# 1-Schematic_andromeda.net
KiCad netlist of a schematic drawn in EasyEDA
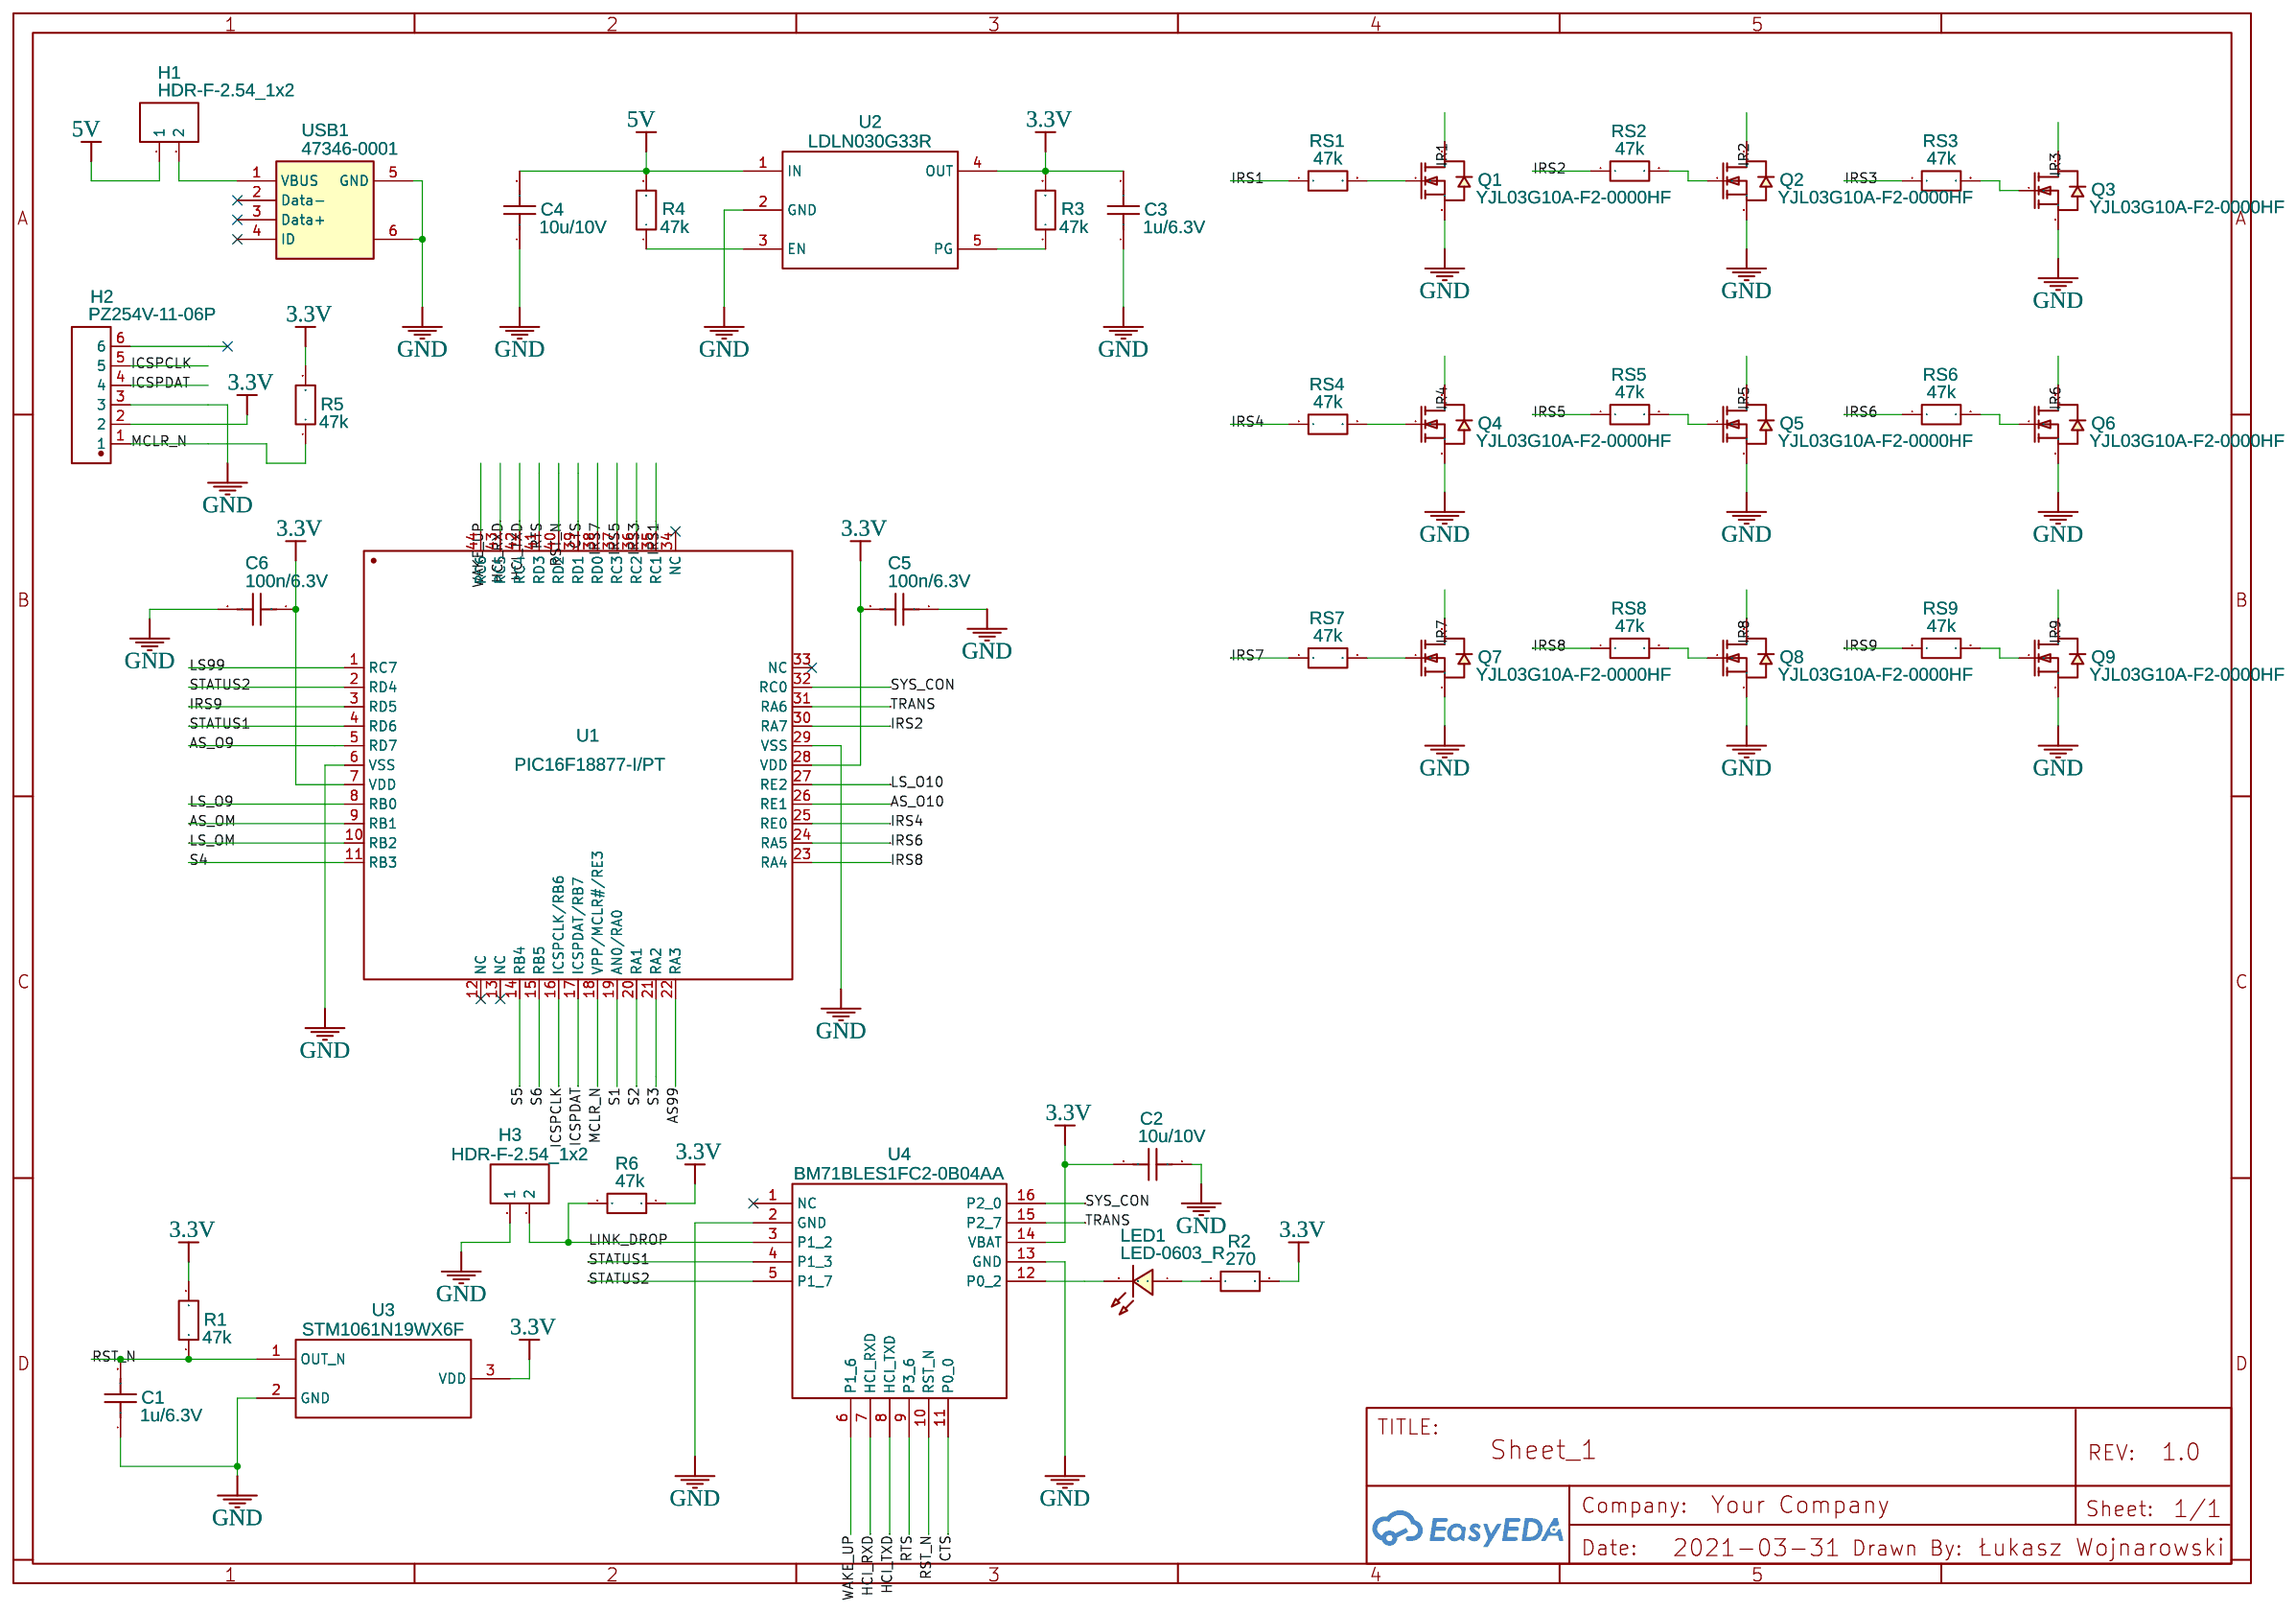
[diagram p0: uC]
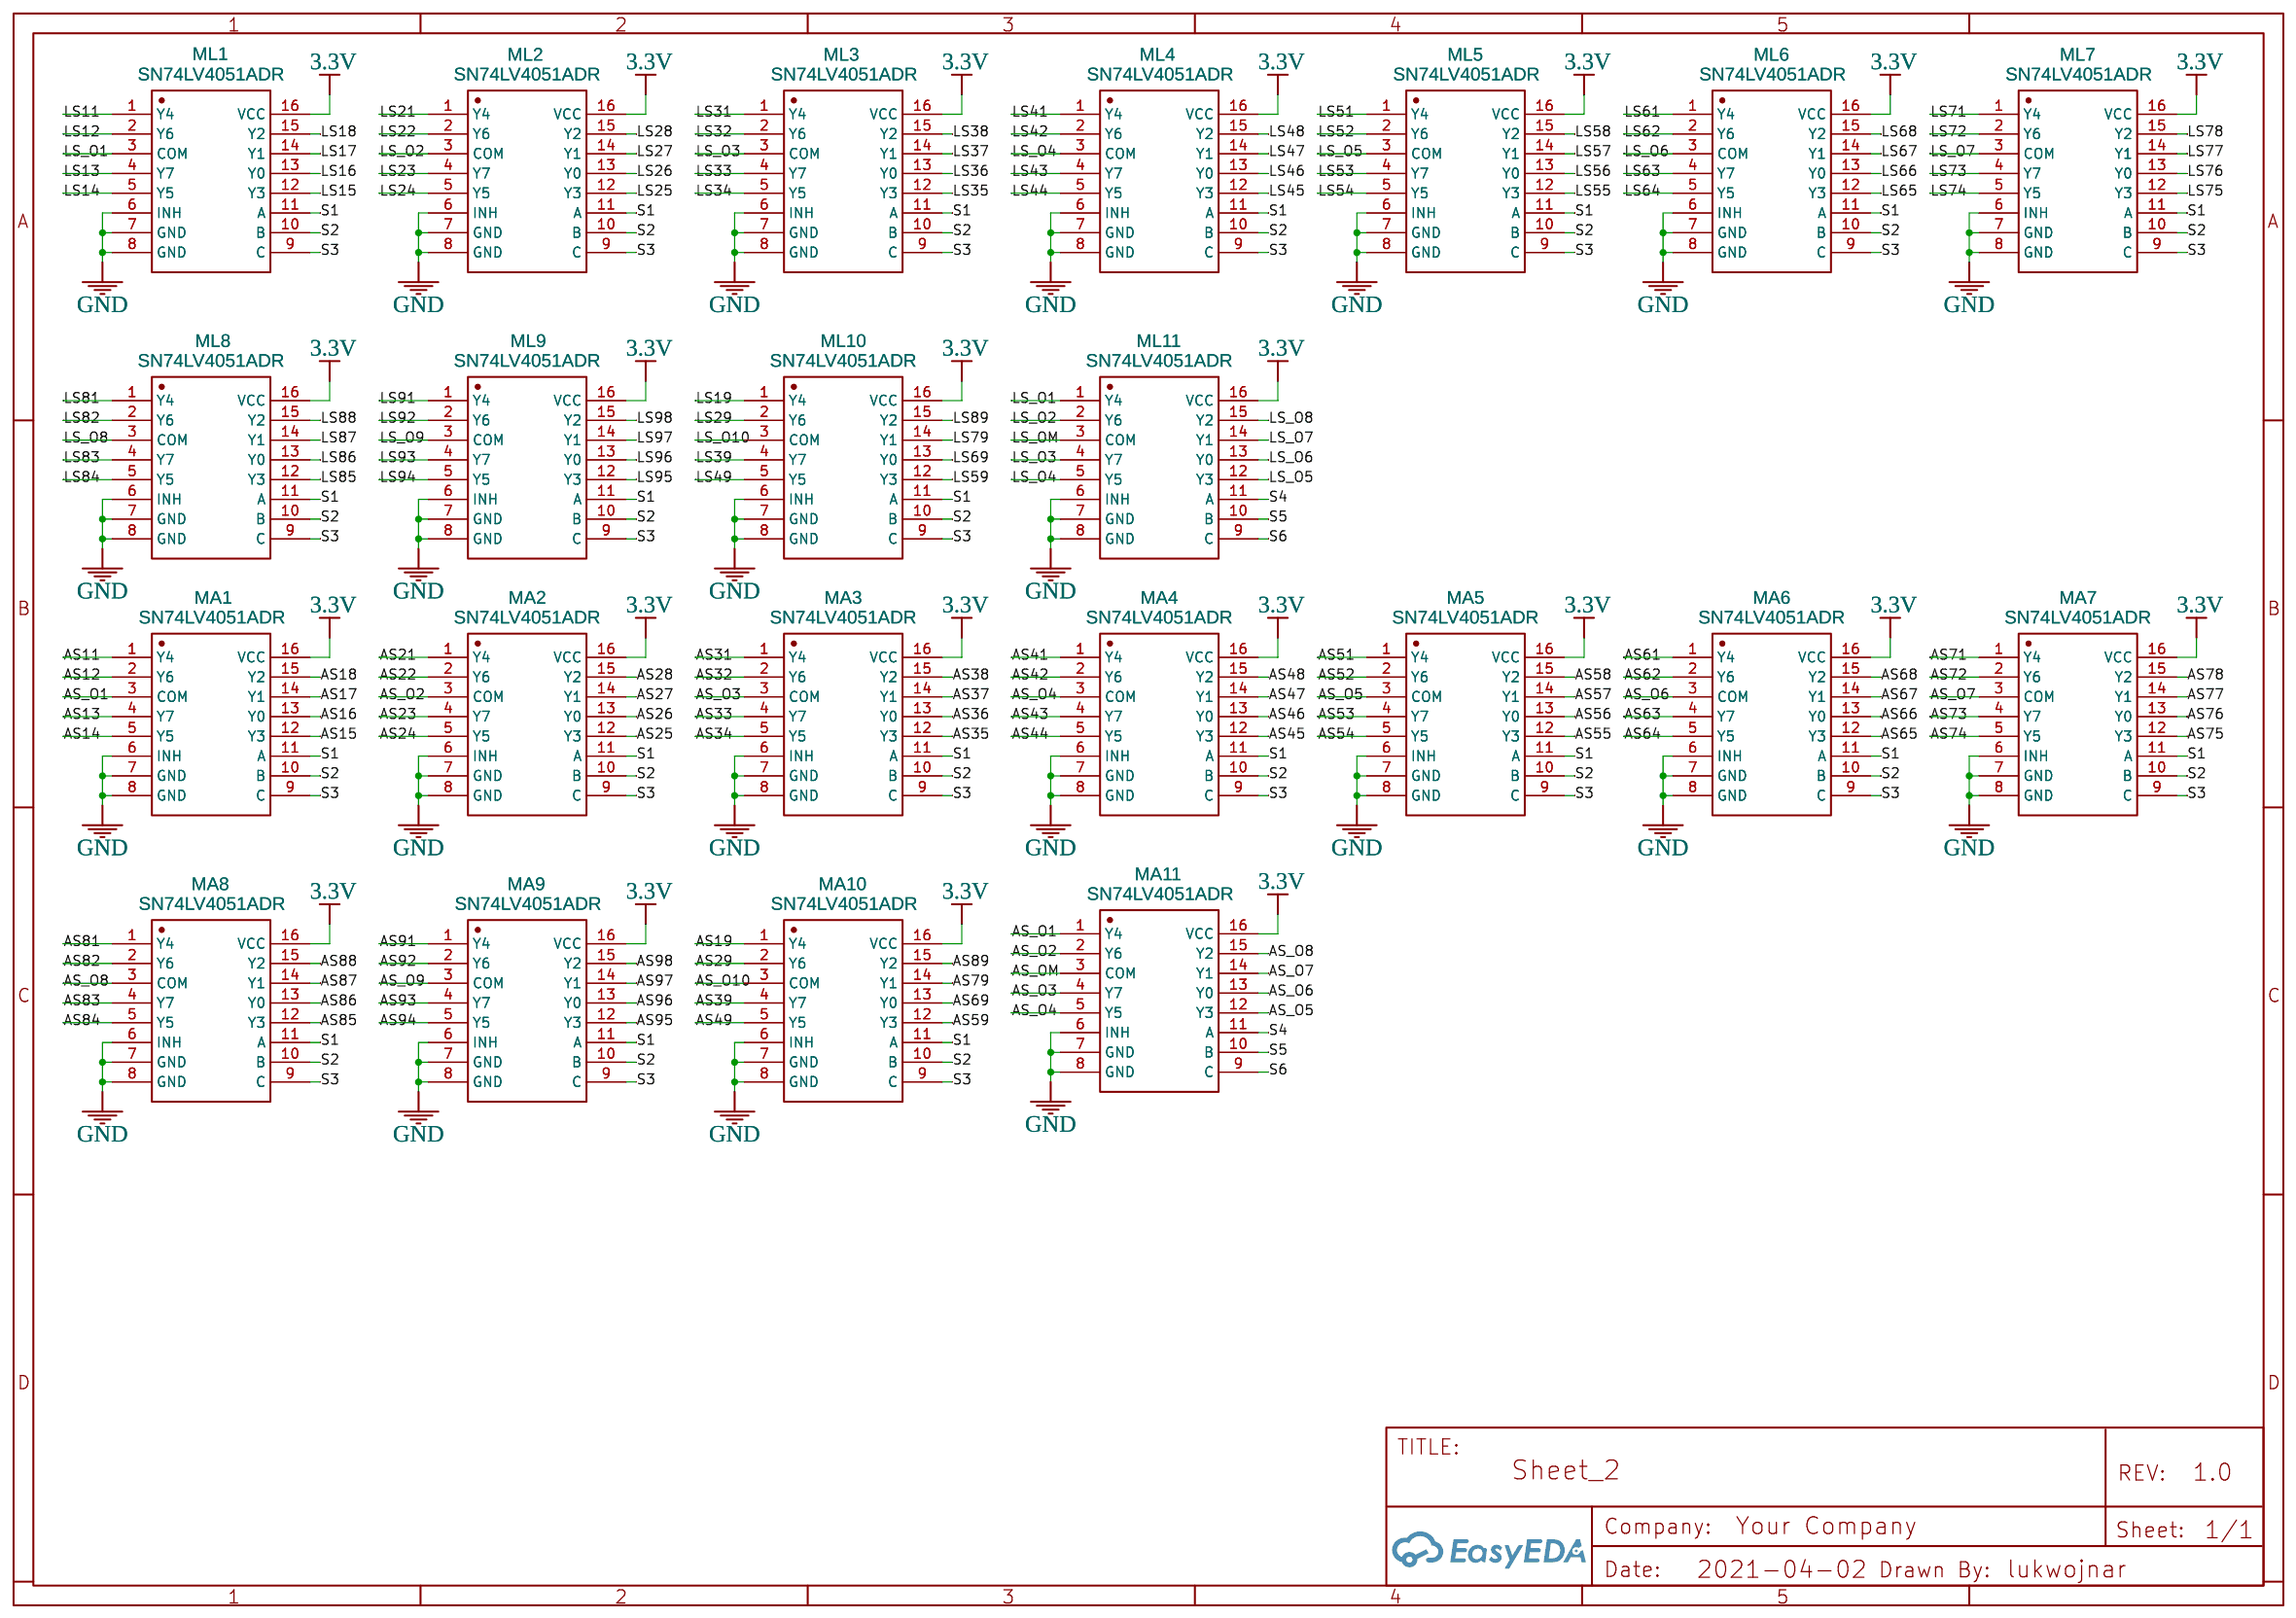
[diagram p1: MUX]
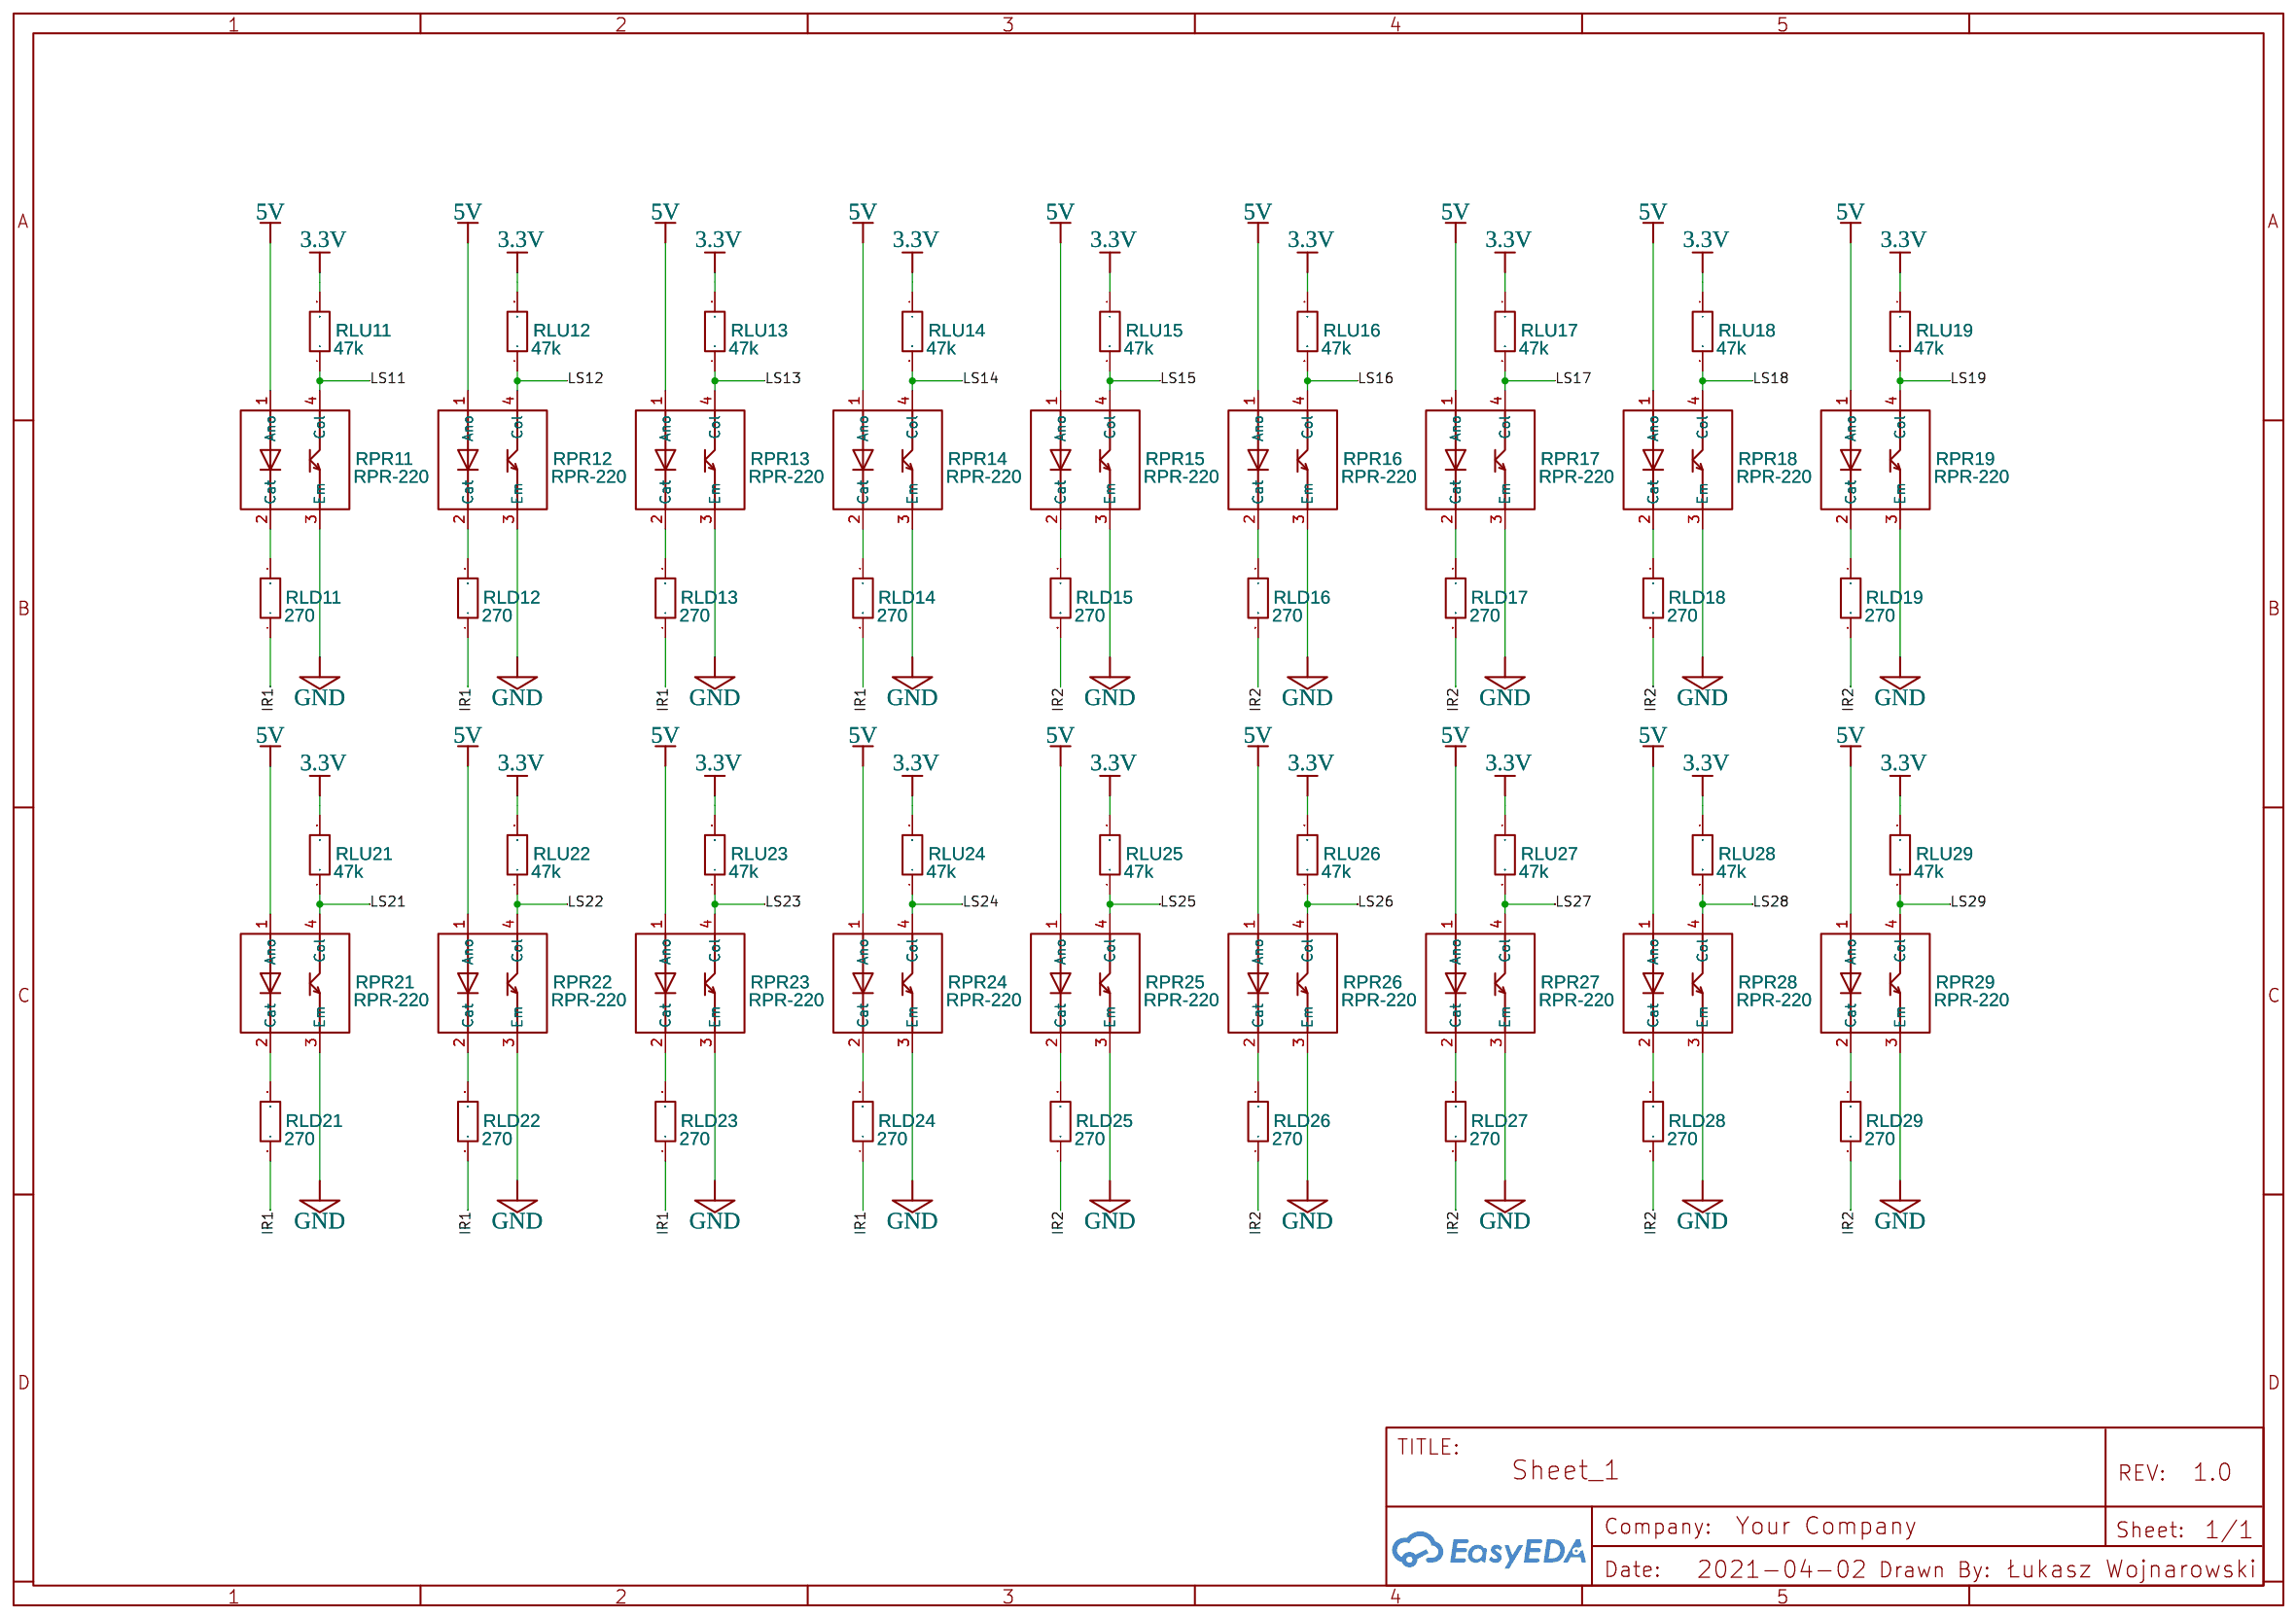
[diagram p2: Light Sensors 1]
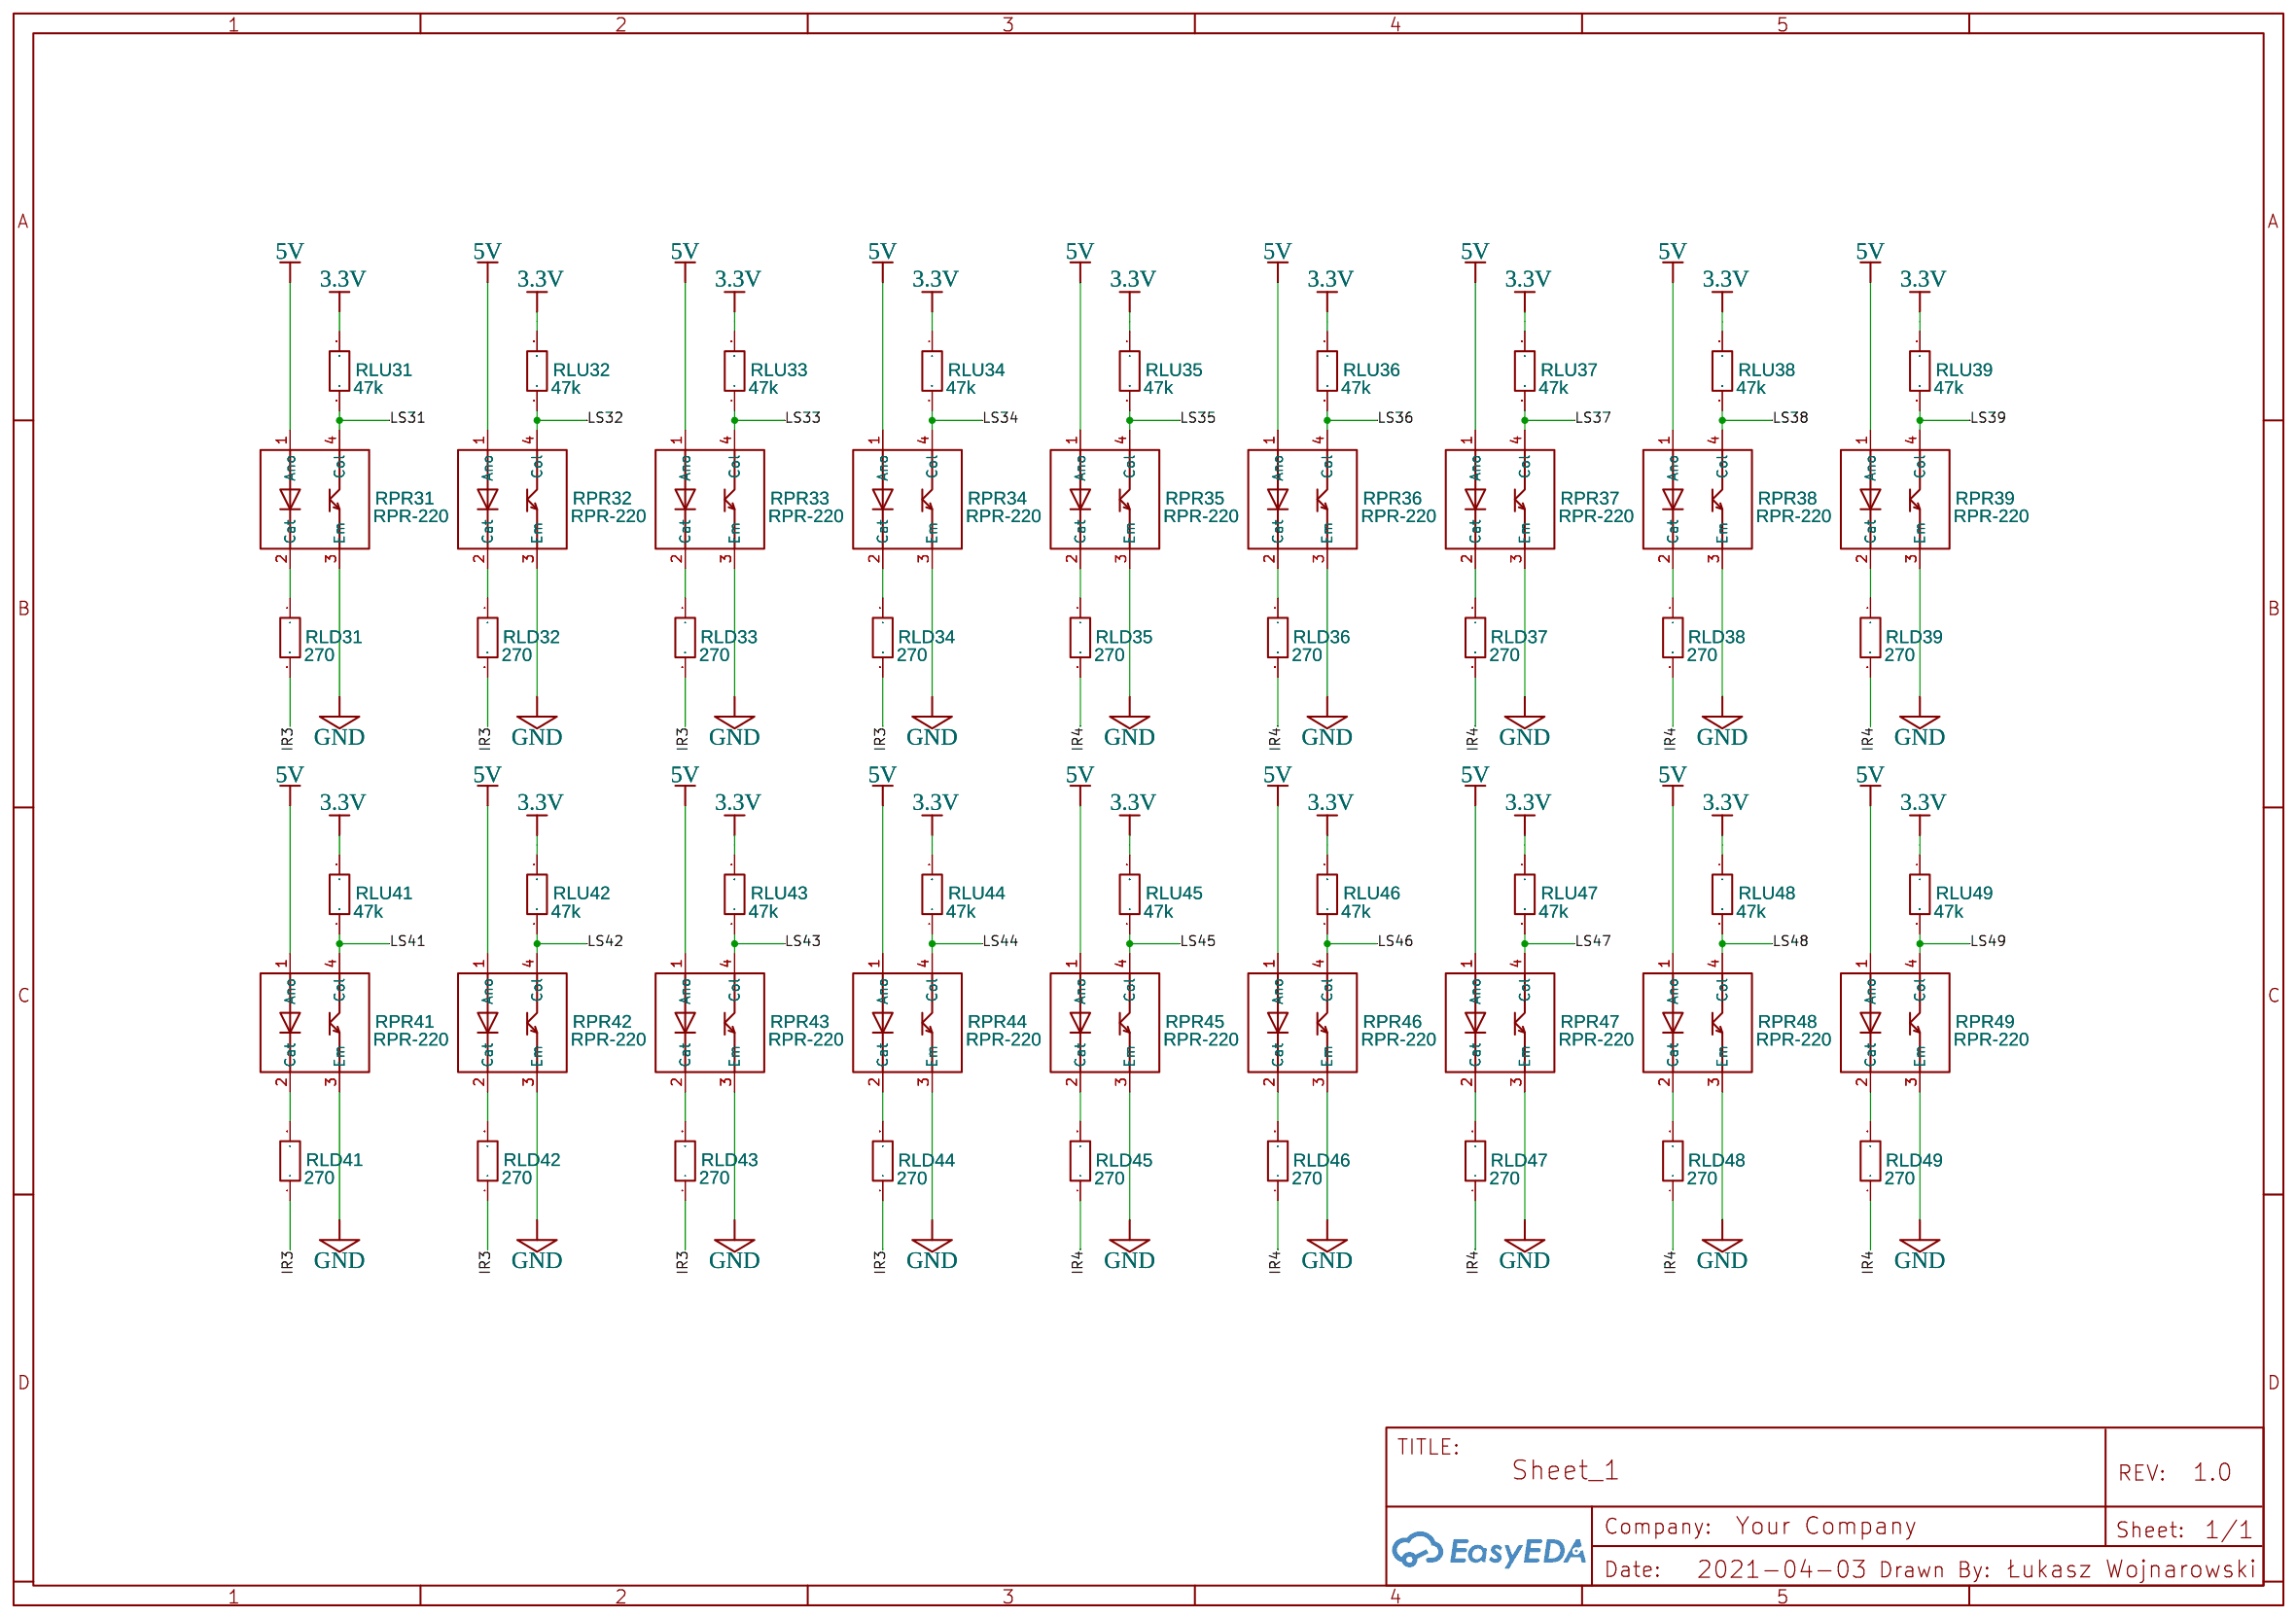
[diagram p3: Light Sensors 2]
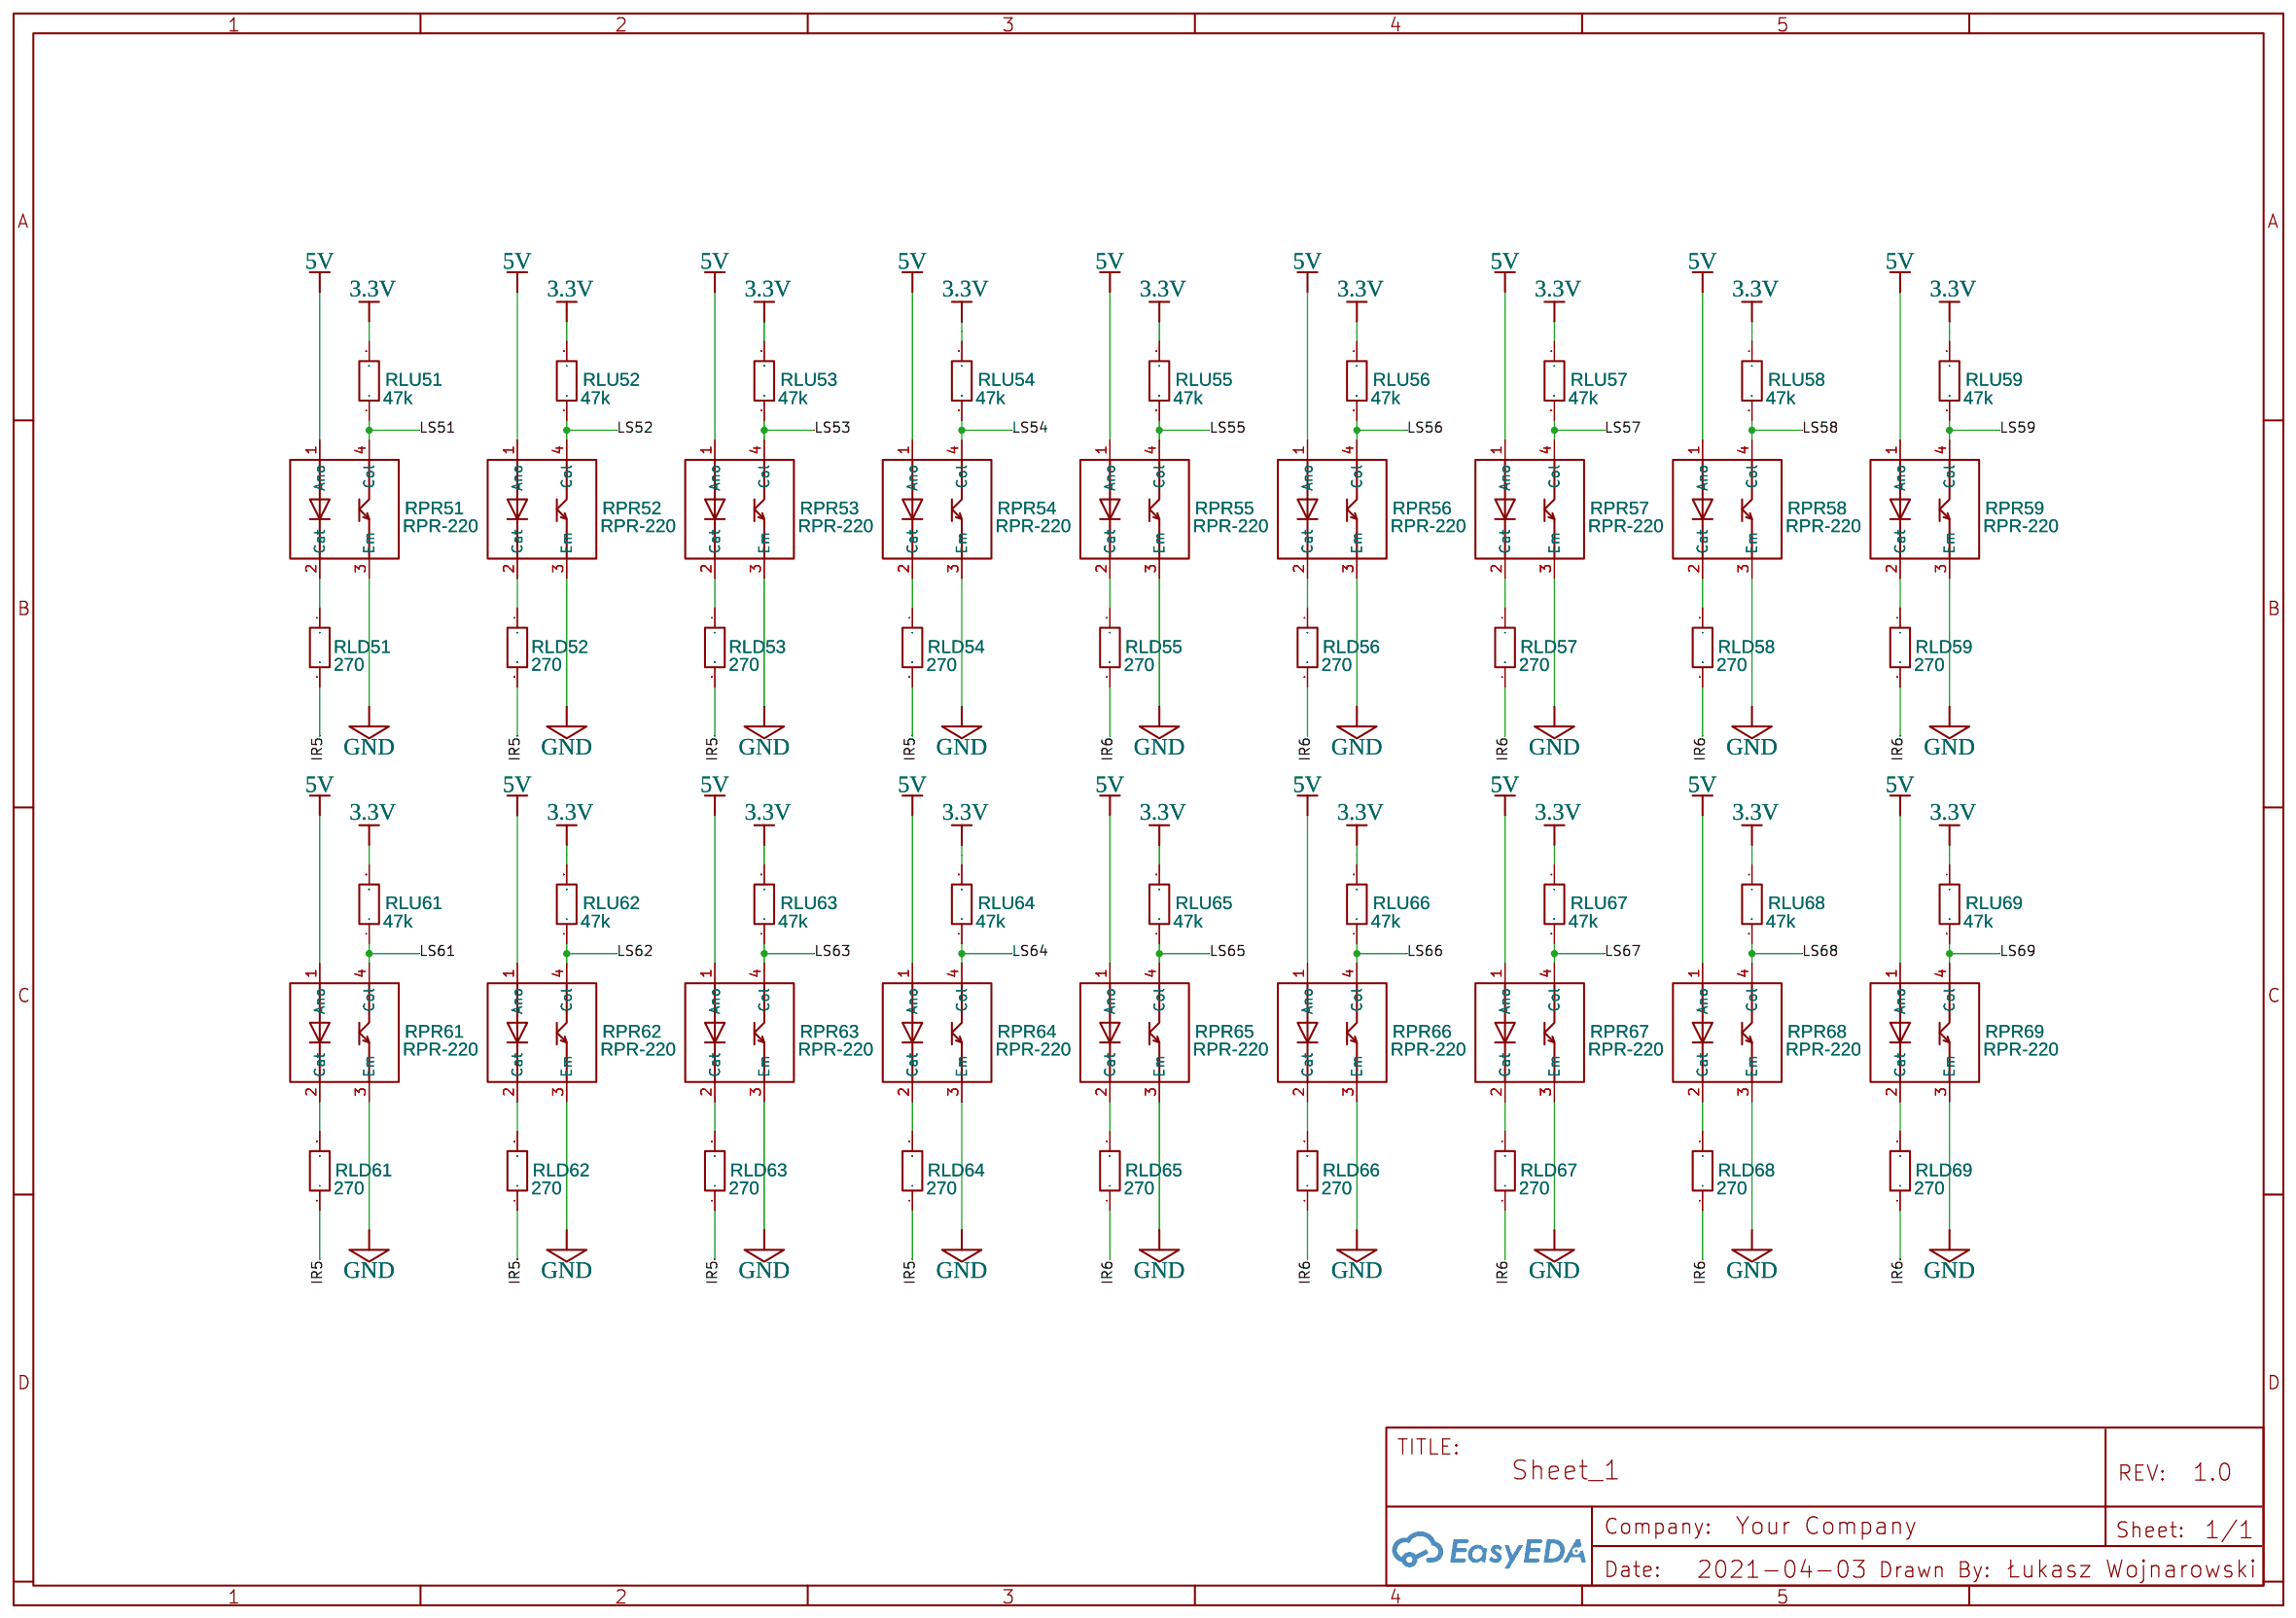
[diagram p4: Light Sensors 3]
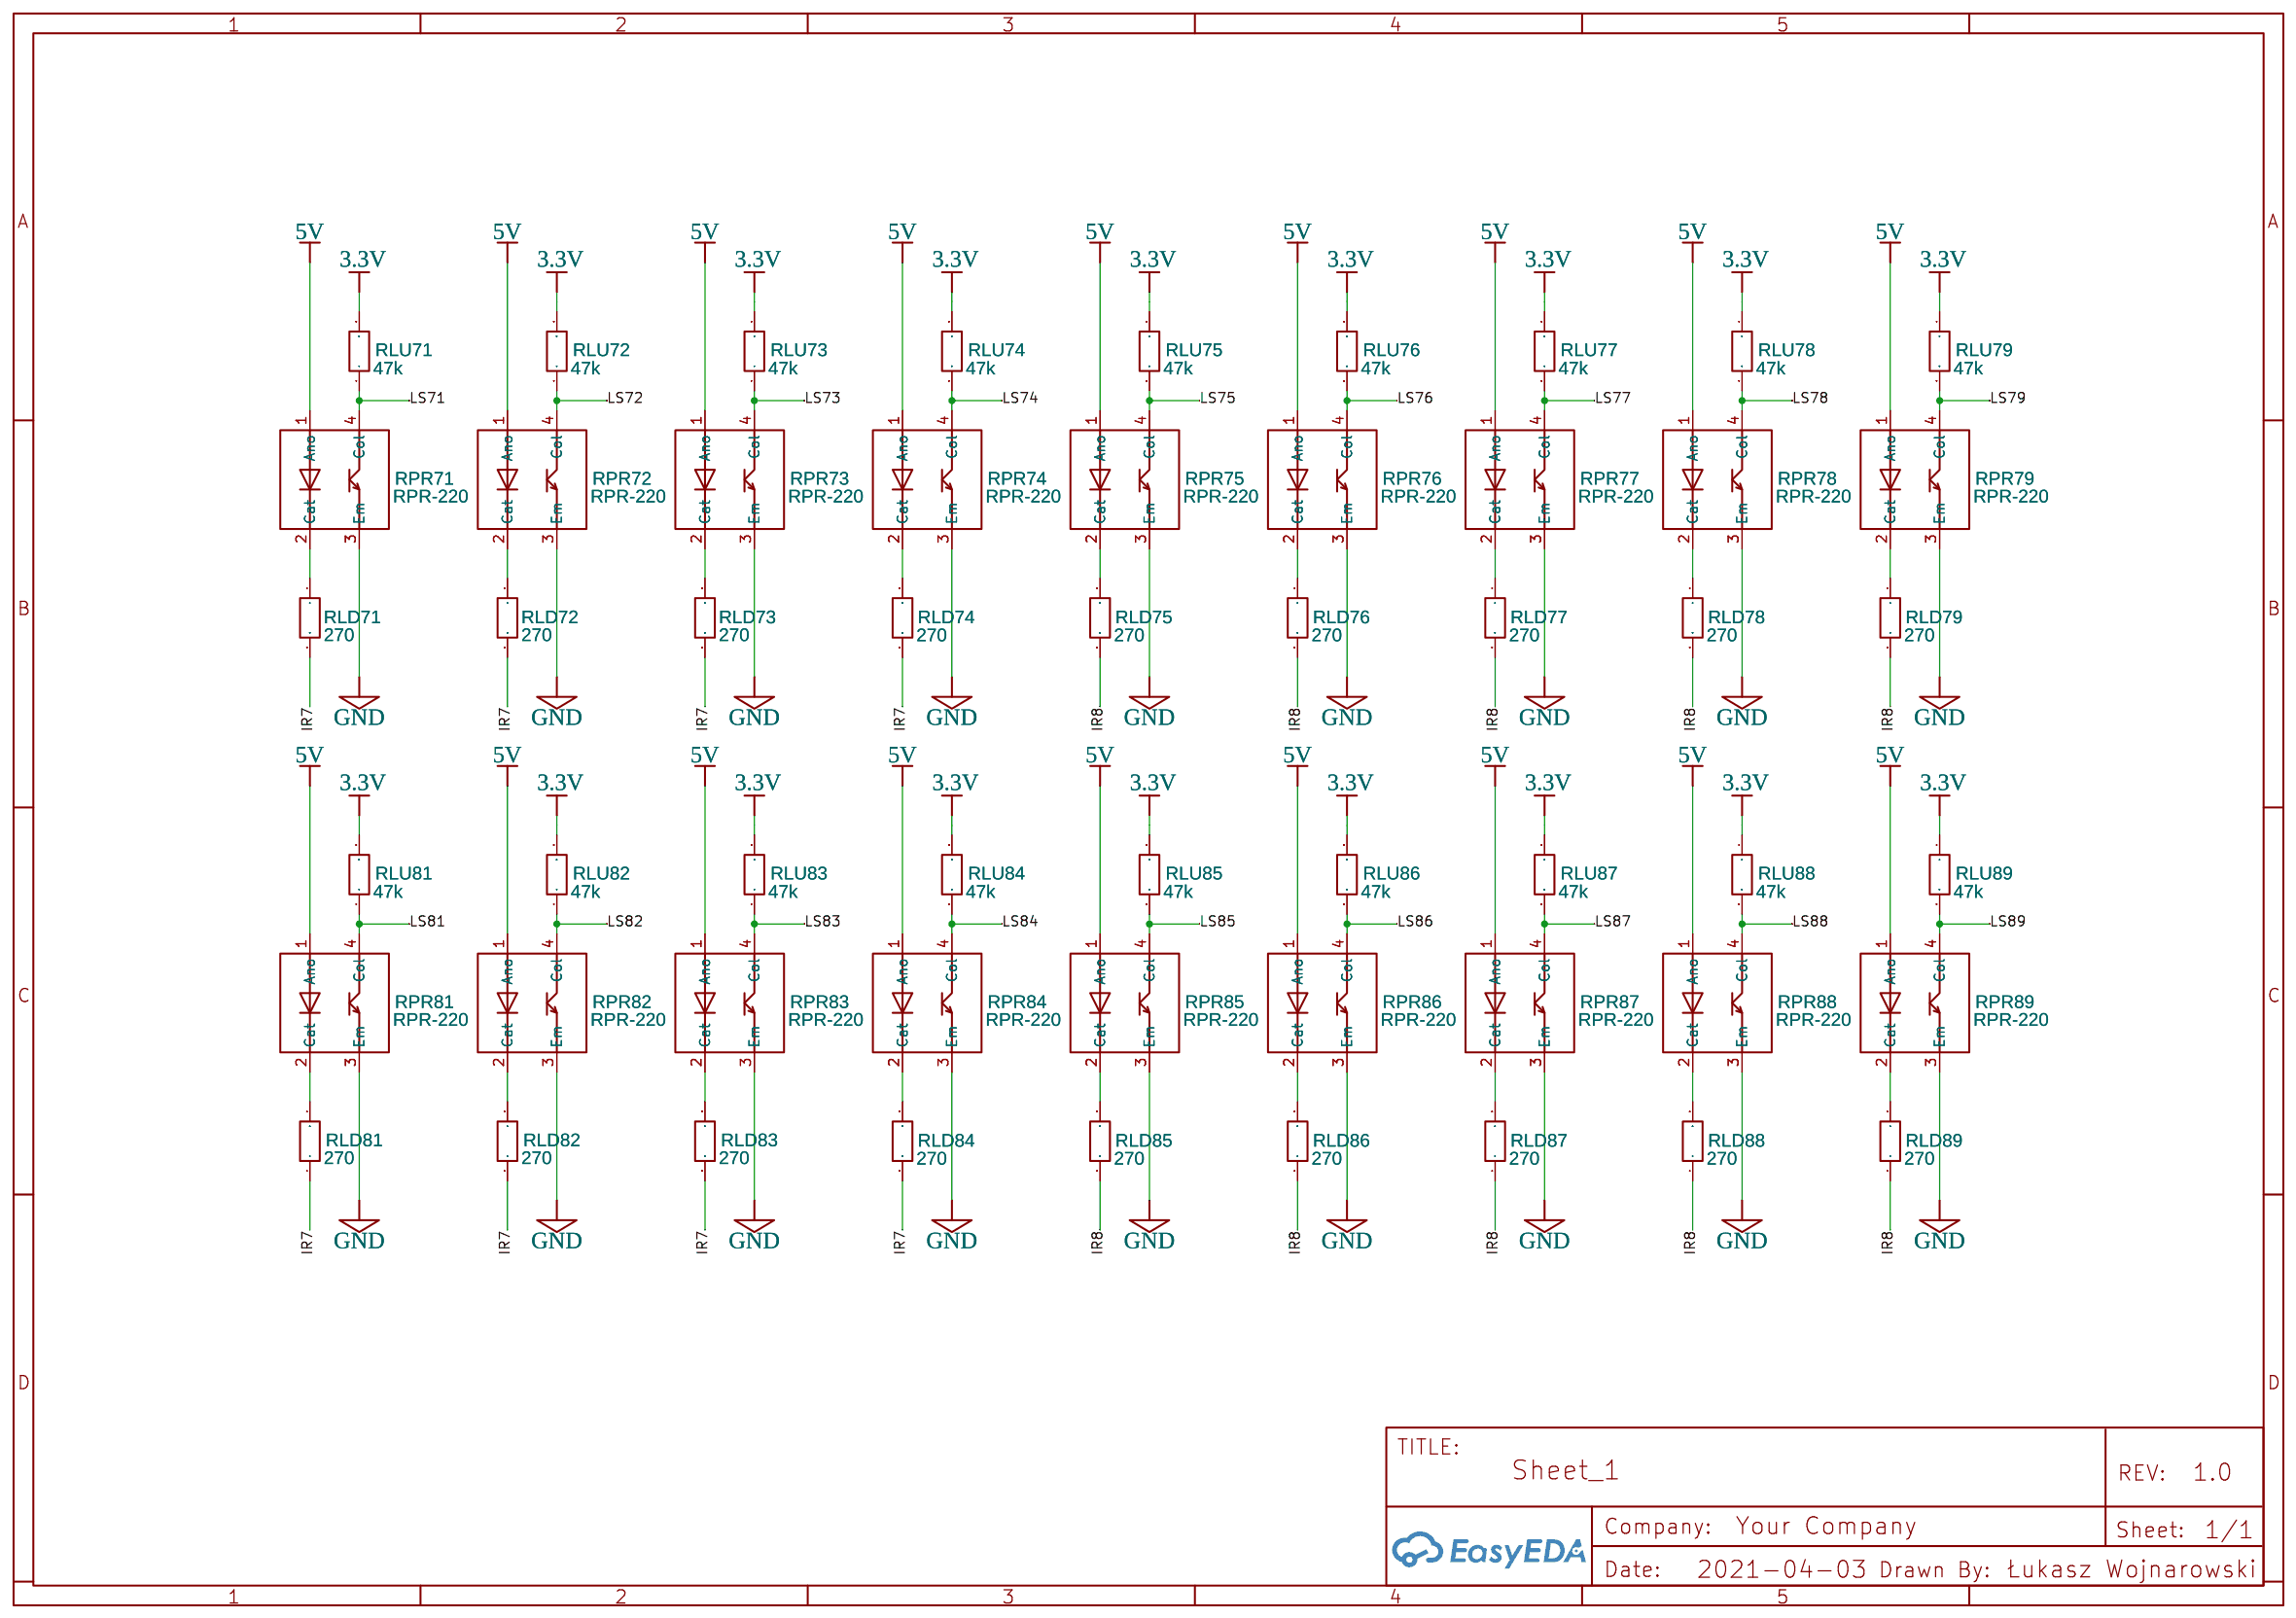
[diagram p5: Light Sensors 4]
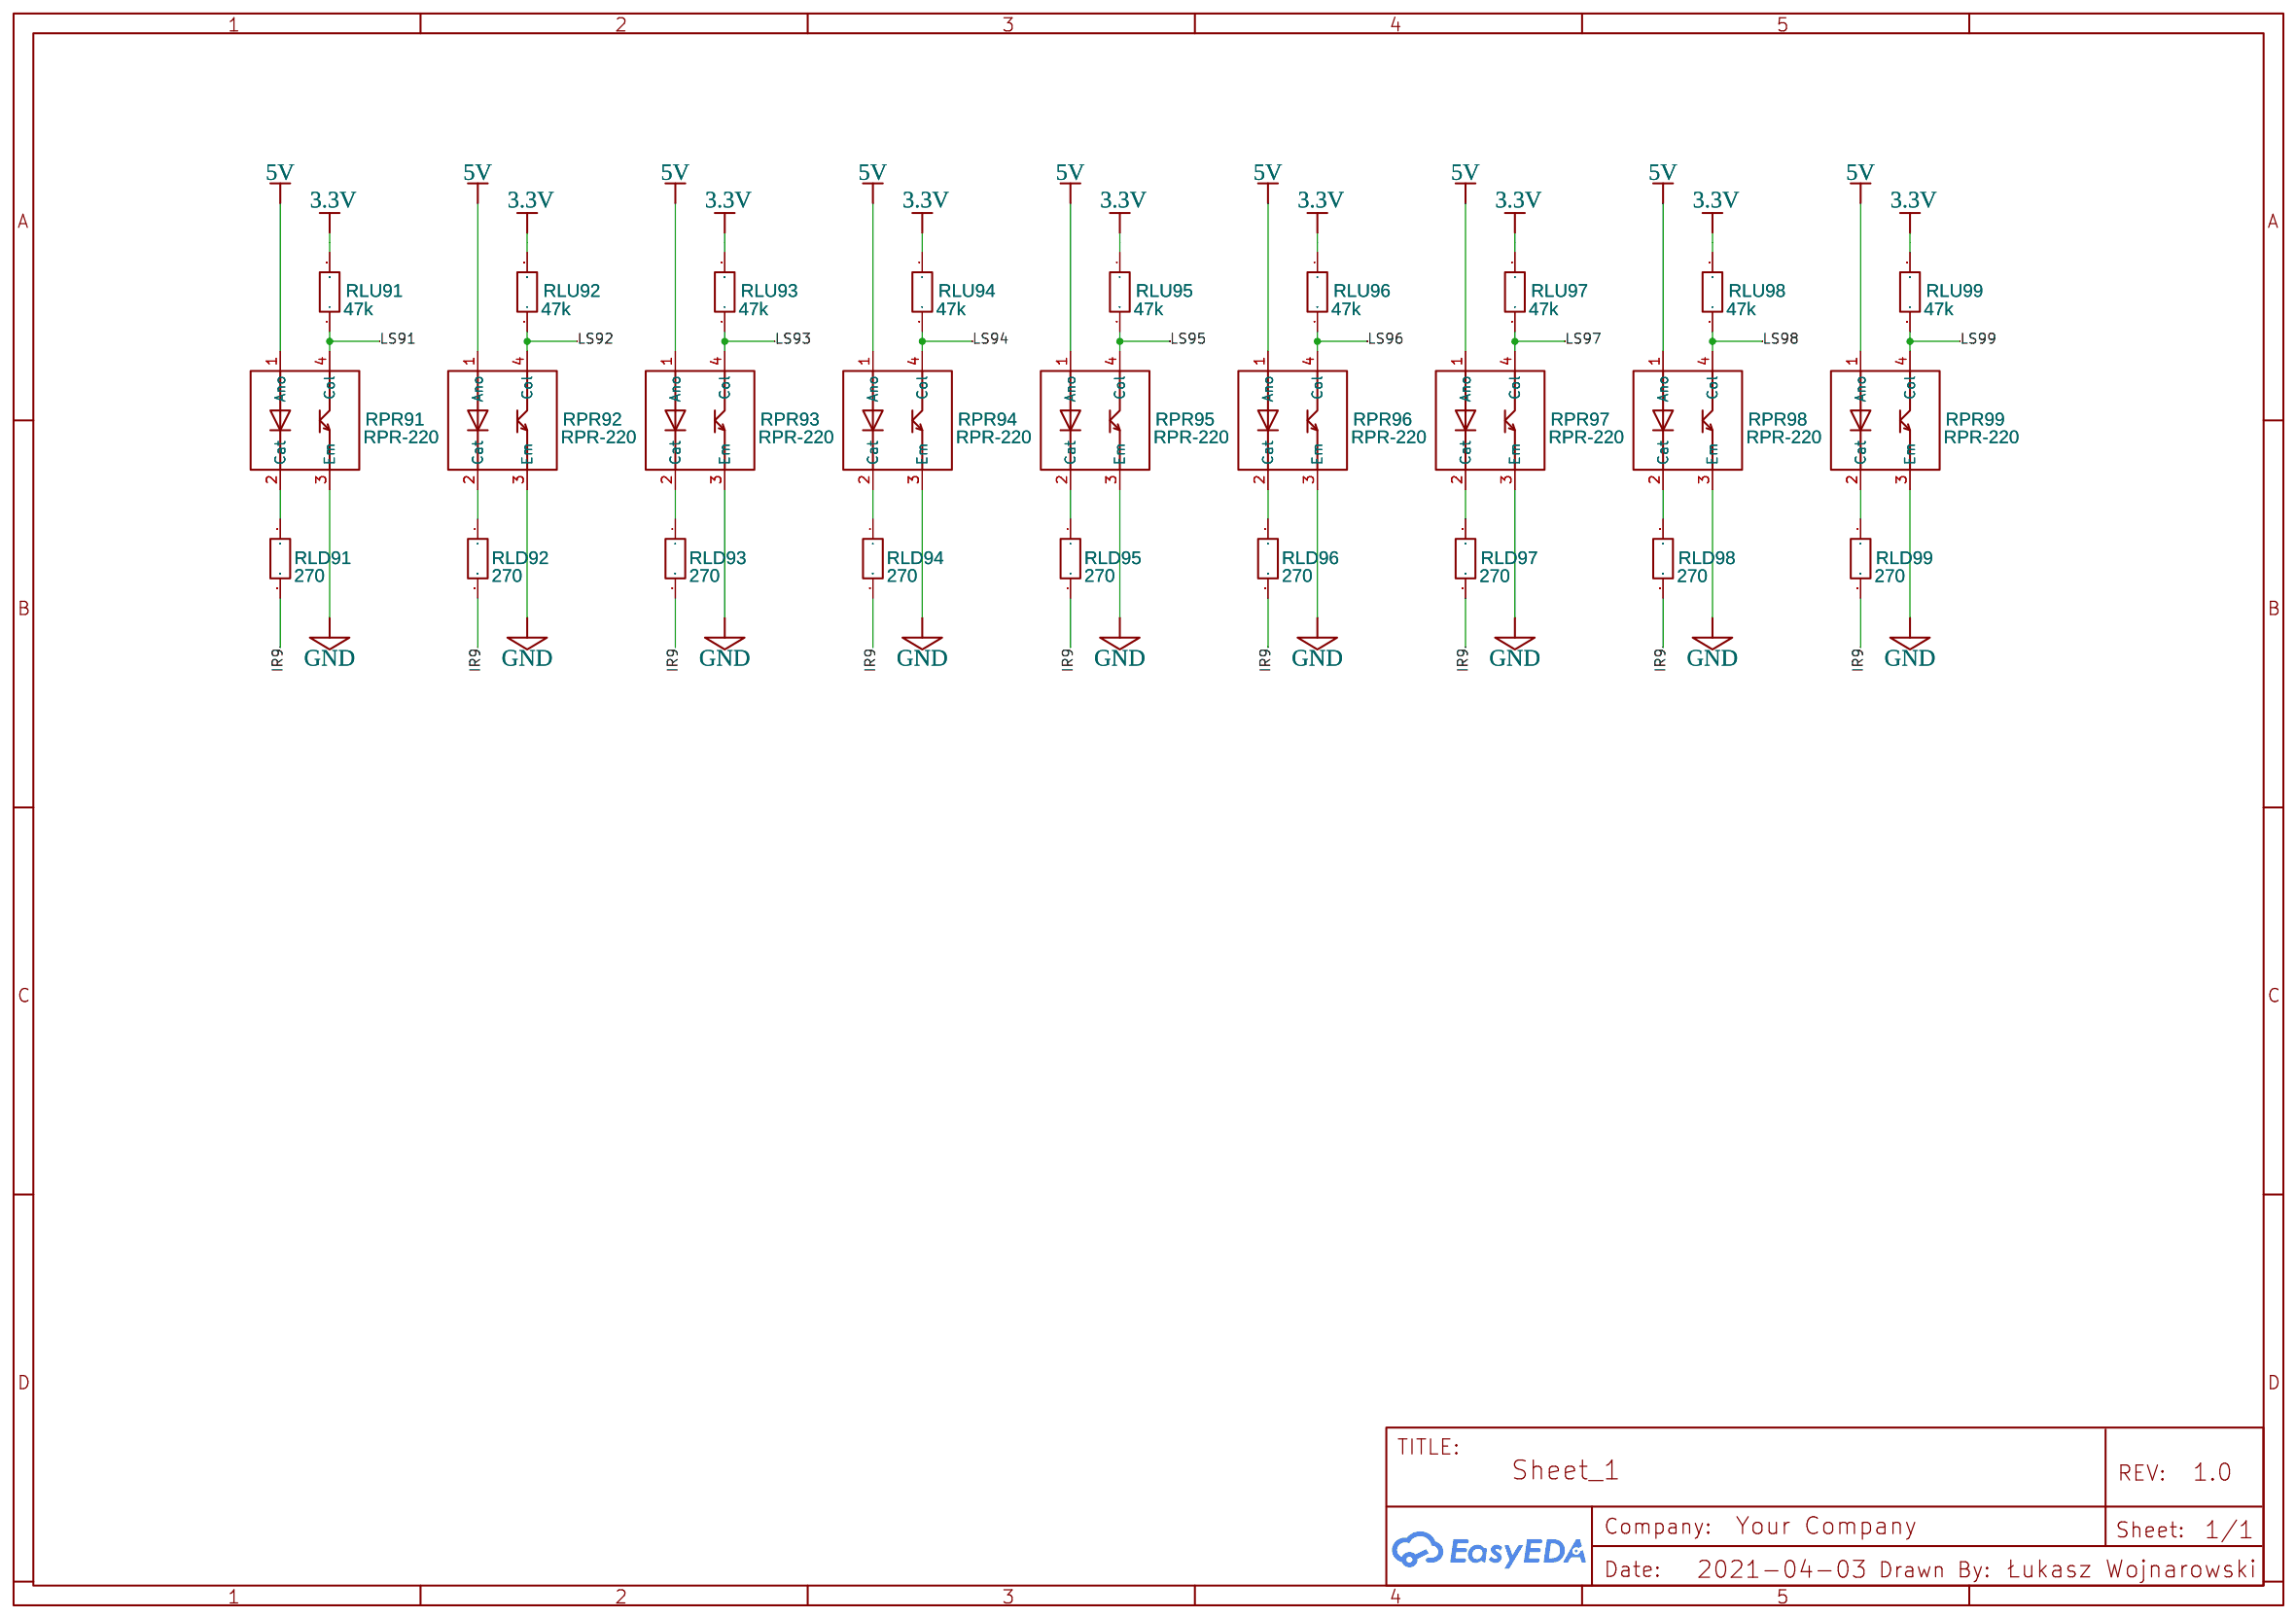
[diagram p6: Light Sensors 5]
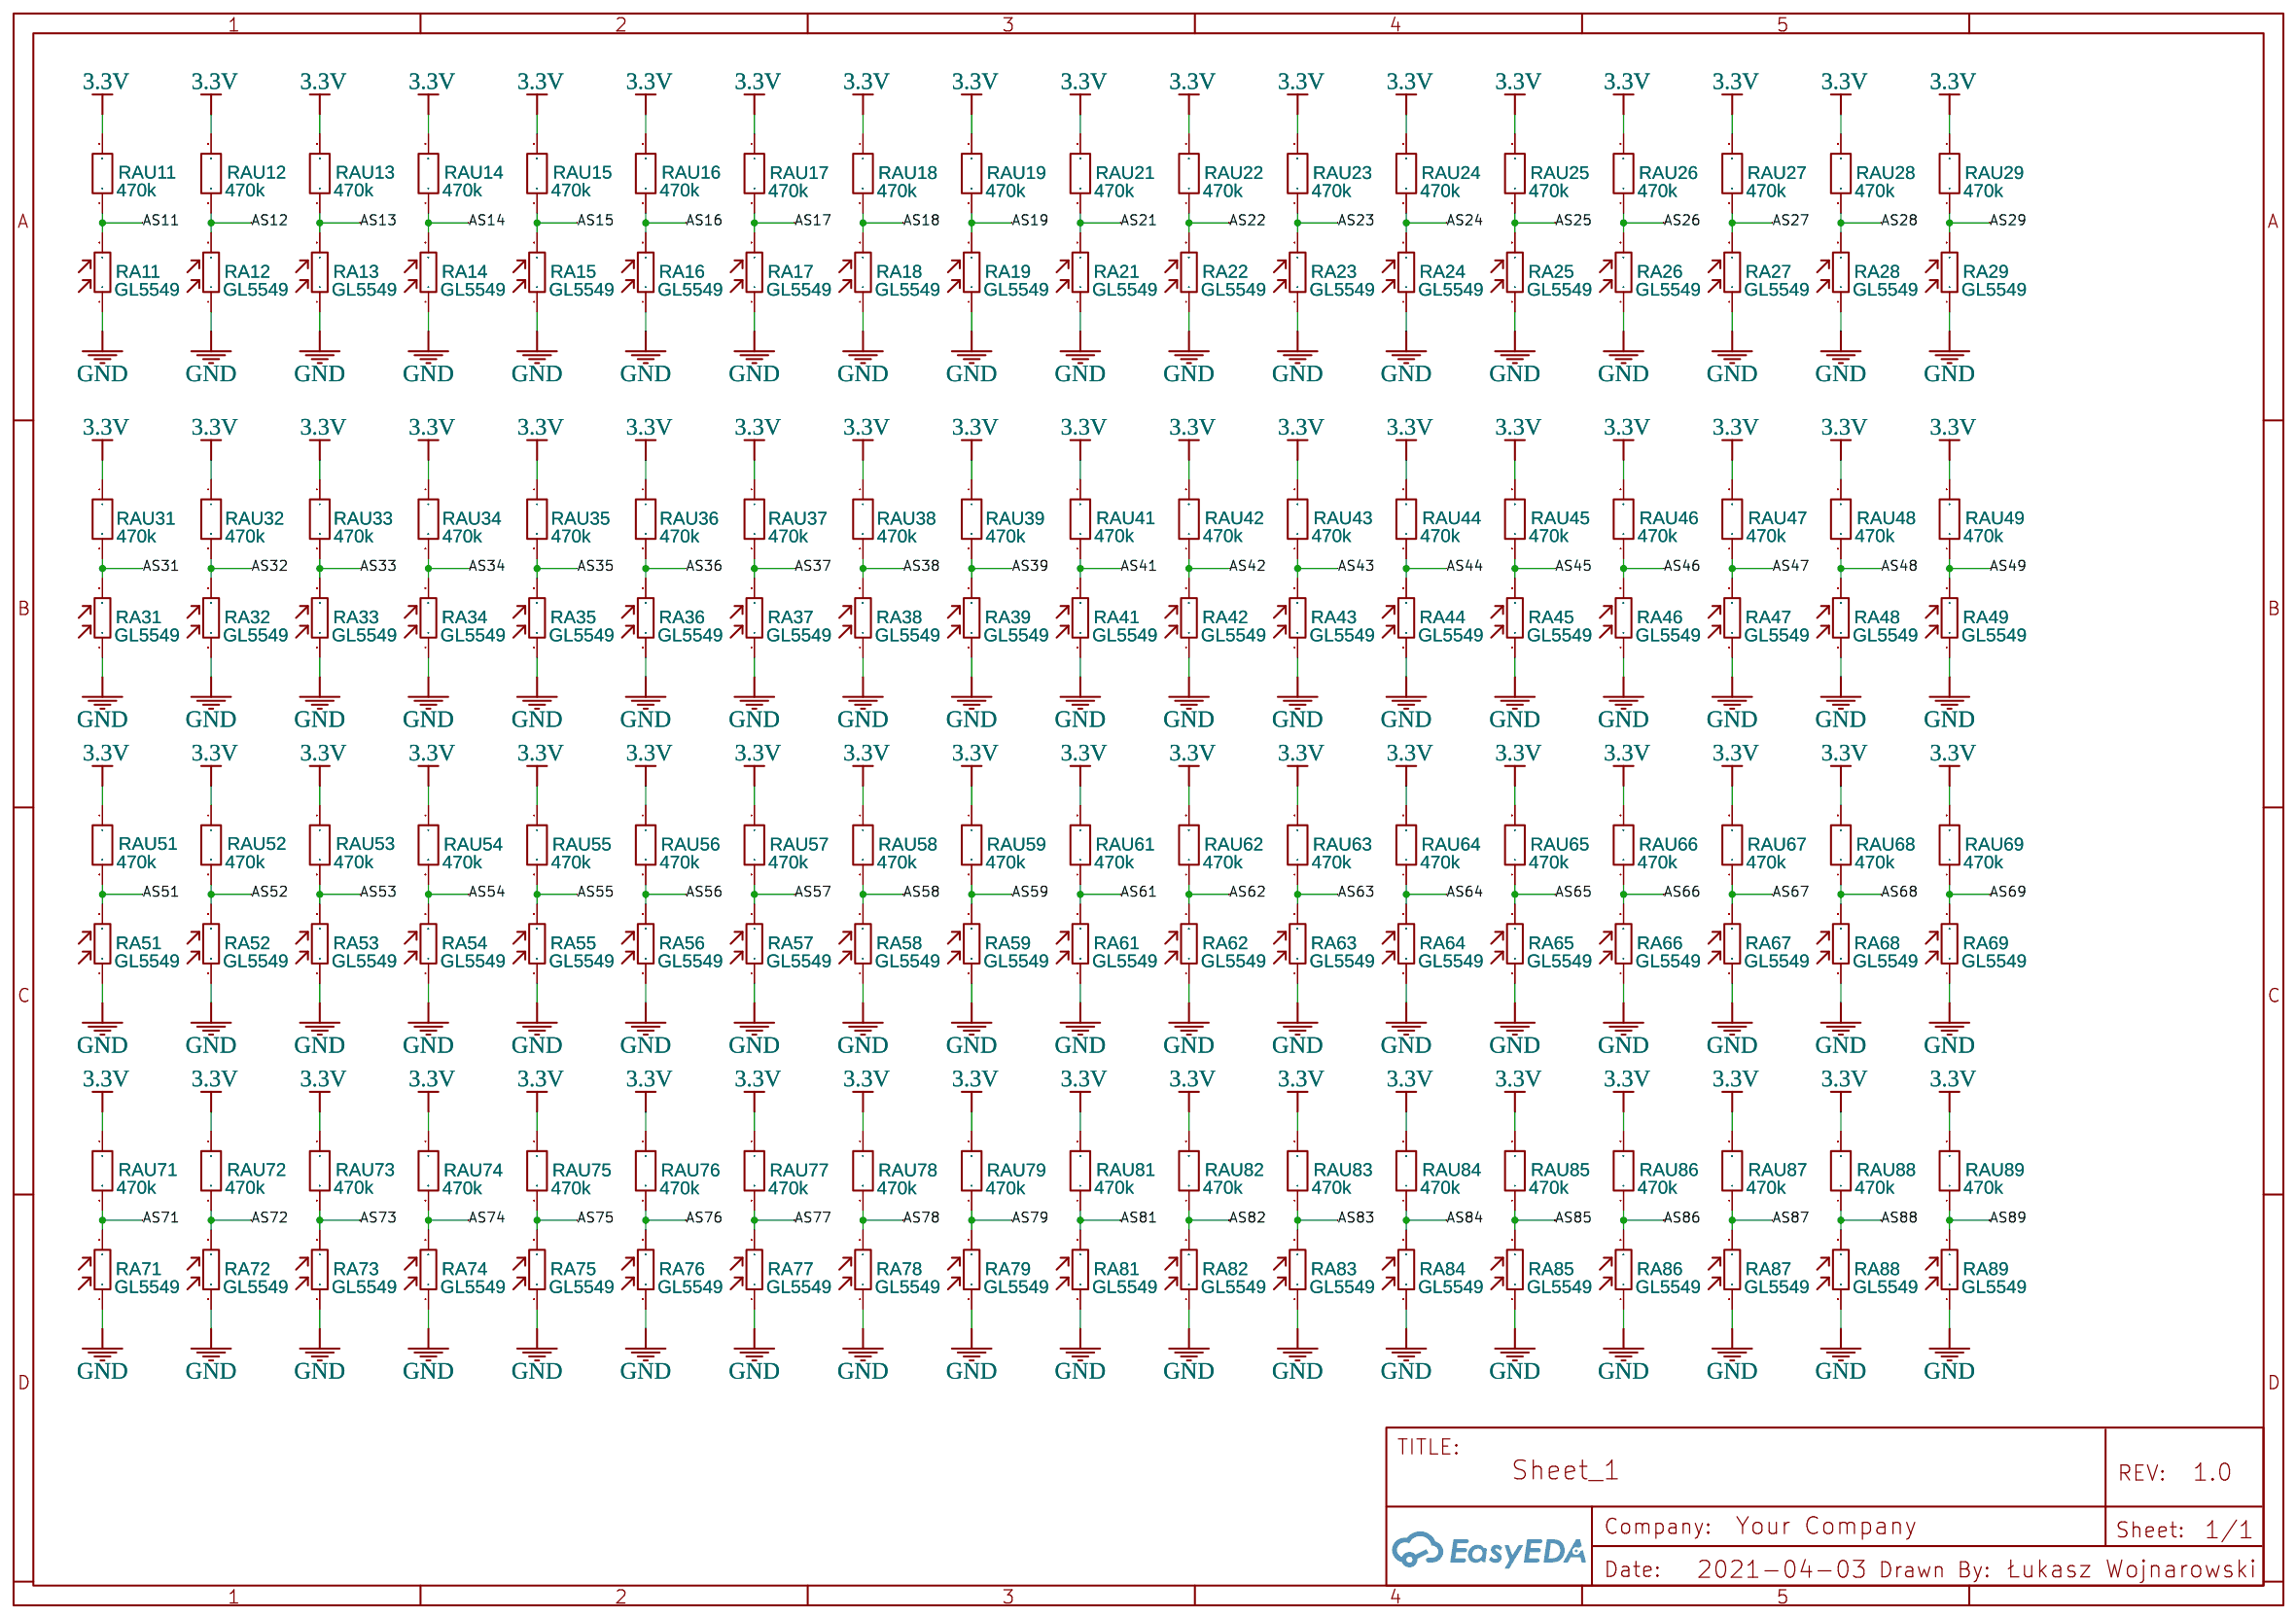
[diagram p7: Ambient Sensors 1]
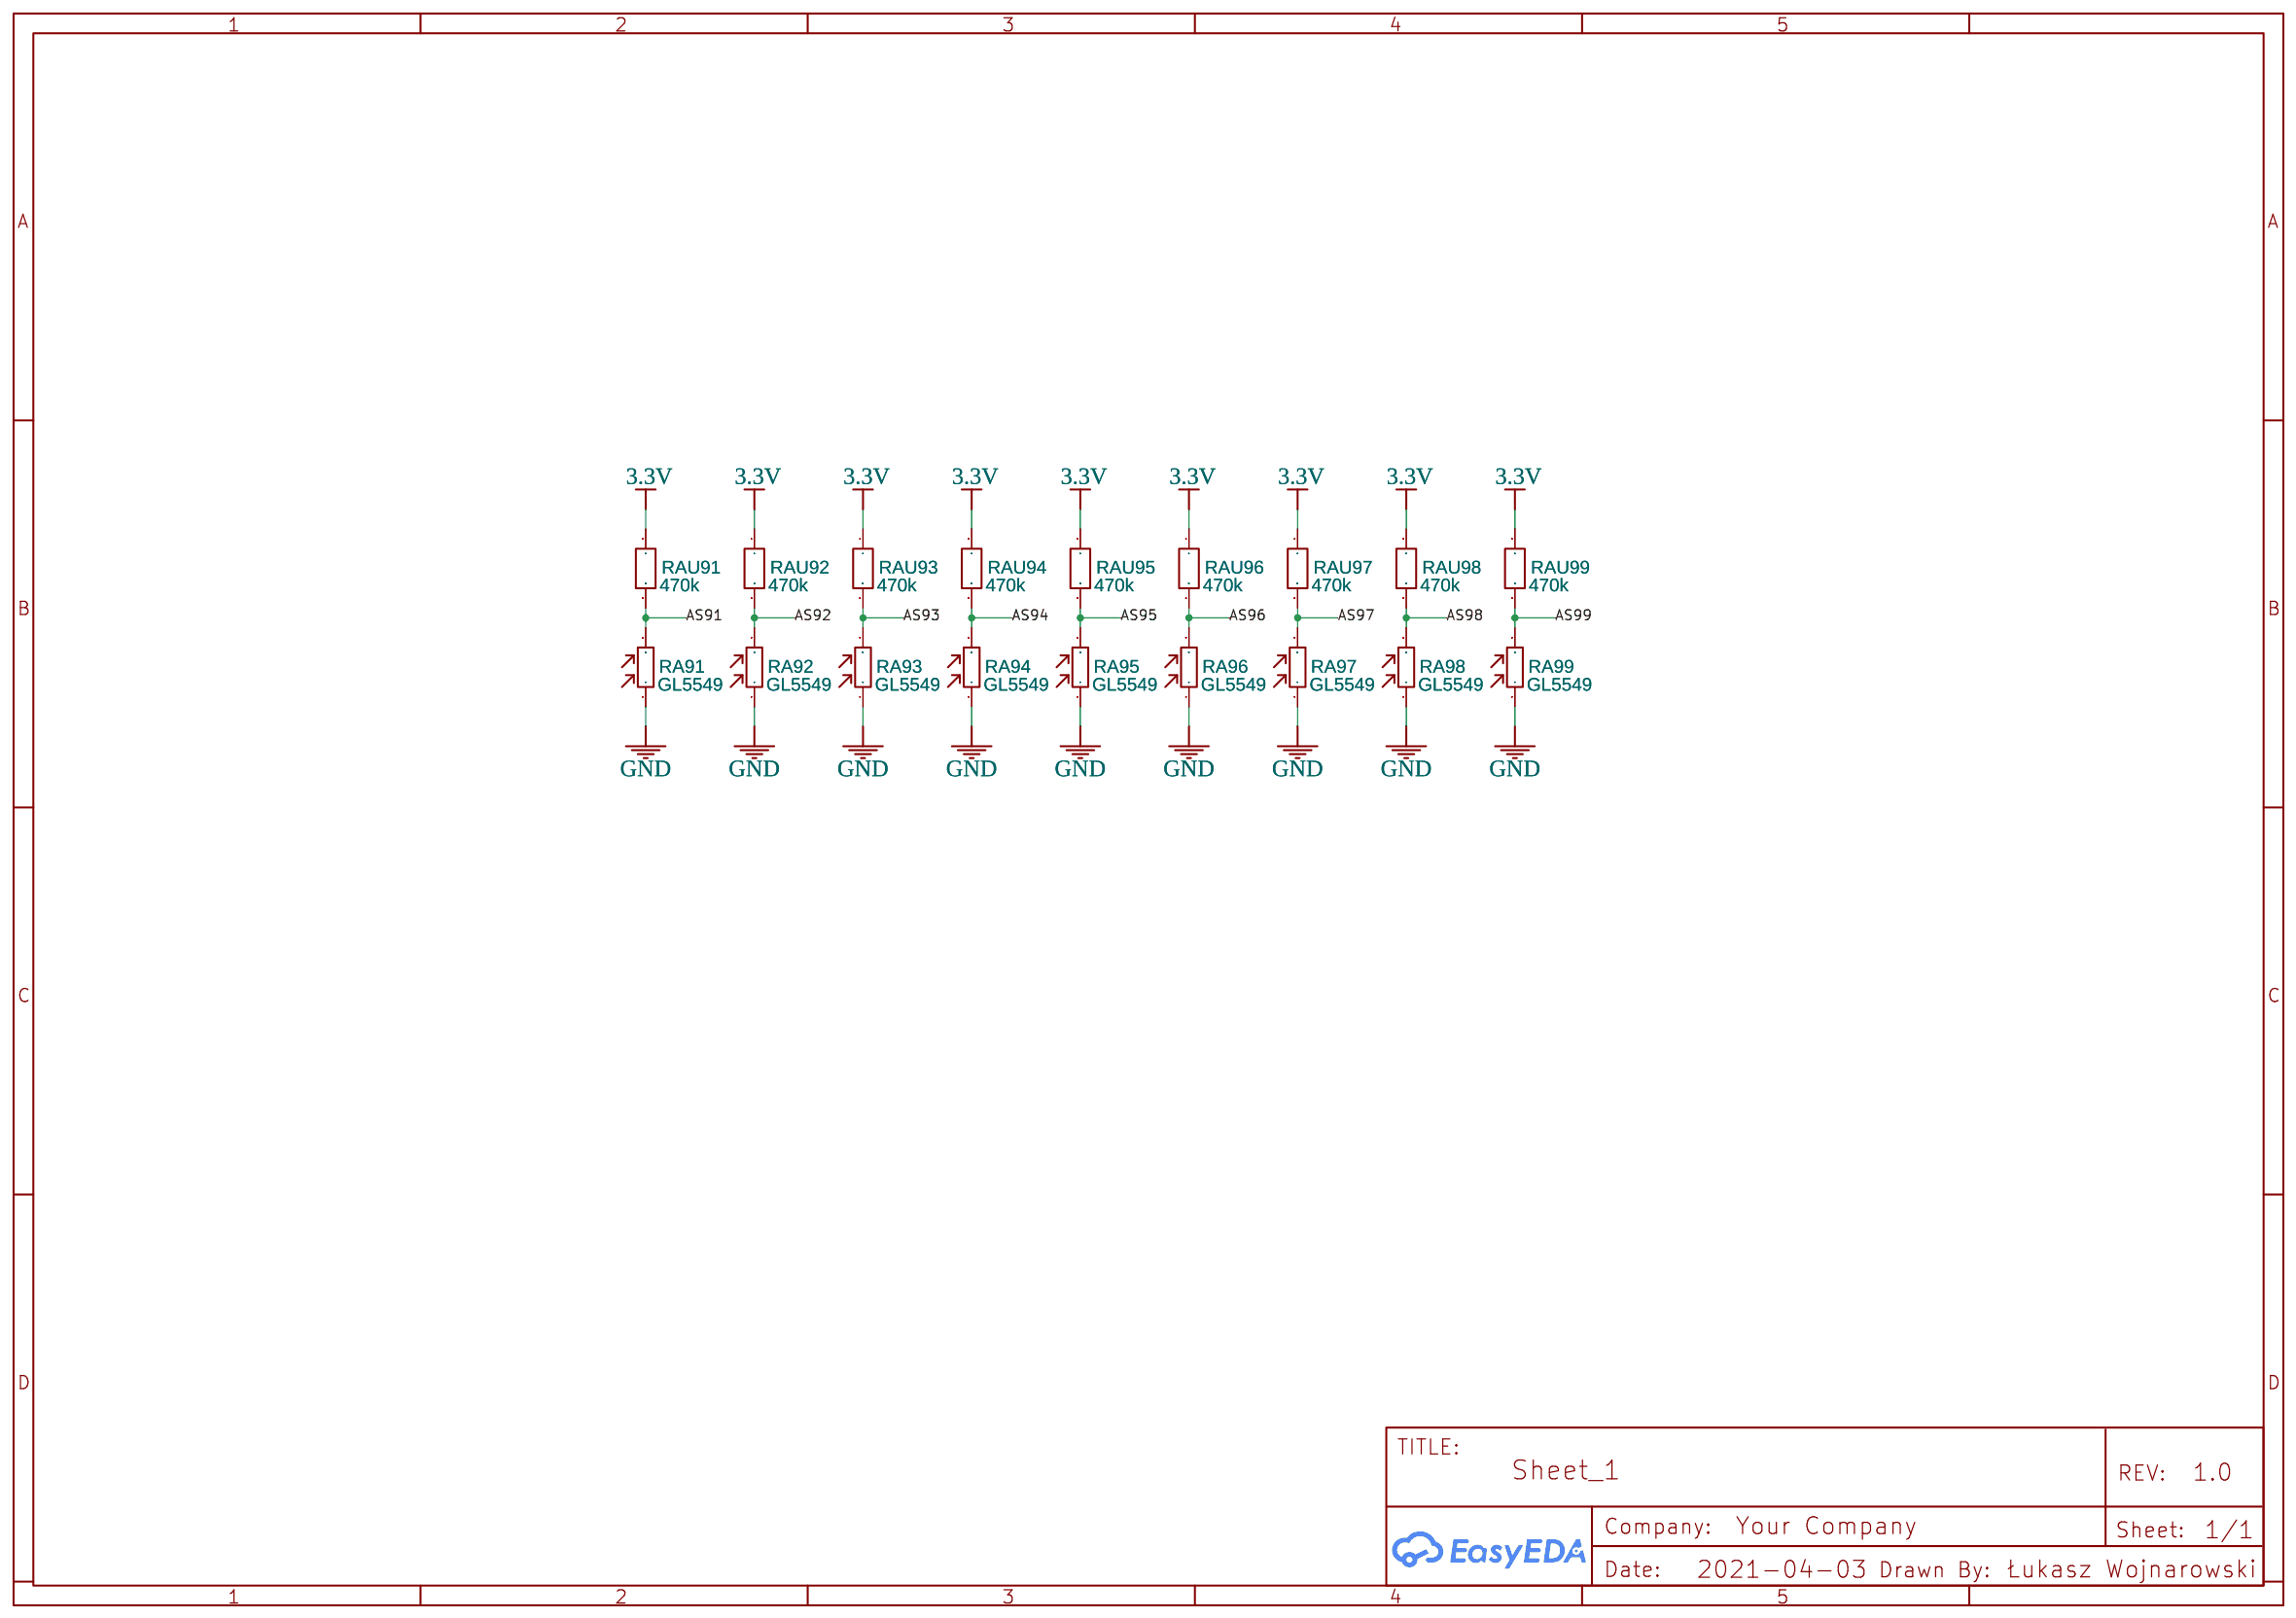
[diagram p8: Ambient Sensors 2]

(export (version "E")
  (design (tool "Eeschema 10.0.6"))
  (components
    (comp (ref "C1") (value "1u/6.3V") (libsource (lib "") (part "C_0603_US")))
    (comp (ref "C2") (value "10u/10V") (libsource (lib "") (part "C_0603_US_1")))
    (comp (ref "C3") (value "1u/6.3V") (libsource (lib "") (part "C_0603_US")))
    (comp (ref "C4") (value "10u/10V") (libsource (lib "") (part "C_0603_US")))
    (comp (ref "C5") (value "100n/6.3V") (libsource (lib "") (part "C_0603_US_1")))
    (comp (ref "C6") (value "100n/6.3V") (libsource (lib "") (part "C_0603_US_1")))
    (comp (ref "H1")
      (value "HDR-F-2.54_1x2")
      (fields (field (name "BOM_Supplier Part") "C49661"))
      (libsource (lib "") (part "HDR-F-2.54_1x2"))
    )
    (comp (ref "H2")
      (value "PZ254V-11-06P")
      (fields (field (name "BOM_Supplier Part") "C492405"))
      (libsource (lib "") (part "PZ254V-11-06P"))
    )
    (comp (ref "H3")
      (value "HDR-F-2.54_1x2")
      (fields (field (name "BOM_Supplier Part") "C49661"))
      (libsource (lib "") (part "HDR-F-2.54_1x2"))
    )
    (comp (ref "LED1")
      (value "LED-0603_R")
      (fields
        (field (name "BOM_Manufacturer Part") "19-217/R6C-AL1M2VY/3T")
        (field (name "BOM_Supplier Part") "C72044")
      )
      (libsource (lib "") (part "LED-0603_R"))
    )
    (comp (ref "Q1")
      (value "YJL03G10A-F2-0000HF")
      (fields (field (name "BOM_Supplier Part") "C919604"))
      (libsource (lib "") (part "YJL03G10A-F2-0000HF"))
    )
    (comp (ref "Q2")
      (value "YJL03G10A-F2-0000HF")
      (fields (field (name "BOM_Supplier Part") "C919604"))
      (libsource (lib "") (part "YJL03G10A-F2-0000HF"))
    )
    (comp (ref "Q3")
      (value "YJL03G10A-F2-0000HF")
      (fields (field (name "BOM_Supplier Part") "C919604"))
      (libsource (lib "") (part "YJL03G10A-F2-0000HF"))
    )
    (comp (ref "Q4")
      (value "YJL03G10A-F2-0000HF")
      (fields (field (name "BOM_Supplier Part") "C919604"))
      (libsource (lib "") (part "YJL03G10A-F2-0000HF"))
    )
    (comp (ref "Q5")
      (value "YJL03G10A-F2-0000HF")
      (fields (field (name "BOM_Supplier Part") "C919604"))
      (libsource (lib "") (part "YJL03G10A-F2-0000HF"))
    )
    (comp (ref "Q6")
      (value "YJL03G10A-F2-0000HF")
      (fields (field (name "BOM_Supplier Part") "C919604"))
      (libsource (lib "") (part "YJL03G10A-F2-0000HF"))
    )
    (comp (ref "Q7")
      (value "YJL03G10A-F2-0000HF")
      (fields (field (name "BOM_Supplier Part") "C919604"))
      (libsource (lib "") (part "YJL03G10A-F2-0000HF"))
    )
    (comp (ref "Q8")
      (value "YJL03G10A-F2-0000HF")
      (fields (field (name "BOM_Supplier Part") "C919604"))
      (libsource (lib "") (part "YJL03G10A-F2-0000HF"))
    )
    (comp (ref "Q9")
      (value "YJL03G10A-F2-0000HF")
      (fields (field (name "BOM_Supplier Part") "C919604"))
      (libsource (lib "") (part "YJL03G10A-F2-0000HF"))
    )
    (comp (ref "R1") (value "47k") (libsource (lib "") (part "R_0603_EU")))
    (comp (ref "R2") (value "270") (libsource (lib "") (part "R_0603_EU_3")))
    (comp (ref "R3") (value "47k") (libsource (lib "") (part "R_0603_EU")))
    (comp (ref "R4") (value "47k") (libsource (lib "") (part "R_0603_EU")))
    (comp (ref "R5") (value "47k") (libsource (lib "") (part "R_0603_EU")))
    (comp (ref "R6") (value "47k") (libsource (lib "") (part "R_0603_EU_2")))
    (comp (ref "RS1") (value "47k") (libsource (lib "") (part "R_0603_EU_1")))
    (comp (ref "RS2") (value "47k") (libsource (lib "") (part "R_0603_EU_1")))
    (comp (ref "RS3") (value "47k") (libsource (lib "") (part "R_0603_EU_1")))
    (comp (ref "RS4") (value "47k") (libsource (lib "") (part "R_0603_EU_1")))
    (comp (ref "RS5") (value "47k") (libsource (lib "") (part "R_0603_EU_1")))
    (comp (ref "RS6") (value "47k") (libsource (lib "") (part "R_0603_EU_1")))
    (comp (ref "RS7") (value "47k") (libsource (lib "") (part "R_0603_EU_1")))
    (comp (ref "RS8") (value "47k") (libsource (lib "") (part "R_0603_EU_1")))
    (comp (ref "RS9") (value "47k") (libsource (lib "") (part "R_0603_EU_1")))
    (comp (ref "U1")
      (value "PIC16F18877-I/PT")
      (fields (field (name "BOM_Supplier Part") "C81835"))
      (libsource (lib "") (part "PIC16F18877-I/PT"))
    )
    (comp (ref "U2") (value "LDLN030G33R") (libsource (lib "") (part "LDLN030G33R")))
    (comp (ref "U3") (value "STM1061N19WX6F") (libsource (lib "") (part "STM1061N19WX6F")))
    (comp (ref "U4") (value "BM71BLES1FC2-0B04AA") (libsource (lib "") (part "BM71BLES1FC2-0B04AA")))
    (comp (ref "USB1")
      (value "47346-0001")
      (fields (field (name "BOM_Supplier Part") "C132560"))
      (libsource (lib "") (part "47346-0001"))
    )
    (comp (ref "MA1")
      (value "SN74LV4051ADR")
      (fields (field (name "BOM_Supplier Part") "C128414"))
      (libsource (lib "") (part "SN74LV4051ADR_1"))
    )
    (comp (ref "MA2")
      (value "SN74LV4051ADR")
      (fields (field (name "BOM_Supplier Part") "C128414"))
      (libsource (lib "") (part "SN74LV4051ADR_1"))
    )
    (comp (ref "MA3")
      (value "SN74LV4051ADR")
      (fields (field (name "BOM_Supplier Part") "C128414"))
      (libsource (lib "") (part "SN74LV4051ADR_1"))
    )
    (comp (ref "MA4")
      (value "SN74LV4051ADR")
      (fields (field (name "BOM_Supplier Part") "C128414"))
      (libsource (lib "") (part "SN74LV4051ADR_1"))
    )
    (comp (ref "MA5")
      (value "SN74LV4051ADR")
      (fields (field (name "BOM_Supplier Part") "C128414"))
      (libsource (lib "") (part "SN74LV4051ADR_1"))
    )
    (comp (ref "MA6")
      (value "SN74LV4051ADR")
      (fields (field (name "BOM_Supplier Part") "C128414"))
      (libsource (lib "") (part "SN74LV4051ADR_1"))
    )
    (comp (ref "MA7")
      (value "SN74LV4051ADR")
      (fields (field (name "BOM_Supplier Part") "C128414"))
      (libsource (lib "") (part "SN74LV4051ADR_1"))
    )
    (comp (ref "MA8")
      (value "SN74LV4051ADR")
      (fields (field (name "BOM_Supplier Part") "C128414"))
      (libsource (lib "") (part "SN74LV4051ADR_1"))
    )
    (comp (ref "MA9")
      (value "SN74LV4051ADR")
      (fields (field (name "BOM_Supplier Part") "C128414"))
      (libsource (lib "") (part "SN74LV4051ADR_1"))
    )
    (comp (ref "MA10")
      (value "SN74LV4051ADR")
      (fields (field (name "BOM_Supplier Part") "C128414"))
      (libsource (lib "") (part "SN74LV4051ADR_1"))
    )
    (comp (ref "MA11")
      (value "SN74LV4051ADR")
      (fields (field (name "BOM_Supplier Part") "C128414"))
      (libsource (lib "") (part "SN74LV4051ADR_1"))
    )
    (comp (ref "ML1")
      (value "SN74LV4051ADR")
      (fields (field (name "BOM_Supplier Part") "C128414"))
      (libsource (lib "") (part "SN74LV4051ADR"))
    )
    (comp (ref "ML2")
      (value "SN74LV4051ADR")
      (fields (field (name "BOM_Supplier Part") "C128414"))
      (libsource (lib "") (part "SN74LV4051ADR"))
    )
    (comp (ref "ML3")
      (value "SN74LV4051ADR")
      (fields (field (name "BOM_Supplier Part") "C128414"))
      (libsource (lib "") (part "SN74LV4051ADR"))
    )
    (comp (ref "ML4")
      (value "SN74LV4051ADR")
      (fields (field (name "BOM_Supplier Part") "C128414"))
      (libsource (lib "") (part "SN74LV4051ADR"))
    )
    (comp (ref "ML5")
      (value "SN74LV4051ADR")
      (fields (field (name "BOM_Supplier Part") "C128414"))
      (libsource (lib "") (part "SN74LV4051ADR"))
    )
    (comp (ref "ML6")
      (value "SN74LV4051ADR")
      (fields (field (name "BOM_Supplier Part") "C128414"))
      (libsource (lib "") (part "SN74LV4051ADR"))
    )
    (comp (ref "ML7")
      (value "SN74LV4051ADR")
      (fields (field (name "BOM_Supplier Part") "C128414"))
      (libsource (lib "") (part "SN74LV4051ADR"))
    )
    (comp (ref "ML8")
      (value "SN74LV4051ADR")
      (fields (field (name "BOM_Supplier Part") "C128414"))
      (libsource (lib "") (part "SN74LV4051ADR"))
    )
    (comp (ref "ML9")
      (value "SN74LV4051ADR")
      (fields (field (name "BOM_Supplier Part") "C128414"))
      (libsource (lib "") (part "SN74LV4051ADR"))
    )
    (comp (ref "ML10")
      (value "SN74LV4051ADR")
      (fields (field (name "BOM_Supplier Part") "C128414"))
      (libsource (lib "") (part "SN74LV4051ADR"))
    )
    (comp (ref "ML11")
      (value "SN74LV4051ADR")
      (fields (field (name "BOM_Supplier Part") "C128414"))
      (libsource (lib "") (part "SN74LV4051ADR"))
    )
    (comp (ref "RLD11") (value "270") (libsource (lib "") (part "R_0603_EU_1")))
    (comp (ref "RLD12") (value "270") (libsource (lib "") (part "R_0603_EU_1")))
    (comp (ref "RLD13") (value "270") (libsource (lib "") (part "R_0603_EU_1")))
    (comp (ref "RLD14") (value "270") (libsource (lib "") (part "R_0603_EU_2")))
    (comp (ref "RLD15") (value "270") (libsource (lib "") (part "R_0603_EU_2")))
    (comp (ref "RLD16") (value "270") (libsource (lib "") (part "R_0603_EU_2")))
    (comp (ref "RLD17") (value "270") (libsource (lib "") (part "R_0603_EU_2")))
    (comp (ref "RLD18") (value "270") (libsource (lib "") (part "R_0603_EU_2")))
    (comp (ref "RLD19") (value "270") (libsource (lib "") (part "R_0603_EU_2")))
    (comp (ref "RLD21") (value "270") (libsource (lib "") (part "R_0603_EU_1")))
    (comp (ref "RLD22") (value "270") (libsource (lib "") (part "R_0603_EU_1")))
    (comp (ref "RLD23") (value "270") (libsource (lib "") (part "R_0603_EU_1")))
    (comp (ref "RLD24") (value "270") (libsource (lib "") (part "R_0603_EU_1")))
    (comp (ref "RLD25") (value "270") (libsource (lib "") (part "R_0603_EU_1")))
    (comp (ref "RLD26") (value "270") (libsource (lib "") (part "R_0603_EU_1")))
    (comp (ref "RLD27") (value "270") (libsource (lib "") (part "R_0603_EU_1")))
    (comp (ref "RLD28") (value "270") (libsource (lib "") (part "R_0603_EU_1")))
    (comp (ref "RLD29") (value "270") (libsource (lib "") (part "R_0603_EU_1")))
    (comp (ref "RLU11") (value "47k") (libsource (lib "") (part "R_0603_EU")))
    (comp (ref "RLU12") (value "47k") (libsource (lib "") (part "R_0603_EU")))
    (comp (ref "RLU13") (value "47k") (libsource (lib "") (part "R_0603_EU")))
    (comp (ref "RLU14") (value "47k") (libsource (lib "") (part "R_0603_EU_3")))
    (comp (ref "RLU15") (value "47k") (libsource (lib "") (part "R_0603_EU_3")))
    (comp (ref "RLU16") (value "47k") (libsource (lib "") (part "R_0603_EU_3")))
    (comp (ref "RLU17") (value "47k") (libsource (lib "") (part "R_0603_EU_3")))
    (comp (ref "RLU18") (value "47k") (libsource (lib "") (part "R_0603_EU_3")))
    (comp (ref "RLU19") (value "47k") (libsource (lib "") (part "R_0603_EU_3")))
    (comp (ref "RLU21") (value "47k") (libsource (lib "") (part "R_0603_EU")))
    (comp (ref "RLU22") (value "47k") (libsource (lib "") (part "R_0603_EU")))
    (comp (ref "RLU23") (value "47k") (libsource (lib "") (part "R_0603_EU")))
    (comp (ref "RLU24") (value "47k") (libsource (lib "") (part "R_0603_EU")))
    (comp (ref "RLU25") (value "47k") (libsource (lib "") (part "R_0603_EU")))
    (comp (ref "RLU26") (value "47k") (libsource (lib "") (part "R_0603_EU")))
    (comp (ref "RLU27") (value "47k") (libsource (lib "") (part "R_0603_EU_3")))
    (comp (ref "RLU28") (value "47k") (libsource (lib "") (part "R_0603_EU_3")))
    (comp (ref "RLU29") (value "47k") (libsource (lib "") (part "R_0603_EU_3")))
    (comp (ref "RPR11")
      (value "RPR-220")
      (fields (field (name "BOM_Supplier Part") "C21062"))
      (libsource (lib "") (part "RPR-220"))
    )
    (comp (ref "RPR12")
      (value "RPR-220")
      (fields (field (name "BOM_Supplier Part") "C21062"))
      (libsource (lib "") (part "RPR-220"))
    )
    (comp (ref "RPR13")
      (value "RPR-220")
      (fields (field (name "BOM_Supplier Part") "C21062"))
      (libsource (lib "") (part "RPR-220"))
    )
    (comp (ref "RPR14")
      (value "RPR-220")
      (fields (field (name "BOM_Supplier Part") "C21062"))
      (libsource (lib "") (part "RPR-220"))
    )
    (comp (ref "RPR15")
      (value "RPR-220")
      (fields (field (name "BOM_Supplier Part") "C21062"))
      (libsource (lib "") (part "RPR-220"))
    )
    (comp (ref "RPR16")
      (value "RPR-220")
      (fields (field (name "BOM_Supplier Part") "C21062"))
      (libsource (lib "") (part "RPR-220"))
    )
    (comp (ref "RPR17")
      (value "RPR-220")
      (fields (field (name "BOM_Supplier Part") "C21062"))
      (libsource (lib "") (part "RPR-220"))
    )
    (comp (ref "RPR18")
      (value "RPR-220")
      (fields (field (name "BOM_Supplier Part") "C21062"))
      (libsource (lib "") (part "RPR-220"))
    )
    (comp (ref "RPR19")
      (value "RPR-220")
      (fields (field (name "BOM_Supplier Part") "C21062"))
      (libsource (lib "") (part "RPR-220"))
    )
    (comp (ref "RPR21")
      (value "RPR-220")
      (fields (field (name "BOM_Supplier Part") "C21062"))
      (libsource (lib "") (part "RPR-220"))
    )
    (comp (ref "RPR22")
      (value "RPR-220")
      (fields (field (name "BOM_Supplier Part") "C21062"))
      (libsource (lib "") (part "RPR-220"))
    )
    (comp (ref "RPR23")
      (value "RPR-220")
      (fields (field (name "BOM_Supplier Part") "C21062"))
      (libsource (lib "") (part "RPR-220"))
    )
    (comp (ref "RPR24")
      (value "RPR-220")
      (fields (field (name "BOM_Supplier Part") "C21062"))
      (libsource (lib "") (part "RPR-220"))
    )
    (comp (ref "RPR25")
      (value "RPR-220")
      (fields (field (name "BOM_Supplier Part") "C21062"))
      (libsource (lib "") (part "RPR-220"))
    )
    (comp (ref "RPR26")
      (value "RPR-220")
      (fields (field (name "BOM_Supplier Part") "C21062"))
      (libsource (lib "") (part "RPR-220"))
    )
    (comp (ref "RPR27")
      (value "RPR-220")
      (fields (field (name "BOM_Supplier Part") "C21062"))
      (libsource (lib "") (part "RPR-220"))
    )
    (comp (ref "RPR28")
      (value "RPR-220")
      (fields (field (name "BOM_Supplier Part") "C21062"))
      (libsource (lib "") (part "RPR-220"))
    )
    (comp (ref "RPR29")
      (value "RPR-220")
      (fields (field (name "BOM_Supplier Part") "C21062"))
      (libsource (lib "") (part "RPR-220"))
    )
    (comp (ref "RLD31") (value "270") (libsource (lib "") (part "R_0603_EU")))
    (comp (ref "RLD32") (value "270") (libsource (lib "") (part "R_0603_EU")))
    (comp (ref "RLD33") (value "270") (libsource (lib "") (part "R_0603_EU")))
    (comp (ref "RLD34") (value "270") (libsource (lib "") (part "R_0603_EU")))
    (comp (ref "RLD35") (value "270") (libsource (lib "") (part "R_0603_EU")))
    (comp (ref "RLD36") (value "270") (libsource (lib "") (part "R_0603_EU")))
    (comp (ref "RLD37") (value "270") (libsource (lib "") (part "R_0603_EU")))
    (comp (ref "RLD38") (value "270") (libsource (lib "") (part "R_0603_EU")))
    (comp (ref "RLD39") (value "270") (libsource (lib "") (part "R_0603_EU")))
    (comp (ref "RLD41") (value "270") (libsource (lib "") (part "R_0603_EU_2")))
    (comp (ref "RLD42") (value "270") (libsource (lib "") (part "R_0603_EU_2")))
    (comp (ref "RLD43") (value "270") (libsource (lib "") (part "R_0603_EU_2")))
    (comp (ref "RLD44") (value "270") (libsource (lib "") (part "R_0603_EU_2")))
    (comp (ref "RLD45") (value "270") (libsource (lib "") (part "R_0603_EU_2")))
    (comp (ref "RLD46") (value "270") (libsource (lib "") (part "R_0603_EU_2")))
    (comp (ref "RLD47") (value "270") (libsource (lib "") (part "R_0603_EU_2")))
    (comp (ref "RLD48") (value "270") (libsource (lib "") (part "R_0603_EU_2")))
    (comp (ref "RLD49") (value "270") (libsource (lib "") (part "R_0603_EU_2")))
    (comp (ref "RLU31") (value "47k") (libsource (lib "") (part "R_0603_EU_3")))
    (comp (ref "RLU32") (value "47k") (libsource (lib "") (part "R_0603_EU_3")))
    (comp (ref "RLU33") (value "47k") (libsource (lib "") (part "R_0603_EU_3")))
    (comp (ref "RLU34") (value "47k") (libsource (lib "") (part "R_0603_EU_1")))
    (comp (ref "RLU35") (value "47k") (libsource (lib "") (part "R_0603_EU_1")))
    (comp (ref "RLU36") (value "47k") (libsource (lib "") (part "R_0603_EU_1")))
    (comp (ref "RLU37") (value "47k") (libsource (lib "") (part "R_0603_EU_1")))
    (comp (ref "RLU38") (value "47k") (libsource (lib "") (part "R_0603_EU_1")))
    (comp (ref "RLU39") (value "47k") (libsource (lib "") (part "R_0603_EU_1")))
    (comp (ref "RLU41") (value "47k") (libsource (lib "") (part "R_0603_EU_3")))
    (comp (ref "RLU42") (value "47k") (libsource (lib "") (part "R_0603_EU_3")))
    (comp (ref "RLU43") (value "47k") (libsource (lib "") (part "R_0603_EU_3")))
    (comp (ref "RLU44") (value "47k") (libsource (lib "") (part "R_0603_EU_3")))
    (comp (ref "RLU45") (value "47k") (libsource (lib "") (part "R_0603_EU_3")))
    (comp (ref "RLU46") (value "47k") (libsource (lib "") (part "R_0603_EU_3")))
    (comp (ref "RLU47") (value "47k") (libsource (lib "") (part "R_0603_EU_1")))
    (comp (ref "RLU48") (value "47k") (libsource (lib "") (part "R_0603_EU_1")))
    (comp (ref "RLU49") (value "47k") (libsource (lib "") (part "R_0603_EU_1")))
    (comp (ref "RPR31")
      (value "RPR-220")
      (fields (field (name "BOM_Supplier Part") "C21062"))
      (libsource (lib "") (part "RPR-220"))
    )
    (comp (ref "RPR32")
      (value "RPR-220")
      (fields (field (name "BOM_Supplier Part") "C21062"))
      (libsource (lib "") (part "RPR-220"))
    )
    (comp (ref "RPR33")
      (value "RPR-220")
      (fields (field (name "BOM_Supplier Part") "C21062"))
      (libsource (lib "") (part "RPR-220"))
    )
    (comp (ref "RPR34")
      (value "RPR-220")
      (fields (field (name "BOM_Supplier Part") "C21062"))
      (libsource (lib "") (part "RPR-220"))
    )
    (comp (ref "RPR35")
      (value "RPR-220")
      (fields (field (name "BOM_Supplier Part") "C21062"))
      (libsource (lib "") (part "RPR-220"))
    )
    (comp (ref "RPR36")
      (value "RPR-220")
      (fields (field (name "BOM_Supplier Part") "C21062"))
      (libsource (lib "") (part "RPR-220"))
    )
    (comp (ref "RPR37")
      (value "RPR-220")
      (fields (field (name "BOM_Supplier Part") "C21062"))
      (libsource (lib "") (part "RPR-220"))
    )
    (comp (ref "RPR38")
      (value "RPR-220")
      (fields (field (name "BOM_Supplier Part") "C21062"))
      (libsource (lib "") (part "RPR-220"))
    )
    (comp (ref "RPR39")
      (value "RPR-220")
      (fields (field (name "BOM_Supplier Part") "C21062"))
      (libsource (lib "") (part "RPR-220"))
    )
    (comp (ref "RPR41")
      (value "RPR-220")
      (fields (field (name "BOM_Supplier Part") "C21062"))
      (libsource (lib "") (part "RPR-220"))
    )
    (comp (ref "RPR42")
      (value "RPR-220")
      (fields (field (name "BOM_Supplier Part") "C21062"))
      (libsource (lib "") (part "RPR-220"))
    )
    (comp (ref "RPR43")
      (value "RPR-220")
      (fields (field (name "BOM_Supplier Part") "C21062"))
      (libsource (lib "") (part "RPR-220"))
    )
    (comp (ref "RPR44")
      (value "RPR-220")
      (fields (field (name "BOM_Supplier Part") "C21062"))
      (libsource (lib "") (part "RPR-220"))
    )
    (comp (ref "RPR45")
      (value "RPR-220")
      (fields (field (name "BOM_Supplier Part") "C21062"))
      (libsource (lib "") (part "RPR-220"))
    )
    (comp (ref "RPR46")
      (value "RPR-220")
      (fields (field (name "BOM_Supplier Part") "C21062"))
      (libsource (lib "") (part "RPR-220"))
    )
    (comp (ref "RPR47")
      (value "RPR-220")
      (fields (field (name "BOM_Supplier Part") "C21062"))
      (libsource (lib "") (part "RPR-220"))
    )
    (comp (ref "RPR48")
      (value "RPR-220")
      (fields (field (name "BOM_Supplier Part") "C21062"))
      (libsource (lib "") (part "RPR-220"))
    )
    (comp (ref "RPR49")
      (value "RPR-220")
      (fields (field (name "BOM_Supplier Part") "C21062"))
      (libsource (lib "") (part "RPR-220"))
    )
    (comp (ref "RLD51") (value "270") (libsource (lib "") (part "R_0603_EU_2")))
    (comp (ref "RLD52") (value "270") (libsource (lib "") (part "R_0603_EU_2")))
    (comp (ref "RLD53") (value "270") (libsource (lib "") (part "R_0603_EU_2")))
    (comp (ref "RLD54") (value "270") (libsource (lib "") (part "R_0603_EU_2")))
    (comp (ref "RLD55") (value "270") (libsource (lib "") (part "R_0603_EU_2")))
    (comp (ref "RLD56") (value "270") (libsource (lib "") (part "R_0603_EU_2")))
    (comp (ref "RLD57") (value "270") (libsource (lib "") (part "R_0603_EU_2")))
    (comp (ref "RLD58") (value "270") (libsource (lib "") (part "R_0603_EU_2")))
    (comp (ref "RLD59") (value "270") (libsource (lib "") (part "R_0603_EU_2")))
    (comp (ref "RLD61") (value "270") (libsource (lib "") (part "R_0603_EU_1")))
    (comp (ref "RLD62") (value "270") (libsource (lib "") (part "R_0603_EU_1")))
    (comp (ref "RLD63") (value "270") (libsource (lib "") (part "R_0603_EU_1")))
    (comp (ref "RLD64") (value "270") (libsource (lib "") (part "R_0603_EU_1")))
    (comp (ref "RLD65") (value "270") (libsource (lib "") (part "R_0603_EU_1")))
    (comp (ref "RLD66") (value "270") (libsource (lib "") (part "R_0603_EU_1")))
    (comp (ref "RLD67") (value "270") (libsource (lib "") (part "R_0603_EU_1")))
    (comp (ref "RLD68") (value "270") (libsource (lib "") (part "R_0603_EU_1")))
    (comp (ref "RLD69") (value "270") (libsource (lib "") (part "R_0603_EU_1")))
    (comp (ref "RLU51") (value "47k") (libsource (lib "") (part "R_0603_EU_3")))
    (comp (ref "RLU52") (value "47k") (libsource (lib "") (part "R_0603_EU_3")))
    (comp (ref "RLU53") (value "47k") (libsource (lib "") (part "R_0603_EU_3")))
    (comp (ref "RLU54") (value "47k") (libsource (lib "") (part "R_0603_EU")))
    (comp (ref "RLU55") (value "47k") (libsource (lib "") (part "R_0603_EU")))
    (comp (ref "RLU56") (value "47k") (libsource (lib "") (part "R_0603_EU")))
    (comp (ref "RLU57") (value "47k") (libsource (lib "") (part "R_0603_EU")))
    (comp (ref "RLU58") (value "47k") (libsource (lib "") (part "R_0603_EU")))
    (comp (ref "RLU59") (value "47k") (libsource (lib "") (part "R_0603_EU")))
    (comp (ref "RLU61") (value "47k") (libsource (lib "") (part "R_0603_EU_3")))
    (comp (ref "RLU62") (value "47k") (libsource (lib "") (part "R_0603_EU_3")))
    (comp (ref "RLU63") (value "47k") (libsource (lib "") (part "R_0603_EU_3")))
    (comp (ref "RLU64") (value "47k") (libsource (lib "") (part "R_0603_EU_3")))
    (comp (ref "RLU65") (value "47k") (libsource (lib "") (part "R_0603_EU_3")))
    (comp (ref "RLU66") (value "47k") (libsource (lib "") (part "R_0603_EU_3")))
    (comp (ref "RLU67") (value "47k") (libsource (lib "") (part "R_0603_EU")))
    (comp (ref "RLU68") (value "47k") (libsource (lib "") (part "R_0603_EU")))
    (comp (ref "RLU69") (value "47k") (libsource (lib "") (part "R_0603_EU")))
    (comp (ref "RPR51")
      (value "RPR-220")
      (fields (field (name "BOM_Supplier Part") "C21062"))
      (libsource (lib "") (part "RPR-220"))
    )
    (comp (ref "RPR52")
      (value "RPR-220")
      (fields (field (name "BOM_Supplier Part") "C21062"))
      (libsource (lib "") (part "RPR-220"))
    )
    (comp (ref "RPR53")
      (value "RPR-220")
      (fields (field (name "BOM_Supplier Part") "C21062"))
      (libsource (lib "") (part "RPR-220"))
    )
    (comp (ref "RPR54")
      (value "RPR-220")
      (fields (field (name "BOM_Supplier Part") "C21062"))
      (libsource (lib "") (part "RPR-220"))
    )
    (comp (ref "RPR55")
      (value "RPR-220")
      (fields (field (name "BOM_Supplier Part") "C21062"))
      (libsource (lib "") (part "RPR-220"))
    )
    (comp (ref "RPR56")
      (value "RPR-220")
      (fields (field (name "BOM_Supplier Part") "C21062"))
      (libsource (lib "") (part "RPR-220"))
    )
    (comp (ref "RPR57")
      (value "RPR-220")
      (fields (field (name "BOM_Supplier Part") "C21062"))
      (libsource (lib "") (part "RPR-220"))
    )
    (comp (ref "RPR58")
      (value "RPR-220")
      (fields (field (name "BOM_Supplier Part") "C21062"))
      (libsource (lib "") (part "RPR-220"))
    )
    (comp (ref "RPR59")
      (value "RPR-220")
      (fields (field (name "BOM_Supplier Part") "C21062"))
      (libsource (lib "") (part "RPR-220"))
    )
    (comp (ref "RPR61")
      (value "RPR-220")
      (fields (field (name "BOM_Supplier Part") "C21062"))
      (libsource (lib "") (part "RPR-220"))
    )
    (comp (ref "RPR62")
      (value "RPR-220")
      (fields (field (name "BOM_Supplier Part") "C21062"))
      (libsource (lib "") (part "RPR-220"))
    )
    (comp (ref "RPR63")
      (value "RPR-220")
      (fields (field (name "BOM_Supplier Part") "C21062"))
      (libsource (lib "") (part "RPR-220"))
    )
    (comp (ref "RPR64")
      (value "RPR-220")
      (fields (field (name "BOM_Supplier Part") "C21062"))
      (libsource (lib "") (part "RPR-220"))
    )
    (comp (ref "RPR65")
      (value "RPR-220")
      (fields (field (name "BOM_Supplier Part") "C21062"))
      (libsource (lib "") (part "RPR-220"))
    )
    (comp (ref "RPR66")
      (value "RPR-220")
      (fields (field (name "BOM_Supplier Part") "C21062"))
      (libsource (lib "") (part "RPR-220"))
    )
    (comp (ref "RPR67")
      (value "RPR-220")
      (fields (field (name "BOM_Supplier Part") "C21062"))
      (libsource (lib "") (part "RPR-220"))
    )
    (comp (ref "RPR68")
      (value "RPR-220")
      (fields (field (name "BOM_Supplier Part") "C21062"))
      (libsource (lib "") (part "RPR-220"))
    )
    (comp (ref "RPR69")
      (value "RPR-220")
      (fields (field (name "BOM_Supplier Part") "C21062"))
      (libsource (lib "") (part "RPR-220"))
    )
    (comp (ref "RLD71") (value "270") (libsource (lib "") (part "R_0603_EU_3")))
    (comp (ref "RLD72") (value "270") (libsource (lib "") (part "R_0603_EU_3")))
    (comp (ref "RLD73") (value "270") (libsource (lib "") (part "R_0603_EU_3")))
    (comp (ref "RLD74") (value "270") (libsource (lib "") (part "R_0603_EU_3")))
    (comp (ref "RLD75") (value "270") (libsource (lib "") (part "R_0603_EU_3")))
    (comp (ref "RLD76") (value "270") (libsource (lib "") (part "R_0603_EU_3")))
    (comp (ref "RLD77") (value "270") (libsource (lib "") (part "R_0603_EU_3")))
    (comp (ref "RLD78") (value "270") (libsource (lib "") (part "R_0603_EU_3")))
    (comp (ref "RLD79") (value "270") (libsource (lib "") (part "R_0603_EU_3")))
    (comp (ref "RLD81") (value "270") (libsource (lib "") (part "R_0603_EU_1")))
    (comp (ref "RLD82") (value "270") (libsource (lib "") (part "R_0603_EU_1")))
    (comp (ref "RLD83") (value "270") (libsource (lib "") (part "R_0603_EU_1")))
    (comp (ref "RLD84") (value "270") (libsource (lib "") (part "R_0603_EU_1")))
    (comp (ref "RLD85") (value "270") (libsource (lib "") (part "R_0603_EU_1")))
    (comp (ref "RLD86") (value "270") (libsource (lib "") (part "R_0603_EU_1")))
    (comp (ref "RLD87") (value "270") (libsource (lib "") (part "R_0603_EU_1")))
    (comp (ref "RLD88") (value "270") (libsource (lib "") (part "R_0603_EU_1")))
    (comp (ref "RLD89") (value "270") (libsource (lib "") (part "R_0603_EU_1")))
    (comp (ref "RLU71") (value "47k") (libsource (lib "") (part "R_0603_EU_2")))
    (comp (ref "RLU72") (value "47k") (libsource (lib "") (part "R_0603_EU_2")))
    (comp (ref "RLU73") (value "47k") (libsource (lib "") (part "R_0603_EU_2")))
    (comp (ref "RLU74") (value "47k") (libsource (lib "") (part "R_0603_EU")))
    (comp (ref "RLU75") (value "47k") (libsource (lib "") (part "R_0603_EU")))
    (comp (ref "RLU76") (value "47k") (libsource (lib "") (part "R_0603_EU")))
    (comp (ref "RLU77") (value "47k") (libsource (lib "") (part "R_0603_EU")))
    (comp (ref "RLU78") (value "47k") (libsource (lib "") (part "R_0603_EU")))
    (comp (ref "RLU79") (value "47k") (libsource (lib "") (part "R_0603_EU")))
    (comp (ref "RLU81") (value "47k") (libsource (lib "") (part "R_0603_EU_2")))
    (comp (ref "RLU82") (value "47k") (libsource (lib "") (part "R_0603_EU_2")))
    (comp (ref "RLU83") (value "47k") (libsource (lib "") (part "R_0603_EU_2")))
    (comp (ref "RLU84") (value "47k") (libsource (lib "") (part "R_0603_EU_2")))
    (comp (ref "RLU85") (value "47k") (libsource (lib "") (part "R_0603_EU_2")))
    (comp (ref "RLU86") (value "47k") (libsource (lib "") (part "R_0603_EU_2")))
    (comp (ref "RLU87") (value "47k") (libsource (lib "") (part "R_0603_EU")))
    (comp (ref "RLU88") (value "47k") (libsource (lib "") (part "R_0603_EU")))
    (comp (ref "RLU89") (value "47k") (libsource (lib "") (part "R_0603_EU")))
    (comp (ref "RPR71")
      (value "RPR-220")
      (fields (field (name "BOM_Supplier Part") "C21062"))
      (libsource (lib "") (part "RPR-220"))
    )
    (comp (ref "RPR72")
      (value "RPR-220")
      (fields (field (name "BOM_Supplier Part") "C21062"))
      (libsource (lib "") (part "RPR-220"))
    )
    (comp (ref "RPR73")
      (value "RPR-220")
      (fields (field (name "BOM_Supplier Part") "C21062"))
      (libsource (lib "") (part "RPR-220"))
    )
    (comp (ref "RPR74")
      (value "RPR-220")
      (fields (field (name "BOM_Supplier Part") "C21062"))
      (libsource (lib "") (part "RPR-220"))
    )
    (comp (ref "RPR75")
      (value "RPR-220")
      (fields (field (name "BOM_Supplier Part") "C21062"))
      (libsource (lib "") (part "RPR-220"))
    )
    (comp (ref "RPR76")
      (value "RPR-220")
      (fields (field (name "BOM_Supplier Part") "C21062"))
      (libsource (lib "") (part "RPR-220"))
    )
    (comp (ref "RPR77")
      (value "RPR-220")
      (fields (field (name "BOM_Supplier Part") "C21062"))
      (libsource (lib "") (part "RPR-220"))
    )
    (comp (ref "RPR78")
      (value "RPR-220")
      (fields (field (name "BOM_Supplier Part") "C21062"))
      (libsource (lib "") (part "RPR-220"))
    )
    (comp (ref "RPR79")
      (value "RPR-220")
      (fields (field (name "BOM_Supplier Part") "C21062"))
      (libsource (lib "") (part "RPR-220"))
    )
    (comp (ref "RPR81")
      (value "RPR-220")
      (fields (field (name "BOM_Supplier Part") "C21062"))
      (libsource (lib "") (part "RPR-220"))
    )
    (comp (ref "RPR82")
      (value "RPR-220")
      (fields (field (name "BOM_Supplier Part") "C21062"))
      (libsource (lib "") (part "RPR-220"))
    )
    (comp (ref "RPR83")
      (value "RPR-220")
      (fields (field (name "BOM_Supplier Part") "C21062"))
      (libsource (lib "") (part "RPR-220"))
    )
    (comp (ref "RPR84")
      (value "RPR-220")
      (fields (field (name "BOM_Supplier Part") "C21062"))
      (libsource (lib "") (part "RPR-220"))
    )
    (comp (ref "RPR85")
      (value "RPR-220")
      (fields (field (name "BOM_Supplier Part") "C21062"))
      (libsource (lib "") (part "RPR-220"))
    )
    (comp (ref "RPR86")
      (value "RPR-220")
      (fields (field (name "BOM_Supplier Part") "C21062"))
      (libsource (lib "") (part "RPR-220"))
    )
    (comp (ref "RPR87")
      (value "RPR-220")
      (fields (field (name "BOM_Supplier Part") "C21062"))
      (libsource (lib "") (part "RPR-220"))
    )
    (comp (ref "RPR88")
      (value "RPR-220")
      (fields (field (name "BOM_Supplier Part") "C21062"))
      (libsource (lib "") (part "RPR-220"))
    )
    (comp (ref "RPR89")
      (value "RPR-220")
      (fields (field (name "BOM_Supplier Part") "C21062"))
      (libsource (lib "") (part "RPR-220"))
    )
    (comp (ref "RLD91") (value "270") (libsource (lib "") (part "R_0603_EU")))
    (comp (ref "RLD92") (value "270") (libsource (lib "") (part "R_0603_EU")))
    (comp (ref "RLD93") (value "270") (libsource (lib "") (part "R_0603_EU")))
    (comp (ref "RLD94") (value "270") (libsource (lib "") (part "R_0603_EU")))
    (comp (ref "RLD95") (value "270") (libsource (lib "") (part "R_0603_EU")))
    (comp (ref "RLD96") (value "270") (libsource (lib "") (part "R_0603_EU")))
    (comp (ref "RLD97") (value "270") (libsource (lib "") (part "R_0603_EU")))
    (comp (ref "RLD98") (value "270") (libsource (lib "") (part "R_0603_EU")))
    (comp (ref "RLD99") (value "270") (libsource (lib "") (part "R_0603_EU")))
    (comp (ref "RLU91") (value "47k") (libsource (lib "") (part "R_0603_EU_1")))
    (comp (ref "RLU92") (value "47k") (libsource (lib "") (part "R_0603_EU_1")))
    (comp (ref "RLU93") (value "47k") (libsource (lib "") (part "R_0603_EU_1")))
    (comp (ref "RLU94") (value "47k") (libsource (lib "") (part "R_0603_EU_2")))
    (comp (ref "RLU95") (value "47k") (libsource (lib "") (part "R_0603_EU_2")))
    (comp (ref "RLU96") (value "47k") (libsource (lib "") (part "R_0603_EU_2")))
    (comp (ref "RLU97") (value "47k") (libsource (lib "") (part "R_0603_EU_2")))
    (comp (ref "RLU98") (value "47k") (libsource (lib "") (part "R_0603_EU_2")))
    (comp (ref "RLU99") (value "47k") (libsource (lib "") (part "R_0603_EU_2")))
    (comp (ref "RPR91")
      (value "RPR-220")
      (fields (field (name "BOM_Supplier Part") "C21062"))
      (libsource (lib "") (part "RPR-220"))
    )
    (comp (ref "RPR92")
      (value "RPR-220")
      (fields (field (name "BOM_Supplier Part") "C21062"))
      (libsource (lib "") (part "RPR-220"))
    )
    (comp (ref "RPR93")
      (value "RPR-220")
      (fields (field (name "BOM_Supplier Part") "C21062"))
      (libsource (lib "") (part "RPR-220"))
    )
    (comp (ref "RPR94")
      (value "RPR-220")
      (fields (field (name "BOM_Supplier Part") "C21062"))
      (libsource (lib "") (part "RPR-220"))
    )
    (comp (ref "RPR95")
      (value "RPR-220")
      (fields (field (name "BOM_Supplier Part") "C21062"))
      (libsource (lib "") (part "RPR-220"))
    )
    (comp (ref "RPR96")
      (value "RPR-220")
      (fields (field (name "BOM_Supplier Part") "C21062"))
      (libsource (lib "") (part "RPR-220"))
    )
    (comp (ref "RPR97")
      (value "RPR-220")
      (fields (field (name "BOM_Supplier Part") "C21062"))
      (libsource (lib "") (part "RPR-220"))
    )
    (comp (ref "RPR98")
      (value "RPR-220")
      (fields (field (name "BOM_Supplier Part") "C21062"))
      (libsource (lib "") (part "RPR-220"))
    )
    (comp (ref "RPR99")
      (value "RPR-220")
      (fields (field (name "BOM_Supplier Part") "C21062"))
      (libsource (lib "") (part "RPR-220"))
    )
    (comp (ref "RA11")
      (value "GL5549")
      (fields (field (name "BOM_Supplier Part") "C125631"))
      (libsource (lib "") (part "GL5549"))
    )
    (comp (ref "RA12")
      (value "GL5549")
      (fields (field (name "BOM_Supplier Part") "C125631"))
      (libsource (lib "") (part "GL5549"))
    )
    (comp (ref "RA13")
      (value "GL5549")
      (fields (field (name "BOM_Supplier Part") "C125631"))
      (libsource (lib "") (part "GL5549"))
    )
    (comp (ref "RA14")
      (value "GL5549")
      (fields (field (name "BOM_Supplier Part") "C125631"))
      (libsource (lib "") (part "GL5549"))
    )
    (comp (ref "RA15")
      (value "GL5549")
      (fields (field (name "BOM_Supplier Part") "C125631"))
      (libsource (lib "") (part "GL5549"))
    )
    (comp (ref "RA16")
      (value "GL5549")
      (fields (field (name "BOM_Supplier Part") "C125631"))
      (libsource (lib "") (part "GL5549"))
    )
    (comp (ref "RA17")
      (value "GL5549")
      (fields (field (name "BOM_Supplier Part") "C125631"))
      (libsource (lib "") (part "GL5549"))
    )
    (comp (ref "RA18")
      (value "GL5549")
      (fields (field (name "BOM_Supplier Part") "C125631"))
      (libsource (lib "") (part "GL5549"))
    )
    (comp (ref "RA19")
      (value "GL5549")
      (fields (field (name "BOM_Supplier Part") "C125631"))
      (libsource (lib "") (part "GL5549"))
    )
    (comp (ref "RA21")
      (value "GL5549")
      (fields (field (name "BOM_Supplier Part") "C125631"))
      (libsource (lib "") (part "GL5549"))
    )
    (comp (ref "RA22")
      (value "GL5549")
      (fields (field (name "BOM_Supplier Part") "C125631"))
      (libsource (lib "") (part "GL5549"))
    )
    (comp (ref "RA23")
      (value "GL5549")
      (fields (field (name "BOM_Supplier Part") "C125631"))
      (libsource (lib "") (part "GL5549"))
    )
    (comp (ref "RA24")
      (value "GL5549")
      (fields (field (name "BOM_Supplier Part") "C125631"))
      (libsource (lib "") (part "GL5549"))
    )
    (comp (ref "RA25")
      (value "GL5549")
      (fields (field (name "BOM_Supplier Part") "C125631"))
      (libsource (lib "") (part "GL5549"))
    )
    (comp (ref "RA26")
      (value "GL5549")
      (fields (field (name "BOM_Supplier Part") "C125631"))
      (libsource (lib "") (part "GL5549"))
    )
    (comp (ref "RA27")
      (value "GL5549")
      (fields (field (name "BOM_Supplier Part") "C125631"))
      (libsource (lib "") (part "GL5549"))
    )
    (comp (ref "RA28")
      (value "GL5549")
      (fields (field (name "BOM_Supplier Part") "C125631"))
      (libsource (lib "") (part "GL5549"))
    )
    (comp (ref "RA29")
      (value "GL5549")
      (fields (field (name "BOM_Supplier Part") "C125631"))
      (libsource (lib "") (part "GL5549"))
    )
    (comp (ref "RA31")
      (value "GL5549")
      (fields (field (name "BOM_Supplier Part") "C125631"))
      (libsource (lib "") (part "GL5549"))
    )
    (comp (ref "RA32")
      (value "GL5549")
      (fields (field (name "BOM_Supplier Part") "C125631"))
      (libsource (lib "") (part "GL5549"))
    )
    (comp (ref "RA33")
      (value "GL5549")
      (fields (field (name "BOM_Supplier Part") "C125631"))
      (libsource (lib "") (part "GL5549"))
    )
    (comp (ref "RA34")
      (value "GL5549")
      (fields (field (name "BOM_Supplier Part") "C125631"))
      (libsource (lib "") (part "GL5549"))
    )
    (comp (ref "RA35")
      (value "GL5549")
      (fields (field (name "BOM_Supplier Part") "C125631"))
      (libsource (lib "") (part "GL5549"))
    )
    (comp (ref "RA36")
      (value "GL5549")
      (fields (field (name "BOM_Supplier Part") "C125631"))
      (libsource (lib "") (part "GL5549"))
    )
    (comp (ref "RA37")
      (value "GL5549")
      (fields (field (name "BOM_Supplier Part") "C125631"))
      (libsource (lib "") (part "GL5549"))
    )
    (comp (ref "RA38")
      (value "GL5549")
      (fields (field (name "BOM_Supplier Part") "C125631"))
      (libsource (lib "") (part "GL5549"))
    )
    (comp (ref "RA39")
      (value "GL5549")
      (fields (field (name "BOM_Supplier Part") "C125631"))
      (libsource (lib "") (part "GL5549"))
    )
    (comp (ref "RA41")
      (value "GL5549")
      (fields (field (name "BOM_Supplier Part") "C125631"))
      (libsource (lib "") (part "GL5549"))
    )
    (comp (ref "RA42")
      (value "GL5549")
      (fields (field (name "BOM_Supplier Part") "C125631"))
      (libsource (lib "") (part "GL5549"))
    )
    (comp (ref "RA43")
      (value "GL5549")
      (fields (field (name "BOM_Supplier Part") "C125631"))
      (libsource (lib "") (part "GL5549"))
    )
    (comp (ref "RA44")
      (value "GL5549")
      (fields (field (name "BOM_Supplier Part") "C125631"))
      (libsource (lib "") (part "GL5549"))
    )
    (comp (ref "RA45")
      (value "GL5549")
      (fields (field (name "BOM_Supplier Part") "C125631"))
      (libsource (lib "") (part "GL5549"))
    )
    (comp (ref "RA46")
      (value "GL5549")
      (fields (field (name "BOM_Supplier Part") "C125631"))
      (libsource (lib "") (part "GL5549"))
    )
    (comp (ref "RA47")
      (value "GL5549")
      (fields (field (name "BOM_Supplier Part") "C125631"))
      (libsource (lib "") (part "GL5549"))
    )
    (comp (ref "RA48")
      (value "GL5549")
      (fields (field (name "BOM_Supplier Part") "C125631"))
      (libsource (lib "") (part "GL5549"))
    )
    (comp (ref "RA49")
      (value "GL5549")
      (fields (field (name "BOM_Supplier Part") "C125631"))
      (libsource (lib "") (part "GL5549"))
    )
    (comp (ref "RA51")
      (value "GL5549")
      (fields (field (name "BOM_Supplier Part") "C125631"))
      (libsource (lib "") (part "GL5549"))
    )
    (comp (ref "RA52")
      (value "GL5549")
      (fields (field (name "BOM_Supplier Part") "C125631"))
      (libsource (lib "") (part "GL5549"))
    )
    (comp (ref "RA53")
      (value "GL5549")
      (fields (field (name "BOM_Supplier Part") "C125631"))
      (libsource (lib "") (part "GL5549"))
    )
    (comp (ref "RA54")
      (value "GL5549")
      (fields (field (name "BOM_Supplier Part") "C125631"))
      (libsource (lib "") (part "GL5549"))
    )
    (comp (ref "RA55")
      (value "GL5549")
      (fields (field (name "BOM_Supplier Part") "C125631"))
      (libsource (lib "") (part "GL5549"))
    )
    (comp (ref "RA56")
      (value "GL5549")
      (fields (field (name "BOM_Supplier Part") "C125631"))
      (libsource (lib "") (part "GL5549"))
    )
    (comp (ref "RA57")
      (value "GL5549")
      (fields (field (name "BOM_Supplier Part") "C125631"))
      (libsource (lib "") (part "GL5549"))
    )
    (comp (ref "RA58")
      (value "GL5549")
      (fields (field (name "BOM_Supplier Part") "C125631"))
      (libsource (lib "") (part "GL5549"))
    )
    (comp (ref "RA59")
      (value "GL5549")
      (fields (field (name "BOM_Supplier Part") "C125631"))
      (libsource (lib "") (part "GL5549"))
    )
    (comp (ref "RA61")
      (value "GL5549")
      (fields (field (name "BOM_Supplier Part") "C125631"))
      (libsource (lib "") (part "GL5549"))
    )
    (comp (ref "RA62")
      (value "GL5549")
      (fields (field (name "BOM_Supplier Part") "C125631"))
      (libsource (lib "") (part "GL5549"))
    )
    (comp (ref "RA63")
      (value "GL5549")
      (fields (field (name "BOM_Supplier Part") "C125631"))
      (libsource (lib "") (part "GL5549"))
    )
    (comp (ref "RA64")
      (value "GL5549")
      (fields (field (name "BOM_Supplier Part") "C125631"))
      (libsource (lib "") (part "GL5549"))
    )
    (comp (ref "RA65")
      (value "GL5549")
      (fields (field (name "BOM_Supplier Part") "C125631"))
      (libsource (lib "") (part "GL5549"))
    )
    (comp (ref "RA66")
      (value "GL5549")
      (fields (field (name "BOM_Supplier Part") "C125631"))
      (libsource (lib "") (part "GL5549"))
    )
    (comp (ref "RA67")
      (value "GL5549")
      (fields (field (name "BOM_Supplier Part") "C125631"))
      (libsource (lib "") (part "GL5549"))
    )
    (comp (ref "RA68")
      (value "GL5549")
      (fields (field (name "BOM_Supplier Part") "C125631"))
      (libsource (lib "") (part "GL5549"))
    )
    (comp (ref "RA69")
      (value "GL5549")
      (fields (field (name "BOM_Supplier Part") "C125631"))
      (libsource (lib "") (part "GL5549"))
    )
    (comp (ref "RA71")
      (value "GL5549")
      (fields (field (name "BOM_Supplier Part") "C125631"))
      (libsource (lib "") (part "GL5549"))
    )
    (comp (ref "RA72")
      (value "GL5549")
      (fields (field (name "BOM_Supplier Part") "C125631"))
      (libsource (lib "") (part "GL5549"))
    )
    (comp (ref "RA73")
      (value "GL5549")
      (fields (field (name "BOM_Supplier Part") "C125631"))
      (libsource (lib "") (part "GL5549"))
    )
    (comp (ref "RA74")
      (value "GL5549")
      (fields (field (name "BOM_Supplier Part") "C125631"))
      (libsource (lib "") (part "GL5549"))
    )
    (comp (ref "RA75")
      (value "GL5549")
      (fields (field (name "BOM_Supplier Part") "C125631"))
      (libsource (lib "") (part "GL5549"))
    )
    (comp (ref "RA76")
      (value "GL5549")
      (fields (field (name "BOM_Supplier Part") "C125631"))
      (libsource (lib "") (part "GL5549"))
    )
    (comp (ref "RA77")
      (value "GL5549")
      (fields (field (name "BOM_Supplier Part") "C125631"))
      (libsource (lib "") (part "GL5549"))
    )
    (comp (ref "RA78")
      (value "GL5549")
      (fields (field (name "BOM_Supplier Part") "C125631"))
      (libsource (lib "") (part "GL5549"))
    )
    (comp (ref "RA79")
      (value "GL5549")
      (fields (field (name "BOM_Supplier Part") "C125631"))
      (libsource (lib "") (part "GL5549"))
    )
    (comp (ref "RA81")
      (value "GL5549")
      (fields (field (name "BOM_Supplier Part") "C125631"))
      (libsource (lib "") (part "GL5549"))
    )
    (comp (ref "RA82")
      (value "GL5549")
      (fields (field (name "BOM_Supplier Part") "C125631"))
      (libsource (lib "") (part "GL5549"))
    )
    (comp (ref "RA83")
      (value "GL5549")
      (fields (field (name "BOM_Supplier Part") "C125631"))
      (libsource (lib "") (part "GL5549"))
    )
    (comp (ref "RA84")
      (value "GL5549")
      (fields (field (name "BOM_Supplier Part") "C125631"))
      (libsource (lib "") (part "GL5549"))
    )
    (comp (ref "RA85")
      (value "GL5549")
      (fields (field (name "BOM_Supplier Part") "C125631"))
      (libsource (lib "") (part "GL5549"))
    )
    (comp (ref "RA86")
      (value "GL5549")
      (fields (field (name "BOM_Supplier Part") "C125631"))
      (libsource (lib "") (part "GL5549"))
    )
    (comp (ref "RA87")
      (value "GL5549")
      (fields (field (name "BOM_Supplier Part") "C125631"))
      (libsource (lib "") (part "GL5549"))
    )
    (comp (ref "RA88")
      (value "GL5549")
      (fields (field (name "BOM_Supplier Part") "C125631"))
      (libsource (lib "") (part "GL5549"))
    )
    (comp (ref "RA89")
      (value "GL5549")
      (fields (field (name "BOM_Supplier Part") "C125631"))
      (libsource (lib "") (part "GL5549"))
    )
    (comp (ref "RAU11") (value "470k") (libsource (lib "") (part "R_0603_EU")))
    (comp (ref "RAU12") (value "470k") (libsource (lib "") (part "R_0603_EU")))
    (comp (ref "RAU13") (value "470k") (libsource (lib "") (part "R_0603_EU")))
    (comp (ref "RAU14") (value "470k") (libsource (lib "") (part "R_0603_EU")))
    (comp (ref "RAU15") (value "470k") (libsource (lib "") (part "R_0603_EU")))
    (comp (ref "RAU16") (value "470k") (libsource (lib "") (part "R_0603_EU")))
    (comp (ref "RAU17") (value "470k") (libsource (lib "") (part "R_0603_EU_1")))
    (comp (ref "RAU18") (value "470k") (libsource (lib "") (part "R_0603_EU_1")))
    (comp (ref "RAU19") (value "470k") (libsource (lib "") (part "R_0603_EU_1")))
    (comp (ref "RAU21") (value "470k") (libsource (lib "") (part "R_0603_EU")))
    (comp (ref "RAU22") (value "470k") (libsource (lib "") (part "R_0603_EU")))
    (comp (ref "RAU23") (value "470k") (libsource (lib "") (part "R_0603_EU")))
    (comp (ref "RAU24") (value "470k") (libsource (lib "") (part "R_0603_EU")))
    (comp (ref "RAU25") (value "470k") (libsource (lib "") (part "R_0603_EU")))
    (comp (ref "RAU26") (value "470k") (libsource (lib "") (part "R_0603_EU")))
    (comp (ref "RAU27") (value "470k") (libsource (lib "") (part "R_0603_EU")))
    (comp (ref "RAU28") (value "470k") (libsource (lib "") (part "R_0603_EU")))
    (comp (ref "RAU29") (value "470k") (libsource (lib "") (part "R_0603_EU")))
    (comp (ref "RAU31") (value "470k") (libsource (lib "") (part "R_0603_EU_1")))
    (comp (ref "RAU32") (value "470k") (libsource (lib "") (part "R_0603_EU_1")))
    (comp (ref "RAU33") (value "470k") (libsource (lib "") (part "R_0603_EU_1")))
    (comp (ref "RAU34") (value "470k") (libsource (lib "") (part "R_0603_EU_1")))
    (comp (ref "RAU35") (value "470k") (libsource (lib "") (part "R_0603_EU_1")))
    (comp (ref "RAU36") (value "470k") (libsource (lib "") (part "R_0603_EU_1")))
    (comp (ref "RAU37") (value "470k") (libsource (lib "") (part "R_0603_EU_1")))
    (comp (ref "RAU38") (value "470k") (libsource (lib "") (part "R_0603_EU_1")))
    (comp (ref "RAU39") (value "470k") (libsource (lib "") (part "R_0603_EU_1")))
    (comp (ref "RAU41") (value "470k") (libsource (lib "") (part "R_0603_EU")))
    (comp (ref "RAU42") (value "470k") (libsource (lib "") (part "R_0603_EU")))
    (comp (ref "RAU43") (value "470k") (libsource (lib "") (part "R_0603_EU")))
    (comp (ref "RAU44") (value "470k") (libsource (lib "") (part "R_0603_EU")))
    (comp (ref "RAU45") (value "470k") (libsource (lib "") (part "R_0603_EU")))
    (comp (ref "RAU46") (value "470k") (libsource (lib "") (part "R_0603_EU")))
    (comp (ref "RAU47") (value "470k") (libsource (lib "") (part "R_0603_EU")))
    (comp (ref "RAU48") (value "470k") (libsource (lib "") (part "R_0603_EU")))
    (comp (ref "RAU49") (value "470k") (libsource (lib "") (part "R_0603_EU")))
    (comp (ref "RAU51") (value "470k") (libsource (lib "") (part "R_0603_EU_1")))
    (comp (ref "RAU52") (value "470k") (libsource (lib "") (part "R_0603_EU_1")))
    (comp (ref "RAU53") (value "470k") (libsource (lib "") (part "R_0603_EU_1")))
    (comp (ref "RAU54") (value "470k") (libsource (lib "") (part "R_0603_EU_1")))
    (comp (ref "RAU55") (value "470k") (libsource (lib "") (part "R_0603_EU_1")))
    (comp (ref "RAU56") (value "470k") (libsource (lib "") (part "R_0603_EU_1")))
    (comp (ref "RAU57") (value "470k") (libsource (lib "") (part "R_0603_EU_1")))
    (comp (ref "RAU58") (value "470k") (libsource (lib "") (part "R_0603_EU_1")))
    (comp (ref "RAU59") (value "470k") (libsource (lib "") (part "R_0603_EU_1")))
    (comp (ref "RAU61") (value "470k") (libsource (lib "") (part "R_0603_EU")))
    (comp (ref "RAU62") (value "470k") (libsource (lib "") (part "R_0603_EU")))
    (comp (ref "RAU63") (value "470k") (libsource (lib "") (part "R_0603_EU")))
    (comp (ref "RAU64") (value "470k") (libsource (lib "") (part "R_0603_EU")))
    (comp (ref "RAU65") (value "470k") (libsource (lib "") (part "R_0603_EU")))
    (comp (ref "RAU66") (value "470k") (libsource (lib "") (part "R_0603_EU")))
    (comp (ref "RAU67") (value "470k") (libsource (lib "") (part "R_0603_EU")))
    (comp (ref "RAU68") (value "470k") (libsource (lib "") (part "R_0603_EU")))
    (comp (ref "RAU69") (value "470k") (libsource (lib "") (part "R_0603_EU")))
    (comp (ref "RAU71") (value "470k") (libsource (lib "") (part "R_0603_EU_1")))
    (comp (ref "RAU72") (value "470k") (libsource (lib "") (part "R_0603_EU_1")))
    (comp (ref "RAU73") (value "470k") (libsource (lib "") (part "R_0603_EU_1")))
    (comp (ref "RAU74") (value "470k") (libsource (lib "") (part "R_0603_EU_1")))
    (comp (ref "RAU75") (value "470k") (libsource (lib "") (part "R_0603_EU_1")))
    (comp (ref "RAU76") (value "470k") (libsource (lib "") (part "R_0603_EU_1")))
    (comp (ref "RAU77") (value "470k") (libsource (lib "") (part "R_0603_EU_1")))
    (comp (ref "RAU78") (value "470k") (libsource (lib "") (part "R_0603_EU_1")))
    (comp (ref "RAU79") (value "470k") (libsource (lib "") (part "R_0603_EU_1")))
    (comp (ref "RAU81") (value "470k") (libsource (lib "") (part "R_0603_EU")))
    (comp (ref "RAU82") (value "470k") (libsource (lib "") (part "R_0603_EU")))
    (comp (ref "RAU83") (value "470k") (libsource (lib "") (part "R_0603_EU")))
    (comp (ref "RAU84") (value "470k") (libsource (lib "") (part "R_0603_EU")))
    (comp (ref "RAU85") (value "470k") (libsource (lib "") (part "R_0603_EU")))
    (comp (ref "RAU86") (value "470k") (libsource (lib "") (part "R_0603_EU")))
    (comp (ref "RAU87") (value "470k") (libsource (lib "") (part "R_0603_EU")))
    (comp (ref "RAU88") (value "470k") (libsource (lib "") (part "R_0603_EU")))
    (comp (ref "RAU89") (value "470k") (libsource (lib "") (part "R_0603_EU")))
    (comp (ref "RA91")
      (value "GL5549")
      (fields (field (name "BOM_Supplier Part") "C125631"))
      (libsource (lib "") (part "GL5549"))
    )
    (comp (ref "RA92")
      (value "GL5549")
      (fields (field (name "BOM_Supplier Part") "C125631"))
      (libsource (lib "") (part "GL5549"))
    )
    (comp (ref "RA93")
      (value "GL5549")
      (fields (field (name "BOM_Supplier Part") "C125631"))
      (libsource (lib "") (part "GL5549"))
    )
    (comp (ref "RA94")
      (value "GL5549")
      (fields (field (name "BOM_Supplier Part") "C125631"))
      (libsource (lib "") (part "GL5549"))
    )
    (comp (ref "RA95")
      (value "GL5549")
      (fields (field (name "BOM_Supplier Part") "C125631"))
      (libsource (lib "") (part "GL5549"))
    )
    (comp (ref "RA96")
      (value "GL5549")
      (fields (field (name "BOM_Supplier Part") "C125631"))
      (libsource (lib "") (part "GL5549"))
    )
    (comp (ref "RA97")
      (value "GL5549")
      (fields (field (name "BOM_Supplier Part") "C125631"))
      (libsource (lib "") (part "GL5549"))
    )
    (comp (ref "RA98")
      (value "GL5549")
      (fields (field (name "BOM_Supplier Part") "C125631"))
      (libsource (lib "") (part "GL5549"))
    )
    (comp (ref "RA99")
      (value "GL5549")
      (fields (field (name "BOM_Supplier Part") "C125631"))
      (libsource (lib "") (part "GL5549"))
    )
    (comp (ref "RAU91") (value "470k") (libsource (lib "") (part "R_0603_EU")))
    (comp (ref "RAU92") (value "470k") (libsource (lib "") (part "R_0603_EU")))
    (comp (ref "RAU93") (value "470k") (libsource (lib "") (part "R_0603_EU")))
    (comp (ref "RAU94") (value "470k") (libsource (lib "") (part "R_0603_EU")))
    (comp (ref "RAU95") (value "470k") (libsource (lib "") (part "R_0603_EU")))
    (comp (ref "RAU96") (value "470k") (libsource (lib "") (part "R_0603_EU")))
    (comp (ref "RAU97") (value "470k") (libsource (lib "") (part "R_0603_EU")))
    (comp (ref "RAU98") (value "470k") (libsource (lib "") (part "R_0603_EU")))
    (comp (ref "RAU99") (value "470k") (libsource (lib "") (part "R_0603_EU")))
  )
  (nets
    (net (code "1") (name "3.3V") (class "Default")
      (node (ref "C2") (pin "2") (pinfunction "2_2") (pintype "unspecified"))
      (node (ref "C3") (pin "2") (pinfunction "2_2") (pintype "unspecified"))
      (node (ref "C5") (pin "2") (pinfunction "2_2") (pintype "unspecified"))
      (node (ref "C6") (pin "1") (pinfunction "1_1") (pintype "unspecified"))
      (node (ref "H2") (pin "2") (pinfunction "2_2") (pintype "unspecified"))
      (node (ref "MA1") (pin "16") (pinfunction "VCC_16") (pintype "unspecified"))
      (node (ref "MA10") (pin "16") (pinfunction "VCC_16") (pintype "unspecified"))
      (node (ref "MA11") (pin "16") (pinfunction "VCC_16") (pintype "unspecified"))
      (node (ref "MA2") (pin "16") (pinfunction "VCC_16") (pintype "unspecified"))
      (node (ref "MA3") (pin "16") (pinfunction "VCC_16") (pintype "unspecified"))
      (node (ref "MA4") (pin "16") (pinfunction "VCC_16") (pintype "unspecified"))
      (node (ref "MA5") (pin "16") (pinfunction "VCC_16") (pintype "unspecified"))
      (node (ref "MA6") (pin "16") (pinfunction "VCC_16") (pintype "unspecified"))
      (node (ref "MA7") (pin "16") (pinfunction "VCC_16") (pintype "unspecified"))
      (node (ref "MA8") (pin "16") (pinfunction "VCC_16") (pintype "unspecified"))
      (node (ref "MA9") (pin "16") (pinfunction "VCC_16") (pintype "unspecified"))
      (node (ref "ML1") (pin "16") (pinfunction "VCC_16") (pintype "unspecified"))
      (node (ref "ML10") (pin "16") (pinfunction "VCC_16") (pintype "unspecified"))
      (node (ref "ML11") (pin "16") (pinfunction "VCC_16") (pintype "unspecified"))
      (node (ref "ML2") (pin "16") (pinfunction "VCC_16") (pintype "unspecified"))
      (node (ref "ML3") (pin "16") (pinfunction "VCC_16") (pintype "unspecified"))
      (node (ref "ML4") (pin "16") (pinfunction "VCC_16") (pintype "unspecified"))
      (node (ref "ML5") (pin "16") (pinfunction "VCC_16") (pintype "unspecified"))
      (node (ref "ML6") (pin "16") (pinfunction "VCC_16") (pintype "unspecified"))
      (node (ref "ML7") (pin "16") (pinfunction "VCC_16") (pintype "unspecified"))
      (node (ref "ML8") (pin "16") (pinfunction "VCC_16") (pintype "unspecified"))
      (node (ref "ML9") (pin "16") (pinfunction "VCC_16") (pintype "unspecified"))
      (node (ref "R1") (pin "2") (pinfunction "2_2") (pintype "unspecified"))
      (node (ref "R2") (pin "2") (pinfunction "2_2") (pintype "unspecified"))
      (node (ref "R3") (pin "2") (pinfunction "2_2") (pintype "unspecified"))
      (node (ref "R5") (pin "2") (pinfunction "2_2") (pintype "unspecified"))
      (node (ref "R6") (pin "1") (pinfunction "1_1") (pintype "unspecified"))
      (node (ref "RAU11") (pin "2") (pinfunction "2_2") (pintype "unspecified"))
      (node (ref "RAU12") (pin "2") (pinfunction "2_2") (pintype "unspecified"))
      (node (ref "RAU13") (pin "2") (pinfunction "2_2") (pintype "unspecified"))
      (node (ref "RAU14") (pin "2") (pinfunction "2_2") (pintype "unspecified"))
      (node (ref "RAU15") (pin "2") (pinfunction "2_2") (pintype "unspecified"))
      (node (ref "RAU16") (pin "2") (pinfunction "2_2") (pintype "unspecified"))
      (node (ref "RAU17") (pin "1") (pinfunction "1_1") (pintype "unspecified"))
      (node (ref "RAU18") (pin "1") (pinfunction "1_1") (pintype "unspecified"))
      (node (ref "RAU19") (pin "1") (pinfunction "1_1") (pintype "unspecified"))
      (node (ref "RAU21") (pin "2") (pinfunction "2_2") (pintype "unspecified"))
      (node (ref "RAU22") (pin "2") (pinfunction "2_2") (pintype "unspecified"))
      (node (ref "RAU23") (pin "2") (pinfunction "2_2") (pintype "unspecified"))
      (node (ref "RAU24") (pin "2") (pinfunction "2_2") (pintype "unspecified"))
      (node (ref "RAU25") (pin "2") (pinfunction "2_2") (pintype "unspecified"))
      (node (ref "RAU26") (pin "2") (pinfunction "2_2") (pintype "unspecified"))
      (node (ref "RAU27") (pin "2") (pinfunction "2_2") (pintype "unspecified"))
      (node (ref "RAU28") (pin "2") (pinfunction "2_2") (pintype "unspecified"))
      (node (ref "RAU29") (pin "2") (pinfunction "2_2") (pintype "unspecified"))
      (node (ref "RAU31") (pin "1") (pinfunction "1_1") (pintype "unspecified"))
      (node (ref "RAU32") (pin "1") (pinfunction "1_1") (pintype "unspecified"))
      (node (ref "RAU33") (pin "1") (pinfunction "1_1") (pintype "unspecified"))
      (node (ref "RAU34") (pin "1") (pinfunction "1_1") (pintype "unspecified"))
      (node (ref "RAU35") (pin "1") (pinfunction "1_1") (pintype "unspecified"))
      (node (ref "RAU36") (pin "1") (pinfunction "1_1") (pintype "unspecified"))
      (node (ref "RAU37") (pin "1") (pinfunction "1_1") (pintype "unspecified"))
      (node (ref "RAU38") (pin "1") (pinfunction "1_1") (pintype "unspecified"))
      (node (ref "RAU39") (pin "1") (pinfunction "1_1") (pintype "unspecified"))
      (node (ref "RAU41") (pin "2") (pinfunction "2_2") (pintype "unspecified"))
      (node (ref "RAU42") (pin "2") (pinfunction "2_2") (pintype "unspecified"))
      (node (ref "RAU43") (pin "2") (pinfunction "2_2") (pintype "unspecified"))
      (node (ref "RAU44") (pin "2") (pinfunction "2_2") (pintype "unspecified"))
      (node (ref "RAU45") (pin "2") (pinfunction "2_2") (pintype "unspecified"))
      (node (ref "RAU46") (pin "2") (pinfunction "2_2") (pintype "unspecified"))
      (node (ref "RAU47") (pin "2") (pinfunction "2_2") (pintype "unspecified"))
      (node (ref "RAU48") (pin "2") (pinfunction "2_2") (pintype "unspecified"))
      (node (ref "RAU49") (pin "2") (pinfunction "2_2") (pintype "unspecified"))
      (node (ref "RAU51") (pin "1") (pinfunction "1_1") (pintype "unspecified"))
      (node (ref "RAU52") (pin "1") (pinfunction "1_1") (pintype "unspecified"))
      (node (ref "RAU53") (pin "1") (pinfunction "1_1") (pintype "unspecified"))
      (node (ref "RAU54") (pin "1") (pinfunction "1_1") (pintype "unspecified"))
      (node (ref "RAU55") (pin "1") (pinfunction "1_1") (pintype "unspecified"))
      (node (ref "RAU56") (pin "1") (pinfunction "1_1") (pintype "unspecified"))
      (node (ref "RAU57") (pin "1") (pinfunction "1_1") (pintype "unspecified"))
      (node (ref "RAU58") (pin "1") (pinfunction "1_1") (pintype "unspecified"))
      (node (ref "RAU59") (pin "1") (pinfunction "1_1") (pintype "unspecified"))
      (node (ref "RAU61") (pin "2") (pinfunction "2_2") (pintype "unspecified"))
      (node (ref "RAU62") (pin "2") (pinfunction "2_2") (pintype "unspecified"))
      (node (ref "RAU63") (pin "2") (pinfunction "2_2") (pintype "unspecified"))
      (node (ref "RAU64") (pin "2") (pinfunction "2_2") (pintype "unspecified"))
      (node (ref "RAU65") (pin "2") (pinfunction "2_2") (pintype "unspecified"))
      (node (ref "RAU66") (pin "2") (pinfunction "2_2") (pintype "unspecified"))
      (node (ref "RAU67") (pin "2") (pinfunction "2_2") (pintype "unspecified"))
      (node (ref "RAU68") (pin "2") (pinfunction "2_2") (pintype "unspecified"))
      (node (ref "RAU69") (pin "2") (pinfunction "2_2") (pintype "unspecified"))
      (node (ref "RAU71") (pin "1") (pinfunction "1_1") (pintype "unspecified"))
      (node (ref "RAU72") (pin "1") (pinfunction "1_1") (pintype "unspecified"))
      (node (ref "RAU73") (pin "1") (pinfunction "1_1") (pintype "unspecified"))
      (node (ref "RAU74") (pin "1") (pinfunction "1_1") (pintype "unspecified"))
      (node (ref "RAU75") (pin "1") (pinfunction "1_1") (pintype "unspecified"))
      (node (ref "RAU76") (pin "1") (pinfunction "1_1") (pintype "unspecified"))
      (node (ref "RAU77") (pin "1") (pinfunction "1_1") (pintype "unspecified"))
      (node (ref "RAU78") (pin "1") (pinfunction "1_1") (pintype "unspecified"))
      (node (ref "RAU79") (pin "1") (pinfunction "1_1") (pintype "unspecified"))
      (node (ref "RAU81") (pin "2") (pinfunction "2_2") (pintype "unspecified"))
      (node (ref "RAU82") (pin "2") (pinfunction "2_2") (pintype "unspecified"))
      (node (ref "RAU83") (pin "2") (pinfunction "2_2") (pintype "unspecified"))
      (node (ref "RAU84") (pin "2") (pinfunction "2_2") (pintype "unspecified"))
      (node (ref "RAU85") (pin "2") (pinfunction "2_2") (pintype "unspecified"))
      (node (ref "RAU86") (pin "2") (pinfunction "2_2") (pintype "unspecified"))
      (node (ref "RAU87") (pin "2") (pinfunction "2_2") (pintype "unspecified"))
      (node (ref "RAU88") (pin "2") (pinfunction "2_2") (pintype "unspecified"))
      (node (ref "RAU89") (pin "2") (pinfunction "2_2") (pintype "unspecified"))
      (node (ref "RAU91") (pin "1") (pinfunction "1_1") (pintype "unspecified"))
      (node (ref "RAU92") (pin "1") (pinfunction "1_1") (pintype "unspecified"))
      (node (ref "RAU93") (pin "1") (pinfunction "1_1") (pintype "unspecified"))
      (node (ref "RAU94") (pin "1") (pinfunction "1_1") (pintype "unspecified"))
      (node (ref "RAU95") (pin "1") (pinfunction "1_1") (pintype "unspecified"))
      (node (ref "RAU96") (pin "1") (pinfunction "1_1") (pintype "unspecified"))
      (node (ref "RAU97") (pin "1") (pinfunction "1_1") (pintype "unspecified"))
      (node (ref "RAU98") (pin "1") (pinfunction "1_1") (pintype "unspecified"))
      (node (ref "RAU99") (pin "1") (pinfunction "1_1") (pintype "unspecified"))
      (node (ref "RLU11") (pin "2") (pinfunction "2_2") (pintype "unspecified"))
      (node (ref "RLU12") (pin "2") (pinfunction "2_2") (pintype "unspecified"))
      (node (ref "RLU13") (pin "2") (pinfunction "2_2") (pintype "unspecified"))
      (node (ref "RLU14") (pin "1") (pinfunction "1_1") (pintype "unspecified"))
      (node (ref "RLU15") (pin "1") (pinfunction "1_1") (pintype "unspecified"))
      (node (ref "RLU16") (pin "1") (pinfunction "1_1") (pintype "unspecified"))
      (node (ref "RLU17") (pin "1") (pinfunction "1_1") (pintype "unspecified"))
      (node (ref "RLU18") (pin "1") (pinfunction "1_1") (pintype "unspecified"))
      (node (ref "RLU19") (pin "1") (pinfunction "1_1") (pintype "unspecified"))
      (node (ref "RLU21") (pin "2") (pinfunction "2_2") (pintype "unspecified"))
      (node (ref "RLU22") (pin "2") (pinfunction "2_2") (pintype "unspecified"))
      (node (ref "RLU23") (pin "2") (pinfunction "2_2") (pintype "unspecified"))
      (node (ref "RLU24") (pin "2") (pinfunction "2_2") (pintype "unspecified"))
      (node (ref "RLU25") (pin "2") (pinfunction "2_2") (pintype "unspecified"))
      (node (ref "RLU26") (pin "2") (pinfunction "2_2") (pintype "unspecified"))
      (node (ref "RLU27") (pin "1") (pinfunction "1_1") (pintype "unspecified"))
      (node (ref "RLU28") (pin "1") (pinfunction "1_1") (pintype "unspecified"))
      (node (ref "RLU29") (pin "1") (pinfunction "1_1") (pintype "unspecified"))
      (node (ref "RLU31") (pin "2") (pinfunction "2_2") (pintype "unspecified"))
      (node (ref "RLU32") (pin "2") (pinfunction "2_2") (pintype "unspecified"))
      (node (ref "RLU33") (pin "2") (pinfunction "2_2") (pintype "unspecified"))
      (node (ref "RLU34") (pin "1") (pinfunction "1_1") (pintype "unspecified"))
      (node (ref "RLU35") (pin "1") (pinfunction "1_1") (pintype "unspecified"))
      (node (ref "RLU36") (pin "1") (pinfunction "1_1") (pintype "unspecified"))
      (node (ref "RLU37") (pin "1") (pinfunction "1_1") (pintype "unspecified"))
      (node (ref "RLU38") (pin "1") (pinfunction "1_1") (pintype "unspecified"))
      (node (ref "RLU39") (pin "1") (pinfunction "1_1") (pintype "unspecified"))
      (node (ref "RLU41") (pin "2") (pinfunction "2_2") (pintype "unspecified"))
      (node (ref "RLU42") (pin "2") (pinfunction "2_2") (pintype "unspecified"))
      (node (ref "RLU43") (pin "2") (pinfunction "2_2") (pintype "unspecified"))
      (node (ref "RLU44") (pin "2") (pinfunction "2_2") (pintype "unspecified"))
      (node (ref "RLU45") (pin "2") (pinfunction "2_2") (pintype "unspecified"))
      (node (ref "RLU46") (pin "2") (pinfunction "2_2") (pintype "unspecified"))
      (node (ref "RLU47") (pin "1") (pinfunction "1_1") (pintype "unspecified"))
      (node (ref "RLU48") (pin "1") (pinfunction "1_1") (pintype "unspecified"))
      (node (ref "RLU49") (pin "1") (pinfunction "1_1") (pintype "unspecified"))
      (node (ref "RLU51") (pin "2") (pinfunction "2_2") (pintype "unspecified"))
      (node (ref "RLU52") (pin "2") (pinfunction "2_2") (pintype "unspecified"))
      (node (ref "RLU53") (pin "2") (pinfunction "2_2") (pintype "unspecified"))
      (node (ref "RLU54") (pin "1") (pinfunction "1_1") (pintype "unspecified"))
      (node (ref "RLU55") (pin "1") (pinfunction "1_1") (pintype "unspecified"))
      (node (ref "RLU56") (pin "1") (pinfunction "1_1") (pintype "unspecified"))
      (node (ref "RLU57") (pin "1") (pinfunction "1_1") (pintype "unspecified"))
      (node (ref "RLU58") (pin "1") (pinfunction "1_1") (pintype "unspecified"))
      (node (ref "RLU59") (pin "1") (pinfunction "1_1") (pintype "unspecified"))
      (node (ref "RLU61") (pin "2") (pinfunction "2_2") (pintype "unspecified"))
      (node (ref "RLU62") (pin "2") (pinfunction "2_2") (pintype "unspecified"))
      (node (ref "RLU63") (pin "2") (pinfunction "2_2") (pintype "unspecified"))
      (node (ref "RLU64") (pin "2") (pinfunction "2_2") (pintype "unspecified"))
      (node (ref "RLU65") (pin "2") (pinfunction "2_2") (pintype "unspecified"))
      (node (ref "RLU66") (pin "2") (pinfunction "2_2") (pintype "unspecified"))
      (node (ref "RLU67") (pin "1") (pinfunction "1_1") (pintype "unspecified"))
      (node (ref "RLU68") (pin "1") (pinfunction "1_1") (pintype "unspecified"))
      (node (ref "RLU69") (pin "1") (pinfunction "1_1") (pintype "unspecified"))
      (node (ref "RLU71") (pin "2") (pinfunction "2_2") (pintype "unspecified"))
      (node (ref "RLU72") (pin "2") (pinfunction "2_2") (pintype "unspecified"))
      (node (ref "RLU73") (pin "2") (pinfunction "2_2") (pintype "unspecified"))
      (node (ref "RLU74") (pin "1") (pinfunction "1_1") (pintype "unspecified"))
      (node (ref "RLU75") (pin "1") (pinfunction "1_1") (pintype "unspecified"))
      (node (ref "RLU76") (pin "1") (pinfunction "1_1") (pintype "unspecified"))
      (node (ref "RLU77") (pin "1") (pinfunction "1_1") (pintype "unspecified"))
      (node (ref "RLU78") (pin "1") (pinfunction "1_1") (pintype "unspecified"))
      (node (ref "RLU79") (pin "1") (pinfunction "1_1") (pintype "unspecified"))
      (node (ref "RLU81") (pin "2") (pinfunction "2_2") (pintype "unspecified"))
      (node (ref "RLU82") (pin "2") (pinfunction "2_2") (pintype "unspecified"))
      (node (ref "RLU83") (pin "2") (pinfunction "2_2") (pintype "unspecified"))
      (node (ref "RLU84") (pin "2") (pinfunction "2_2") (pintype "unspecified"))
      (node (ref "RLU85") (pin "2") (pinfunction "2_2") (pintype "unspecified"))
      (node (ref "RLU86") (pin "2") (pinfunction "2_2") (pintype "unspecified"))
      (node (ref "RLU87") (pin "1") (pinfunction "1_1") (pintype "unspecified"))
      (node (ref "RLU88") (pin "1") (pinfunction "1_1") (pintype "unspecified"))
      (node (ref "RLU89") (pin "1") (pinfunction "1_1") (pintype "unspecified"))
      (node (ref "RLU91") (pin "2") (pinfunction "2_2") (pintype "unspecified"))
      (node (ref "RLU92") (pin "2") (pinfunction "2_2") (pintype "unspecified"))
      (node (ref "RLU93") (pin "2") (pinfunction "2_2") (pintype "unspecified"))
      (node (ref "RLU94") (pin "1") (pinfunction "1_1") (pintype "unspecified"))
      (node (ref "RLU95") (pin "1") (pinfunction "1_1") (pintype "unspecified"))
      (node (ref "RLU96") (pin "1") (pinfunction "1_1") (pintype "unspecified"))
      (node (ref "RLU97") (pin "1") (pinfunction "1_1") (pintype "unspecified"))
      (node (ref "RLU98") (pin "1") (pinfunction "1_1") (pintype "unspecified"))
      (node (ref "RLU99") (pin "1") (pinfunction "1_1") (pintype "unspecified"))
      (node (ref "U1") (pin "28") (pinfunction "VDD_28") (pintype "unspecified"))
      (node (ref "U1") (pin "7") (pinfunction "VDD_7") (pintype "unspecified"))
      (node (ref "U2") (pin "4") (pinfunction "OUT_4") (pintype "unspecified"))
      (node (ref "U3") (pin "3") (pinfunction "VDD_3") (pintype "unspecified"))
      (node (ref "U4") (pin "14") (pinfunction "VBAT_14") (pintype "unspecified"))
    )
    (net (code "2") (name "5V") (class "Default")
      (node (ref "C4") (pin "2") (pinfunction "2_2") (pintype "unspecified"))
      (node (ref "H1") (pin "1") (pinfunction "1_1") (pintype "input"))
      (node (ref "R4") (pin "2") (pinfunction "2_2") (pintype "unspecified"))
      (node (ref "RPR11") (pin "1") (pinfunction "Ano_1") (pintype "unspecified"))
      (node (ref "RPR12") (pin "1") (pinfunction "Ano_1") (pintype "unspecified"))
      (node (ref "RPR13") (pin "1") (pinfunction "Ano_1") (pintype "unspecified"))
      (node (ref "RPR14") (pin "1") (pinfunction "Ano_1") (pintype "unspecified"))
      (node (ref "RPR15") (pin "1") (pinfunction "Ano_1") (pintype "unspecified"))
      (node (ref "RPR16") (pin "1") (pinfunction "Ano_1") (pintype "unspecified"))
      (node (ref "RPR17") (pin "1") (pinfunction "Ano_1") (pintype "unspecified"))
      (node (ref "RPR18") (pin "1") (pinfunction "Ano_1") (pintype "unspecified"))
      (node (ref "RPR19") (pin "1") (pinfunction "Ano_1") (pintype "unspecified"))
      (node (ref "RPR21") (pin "1") (pinfunction "Ano_1") (pintype "unspecified"))
      (node (ref "RPR22") (pin "1") (pinfunction "Ano_1") (pintype "unspecified"))
      (node (ref "RPR23") (pin "1") (pinfunction "Ano_1") (pintype "unspecified"))
      (node (ref "RPR24") (pin "1") (pinfunction "Ano_1") (pintype "unspecified"))
      (node (ref "RPR25") (pin "1") (pinfunction "Ano_1") (pintype "unspecified"))
      (node (ref "RPR26") (pin "1") (pinfunction "Ano_1") (pintype "unspecified"))
      (node (ref "RPR27") (pin "1") (pinfunction "Ano_1") (pintype "unspecified"))
      (node (ref "RPR28") (pin "1") (pinfunction "Ano_1") (pintype "unspecified"))
      (node (ref "RPR29") (pin "1") (pinfunction "Ano_1") (pintype "unspecified"))
      (node (ref "RPR31") (pin "1") (pinfunction "Ano_1") (pintype "unspecified"))
      (node (ref "RPR32") (pin "1") (pinfunction "Ano_1") (pintype "unspecified"))
      (node (ref "RPR33") (pin "1") (pinfunction "Ano_1") (pintype "unspecified"))
      (node (ref "RPR34") (pin "1") (pinfunction "Ano_1") (pintype "unspecified"))
      (node (ref "RPR35") (pin "1") (pinfunction "Ano_1") (pintype "unspecified"))
      (node (ref "RPR36") (pin "1") (pinfunction "Ano_1") (pintype "unspecified"))
      (node (ref "RPR37") (pin "1") (pinfunction "Ano_1") (pintype "unspecified"))
      (node (ref "RPR38") (pin "1") (pinfunction "Ano_1") (pintype "unspecified"))
      (node (ref "RPR39") (pin "1") (pinfunction "Ano_1") (pintype "unspecified"))
      (node (ref "RPR41") (pin "1") (pinfunction "Ano_1") (pintype "unspecified"))
      (node (ref "RPR42") (pin "1") (pinfunction "Ano_1") (pintype "unspecified"))
      (node (ref "RPR43") (pin "1") (pinfunction "Ano_1") (pintype "unspecified"))
      (node (ref "RPR44") (pin "1") (pinfunction "Ano_1") (pintype "unspecified"))
      (node (ref "RPR45") (pin "1") (pinfunction "Ano_1") (pintype "unspecified"))
      (node (ref "RPR46") (pin "1") (pinfunction "Ano_1") (pintype "unspecified"))
      (node (ref "RPR47") (pin "1") (pinfunction "Ano_1") (pintype "unspecified"))
      (node (ref "RPR48") (pin "1") (pinfunction "Ano_1") (pintype "unspecified"))
      (node (ref "RPR49") (pin "1") (pinfunction "Ano_1") (pintype "unspecified"))
      (node (ref "RPR51") (pin "1") (pinfunction "Ano_1") (pintype "unspecified"))
      (node (ref "RPR52") (pin "1") (pinfunction "Ano_1") (pintype "unspecified"))
      (node (ref "RPR53") (pin "1") (pinfunction "Ano_1") (pintype "unspecified"))
      (node (ref "RPR54") (pin "1") (pinfunction "Ano_1") (pintype "unspecified"))
      (node (ref "RPR55") (pin "1") (pinfunction "Ano_1") (pintype "unspecified"))
      (node (ref "RPR56") (pin "1") (pinfunction "Ano_1") (pintype "unspecified"))
      (node (ref "RPR57") (pin "1") (pinfunction "Ano_1") (pintype "unspecified"))
      (node (ref "RPR58") (pin "1") (pinfunction "Ano_1") (pintype "unspecified"))
      (node (ref "RPR59") (pin "1") (pinfunction "Ano_1") (pintype "unspecified"))
      (node (ref "RPR61") (pin "1") (pinfunction "Ano_1") (pintype "unspecified"))
      (node (ref "RPR62") (pin "1") (pinfunction "Ano_1") (pintype "unspecified"))
      (node (ref "RPR63") (pin "1") (pinfunction "Ano_1") (pintype "unspecified"))
      (node (ref "RPR64") (pin "1") (pinfunction "Ano_1") (pintype "unspecified"))
      (node (ref "RPR65") (pin "1") (pinfunction "Ano_1") (pintype "unspecified"))
      (node (ref "RPR66") (pin "1") (pinfunction "Ano_1") (pintype "unspecified"))
      (node (ref "RPR67") (pin "1") (pinfunction "Ano_1") (pintype "unspecified"))
      (node (ref "RPR68") (pin "1") (pinfunction "Ano_1") (pintype "unspecified"))
      (node (ref "RPR69") (pin "1") (pinfunction "Ano_1") (pintype "unspecified"))
      (node (ref "RPR71") (pin "1") (pinfunction "Ano_1") (pintype "unspecified"))
      (node (ref "RPR72") (pin "1") (pinfunction "Ano_1") (pintype "unspecified"))
      (node (ref "RPR73") (pin "1") (pinfunction "Ano_1") (pintype "unspecified"))
      (node (ref "RPR74") (pin "1") (pinfunction "Ano_1") (pintype "unspecified"))
      (node (ref "RPR75") (pin "1") (pinfunction "Ano_1") (pintype "unspecified"))
      (node (ref "RPR76") (pin "1") (pinfunction "Ano_1") (pintype "unspecified"))
      (node (ref "RPR77") (pin "1") (pinfunction "Ano_1") (pintype "unspecified"))
      (node (ref "RPR78") (pin "1") (pinfunction "Ano_1") (pintype "unspecified"))
      (node (ref "RPR79") (pin "1") (pinfunction "Ano_1") (pintype "unspecified"))
      (node (ref "RPR81") (pin "1") (pinfunction "Ano_1") (pintype "unspecified"))
      (node (ref "RPR82") (pin "1") (pinfunction "Ano_1") (pintype "unspecified"))
      (node (ref "RPR83") (pin "1") (pinfunction "Ano_1") (pintype "unspecified"))
      (node (ref "RPR84") (pin "1") (pinfunction "Ano_1") (pintype "unspecified"))
      (node (ref "RPR85") (pin "1") (pinfunction "Ano_1") (pintype "unspecified"))
      (node (ref "RPR86") (pin "1") (pinfunction "Ano_1") (pintype "unspecified"))
      (node (ref "RPR87") (pin "1") (pinfunction "Ano_1") (pintype "unspecified"))
      (node (ref "RPR88") (pin "1") (pinfunction "Ano_1") (pintype "unspecified"))
      (node (ref "RPR89") (pin "1") (pinfunction "Ano_1") (pintype "unspecified"))
      (node (ref "RPR91") (pin "1") (pinfunction "Ano_1") (pintype "unspecified"))
      (node (ref "RPR92") (pin "1") (pinfunction "Ano_1") (pintype "unspecified"))
      (node (ref "RPR93") (pin "1") (pinfunction "Ano_1") (pintype "unspecified"))
      (node (ref "RPR94") (pin "1") (pinfunction "Ano_1") (pintype "unspecified"))
      (node (ref "RPR95") (pin "1") (pinfunction "Ano_1") (pintype "unspecified"))
      (node (ref "RPR96") (pin "1") (pinfunction "Ano_1") (pintype "unspecified"))
      (node (ref "RPR97") (pin "1") (pinfunction "Ano_1") (pintype "unspecified"))
      (node (ref "RPR98") (pin "1") (pinfunction "Ano_1") (pintype "unspecified"))
      (node (ref "RPR99") (pin "1") (pinfunction "Ano_1") (pintype "unspecified"))
      (node (ref "U2") (pin "1") (pinfunction "IN_1") (pintype "unspecified"))
    )
    (net (code "3") (name "AS11") (class "Default")
      (node (ref "MA1") (pin "1") (pinfunction "Y4_1") (pintype "unspecified"))
      (node (ref "RA11") (pin "2") (pinfunction "2_2") (pintype "input"))
      (node (ref "RAU11") (pin "1") (pinfunction "1_1") (pintype "unspecified"))
    )
    (net (code "4") (name "AS12") (class "Default")
      (node (ref "MA1") (pin "2") (pinfunction "Y6_2") (pintype "unspecified"))
      (node (ref "RA12") (pin "2") (pinfunction "2_2") (pintype "input"))
      (node (ref "RAU12") (pin "1") (pinfunction "1_1") (pintype "unspecified"))
    )
    (net (code "5") (name "AS13") (class "Default")
      (node (ref "MA1") (pin "4") (pinfunction "Y7_4") (pintype "unspecified"))
      (node (ref "RA13") (pin "2") (pinfunction "2_2") (pintype "input"))
      (node (ref "RAU13") (pin "1") (pinfunction "1_1") (pintype "unspecified"))
    )
    (net (code "6") (name "AS14") (class "Default")
      (node (ref "MA1") (pin "5") (pinfunction "Y5_5") (pintype "unspecified"))
      (node (ref "RA14") (pin "2") (pinfunction "2_2") (pintype "input"))
      (node (ref "RAU14") (pin "1") (pinfunction "1_1") (pintype "unspecified"))
    )
    (net (code "7") (name "AS15") (class "Default")
      (node (ref "MA1") (pin "12") (pinfunction "Y3_12") (pintype "unspecified"))
      (node (ref "RA15") (pin "2") (pinfunction "2_2") (pintype "input"))
      (node (ref "RAU15") (pin "1") (pinfunction "1_1") (pintype "unspecified"))
    )
    (net (code "8") (name "AS16") (class "Default")
      (node (ref "MA1") (pin "13") (pinfunction "Y0_13") (pintype "unspecified"))
      (node (ref "RA16") (pin "2") (pinfunction "2_2") (pintype "input"))
      (node (ref "RAU16") (pin "1") (pinfunction "1_1") (pintype "unspecified"))
    )
    (net (code "9") (name "AS17") (class "Default")
      (node (ref "MA1") (pin "14") (pinfunction "Y1_14") (pintype "unspecified"))
      (node (ref "RA17") (pin "2") (pinfunction "2_2") (pintype "input"))
      (node (ref "RAU17") (pin "2") (pinfunction "2_2") (pintype "unspecified"))
    )
    (net (code "10") (name "AS18") (class "Default")
      (node (ref "MA1") (pin "15") (pinfunction "Y2_15") (pintype "unspecified"))
      (node (ref "RA18") (pin "2") (pinfunction "2_2") (pintype "input"))
      (node (ref "RAU18") (pin "2") (pinfunction "2_2") (pintype "unspecified"))
    )
    (net (code "11") (name "AS19") (class "Default")
      (node (ref "MA10") (pin "1") (pinfunction "Y4_1") (pintype "unspecified"))
      (node (ref "RA19") (pin "2") (pinfunction "2_2") (pintype "input"))
      (node (ref "RAU19") (pin "2") (pinfunction "2_2") (pintype "unspecified"))
    )
    (net (code "12") (name "AS21") (class "Default")
      (node (ref "MA2") (pin "1") (pinfunction "Y4_1") (pintype "unspecified"))
      (node (ref "RA21") (pin "2") (pinfunction "2_2") (pintype "input"))
      (node (ref "RAU21") (pin "1") (pinfunction "1_1") (pintype "unspecified"))
    )
    (net (code "13") (name "AS22") (class "Default")
      (node (ref "MA2") (pin "2") (pinfunction "Y6_2") (pintype "unspecified"))
      (node (ref "RA22") (pin "2") (pinfunction "2_2") (pintype "input"))
      (node (ref "RAU22") (pin "1") (pinfunction "1_1") (pintype "unspecified"))
    )
    (net (code "14") (name "AS23") (class "Default")
      (node (ref "MA2") (pin "4") (pinfunction "Y7_4") (pintype "unspecified"))
      (node (ref "RA23") (pin "2") (pinfunction "2_2") (pintype "input"))
      (node (ref "RAU23") (pin "1") (pinfunction "1_1") (pintype "unspecified"))
    )
    (net (code "15") (name "AS24") (class "Default")
      (node (ref "MA2") (pin "5") (pinfunction "Y5_5") (pintype "unspecified"))
      (node (ref "RA24") (pin "2") (pinfunction "2_2") (pintype "input"))
      (node (ref "RAU24") (pin "1") (pinfunction "1_1") (pintype "unspecified"))
    )
    (net (code "16") (name "AS25") (class "Default")
      (node (ref "MA2") (pin "12") (pinfunction "Y3_12") (pintype "unspecified"))
      (node (ref "RA25") (pin "2") (pinfunction "2_2") (pintype "input"))
      (node (ref "RAU25") (pin "1") (pinfunction "1_1") (pintype "unspecified"))
    )
    (net (code "17") (name "AS26") (class "Default")
      (node (ref "MA2") (pin "13") (pinfunction "Y0_13") (pintype "unspecified"))
      (node (ref "RA26") (pin "2") (pinfunction "2_2") (pintype "input"))
      (node (ref "RAU26") (pin "1") (pinfunction "1_1") (pintype "unspecified"))
    )
    (net (code "18") (name "AS27") (class "Default")
      (node (ref "MA2") (pin "14") (pinfunction "Y1_14") (pintype "unspecified"))
      (node (ref "RA27") (pin "2") (pinfunction "2_2") (pintype "input"))
      (node (ref "RAU27") (pin "1") (pinfunction "1_1") (pintype "unspecified"))
    )
    (net (code "19") (name "AS28") (class "Default")
      (node (ref "MA2") (pin "15") (pinfunction "Y2_15") (pintype "unspecified"))
      (node (ref "RA28") (pin "2") (pinfunction "2_2") (pintype "input"))
      (node (ref "RAU28") (pin "1") (pinfunction "1_1") (pintype "unspecified"))
    )
    (net (code "20") (name "AS29") (class "Default")
      (node (ref "MA10") (pin "2") (pinfunction "Y6_2") (pintype "unspecified"))
      (node (ref "RA29") (pin "2") (pinfunction "2_2") (pintype "input"))
      (node (ref "RAU29") (pin "1") (pinfunction "1_1") (pintype "unspecified"))
    )
    (net (code "21") (name "AS31") (class "Default")
      (node (ref "MA3") (pin "1") (pinfunction "Y4_1") (pintype "unspecified"))
      (node (ref "RA31") (pin "2") (pinfunction "2_2") (pintype "input"))
      (node (ref "RAU31") (pin "2") (pinfunction "2_2") (pintype "unspecified"))
    )
    (net (code "22") (name "AS32") (class "Default")
      (node (ref "MA3") (pin "2") (pinfunction "Y6_2") (pintype "unspecified"))
      (node (ref "RA32") (pin "2") (pinfunction "2_2") (pintype "input"))
      (node (ref "RAU32") (pin "2") (pinfunction "2_2") (pintype "unspecified"))
    )
    (net (code "23") (name "AS33") (class "Default")
      (node (ref "MA3") (pin "4") (pinfunction "Y7_4") (pintype "unspecified"))
      (node (ref "RA33") (pin "2") (pinfunction "2_2") (pintype "input"))
      (node (ref "RAU33") (pin "2") (pinfunction "2_2") (pintype "unspecified"))
    )
    (net (code "24") (name "AS34") (class "Default")
      (node (ref "MA3") (pin "5") (pinfunction "Y5_5") (pintype "unspecified"))
      (node (ref "RA34") (pin "2") (pinfunction "2_2") (pintype "input"))
      (node (ref "RAU34") (pin "2") (pinfunction "2_2") (pintype "unspecified"))
    )
    (net (code "25") (name "AS35") (class "Default")
      (node (ref "MA3") (pin "12") (pinfunction "Y3_12") (pintype "unspecified"))
      (node (ref "RA35") (pin "2") (pinfunction "2_2") (pintype "input"))
      (node (ref "RAU35") (pin "2") (pinfunction "2_2") (pintype "unspecified"))
    )
    (net (code "26") (name "AS36") (class "Default")
      (node (ref "MA3") (pin "13") (pinfunction "Y0_13") (pintype "unspecified"))
      (node (ref "RA36") (pin "2") (pinfunction "2_2") (pintype "input"))
      (node (ref "RAU36") (pin "2") (pinfunction "2_2") (pintype "unspecified"))
    )
    (net (code "27") (name "AS37") (class "Default")
      (node (ref "MA3") (pin "14") (pinfunction "Y1_14") (pintype "unspecified"))
      (node (ref "RA37") (pin "2") (pinfunction "2_2") (pintype "input"))
      (node (ref "RAU37") (pin "2") (pinfunction "2_2") (pintype "unspecified"))
    )
    (net (code "28") (name "AS38") (class "Default")
      (node (ref "MA3") (pin "15") (pinfunction "Y2_15") (pintype "unspecified"))
      (node (ref "RA38") (pin "2") (pinfunction "2_2") (pintype "input"))
      (node (ref "RAU38") (pin "2") (pinfunction "2_2") (pintype "unspecified"))
    )
    (net (code "29") (name "AS39") (class "Default")
      (node (ref "MA10") (pin "4") (pinfunction "Y7_4") (pintype "unspecified"))
      (node (ref "RA39") (pin "2") (pinfunction "2_2") (pintype "input"))
      (node (ref "RAU39") (pin "2") (pinfunction "2_2") (pintype "unspecified"))
    )
    (net (code "30") (name "AS41") (class "Default")
      (node (ref "MA4") (pin "1") (pinfunction "Y4_1") (pintype "unspecified"))
      (node (ref "RA41") (pin "2") (pinfunction "2_2") (pintype "input"))
      (node (ref "RAU41") (pin "1") (pinfunction "1_1") (pintype "unspecified"))
    )
    (net (code "31") (name "AS42") (class "Default")
      (node (ref "MA4") (pin "2") (pinfunction "Y6_2") (pintype "unspecified"))
      (node (ref "RA42") (pin "2") (pinfunction "2_2") (pintype "input"))
      (node (ref "RAU42") (pin "1") (pinfunction "1_1") (pintype "unspecified"))
    )
    (net (code "32") (name "AS43") (class "Default")
      (node (ref "MA4") (pin "4") (pinfunction "Y7_4") (pintype "unspecified"))
      (node (ref "RA43") (pin "2") (pinfunction "2_2") (pintype "input"))
      (node (ref "RAU43") (pin "1") (pinfunction "1_1") (pintype "unspecified"))
    )
    (net (code "33") (name "AS44") (class "Default")
      (node (ref "MA4") (pin "5") (pinfunction "Y5_5") (pintype "unspecified"))
      (node (ref "RA44") (pin "2") (pinfunction "2_2") (pintype "input"))
      (node (ref "RAU44") (pin "1") (pinfunction "1_1") (pintype "unspecified"))
    )
    (net (code "34") (name "AS45") (class "Default")
      (node (ref "MA4") (pin "12") (pinfunction "Y3_12") (pintype "unspecified"))
      (node (ref "RA45") (pin "2") (pinfunction "2_2") (pintype "input"))
      (node (ref "RAU45") (pin "1") (pinfunction "1_1") (pintype "unspecified"))
    )
    (net (code "35") (name "AS46") (class "Default")
      (node (ref "MA4") (pin "13") (pinfunction "Y0_13") (pintype "unspecified"))
      (node (ref "RA46") (pin "2") (pinfunction "2_2") (pintype "input"))
      (node (ref "RAU46") (pin "1") (pinfunction "1_1") (pintype "unspecified"))
    )
    (net (code "36") (name "AS47") (class "Default")
      (node (ref "MA4") (pin "14") (pinfunction "Y1_14") (pintype "unspecified"))
      (node (ref "RA47") (pin "2") (pinfunction "2_2") (pintype "input"))
      (node (ref "RAU47") (pin "1") (pinfunction "1_1") (pintype "unspecified"))
    )
    (net (code "37") (name "AS48") (class "Default")
      (node (ref "MA4") (pin "15") (pinfunction "Y2_15") (pintype "unspecified"))
      (node (ref "RA48") (pin "2") (pinfunction "2_2") (pintype "input"))
      (node (ref "RAU48") (pin "1") (pinfunction "1_1") (pintype "unspecified"))
    )
    (net (code "38") (name "AS49") (class "Default")
      (node (ref "MA10") (pin "5") (pinfunction "Y5_5") (pintype "unspecified"))
      (node (ref "RA49") (pin "2") (pinfunction "2_2") (pintype "input"))
      (node (ref "RAU49") (pin "1") (pinfunction "1_1") (pintype "unspecified"))
    )
    (net (code "39") (name "AS51") (class "Default")
      (node (ref "MA5") (pin "1") (pinfunction "Y4_1") (pintype "unspecified"))
      (node (ref "RA51") (pin "2") (pinfunction "2_2") (pintype "input"))
      (node (ref "RAU51") (pin "2") (pinfunction "2_2") (pintype "unspecified"))
    )
    (net (code "40") (name "AS52") (class "Default")
      (node (ref "MA5") (pin "2") (pinfunction "Y6_2") (pintype "unspecified"))
      (node (ref "RA52") (pin "2") (pinfunction "2_2") (pintype "input"))
      (node (ref "RAU52") (pin "2") (pinfunction "2_2") (pintype "unspecified"))
    )
    (net (code "41") (name "AS53") (class "Default")
      (node (ref "MA5") (pin "4") (pinfunction "Y7_4") (pintype "unspecified"))
      (node (ref "RA53") (pin "2") (pinfunction "2_2") (pintype "input"))
      (node (ref "RAU53") (pin "2") (pinfunction "2_2") (pintype "unspecified"))
    )
    (net (code "42") (name "AS54") (class "Default")
      (node (ref "MA5") (pin "5") (pinfunction "Y5_5") (pintype "unspecified"))
      (node (ref "RA54") (pin "2") (pinfunction "2_2") (pintype "input"))
      (node (ref "RAU54") (pin "2") (pinfunction "2_2") (pintype "unspecified"))
    )
    (net (code "43") (name "AS55") (class "Default")
      (node (ref "MA5") (pin "12") (pinfunction "Y3_12") (pintype "unspecified"))
      (node (ref "RA55") (pin "2") (pinfunction "2_2") (pintype "input"))
      (node (ref "RAU55") (pin "2") (pinfunction "2_2") (pintype "unspecified"))
    )
    (net (code "44") (name "AS56") (class "Default")
      (node (ref "MA5") (pin "13") (pinfunction "Y0_13") (pintype "unspecified"))
      (node (ref "RA56") (pin "2") (pinfunction "2_2") (pintype "input"))
      (node (ref "RAU56") (pin "2") (pinfunction "2_2") (pintype "unspecified"))
    )
    (net (code "45") (name "AS57") (class "Default")
      (node (ref "MA5") (pin "14") (pinfunction "Y1_14") (pintype "unspecified"))
      (node (ref "RA57") (pin "2") (pinfunction "2_2") (pintype "input"))
      (node (ref "RAU57") (pin "2") (pinfunction "2_2") (pintype "unspecified"))
    )
    (net (code "46") (name "AS58") (class "Default")
      (node (ref "MA5") (pin "15") (pinfunction "Y2_15") (pintype "unspecified"))
      (node (ref "RA58") (pin "2") (pinfunction "2_2") (pintype "input"))
      (node (ref "RAU58") (pin "2") (pinfunction "2_2") (pintype "unspecified"))
    )
    (net (code "47") (name "AS59") (class "Default")
      (node (ref "MA10") (pin "12") (pinfunction "Y3_12") (pintype "unspecified"))
      (node (ref "RA59") (pin "2") (pinfunction "2_2") (pintype "input"))
      (node (ref "RAU59") (pin "2") (pinfunction "2_2") (pintype "unspecified"))
    )
    (net (code "48") (name "AS61") (class "Default")
      (node (ref "MA6") (pin "1") (pinfunction "Y4_1") (pintype "unspecified"))
      (node (ref "RA61") (pin "2") (pinfunction "2_2") (pintype "input"))
      (node (ref "RAU61") (pin "1") (pinfunction "1_1") (pintype "unspecified"))
    )
    (net (code "49") (name "AS62") (class "Default")
      (node (ref "MA6") (pin "2") (pinfunction "Y6_2") (pintype "unspecified"))
      (node (ref "RA62") (pin "2") (pinfunction "2_2") (pintype "input"))
      (node (ref "RAU62") (pin "1") (pinfunction "1_1") (pintype "unspecified"))
    )
    (net (code "50") (name "AS63") (class "Default")
      (node (ref "MA6") (pin "4") (pinfunction "Y7_4") (pintype "unspecified"))
      (node (ref "RA63") (pin "2") (pinfunction "2_2") (pintype "input"))
      (node (ref "RAU63") (pin "1") (pinfunction "1_1") (pintype "unspecified"))
    )
    (net (code "51") (name "AS64") (class "Default")
      (node (ref "MA6") (pin "5") (pinfunction "Y5_5") (pintype "unspecified"))
      (node (ref "RA64") (pin "2") (pinfunction "2_2") (pintype "input"))
      (node (ref "RAU64") (pin "1") (pinfunction "1_1") (pintype "unspecified"))
    )
    (net (code "52") (name "AS65") (class "Default")
      (node (ref "MA6") (pin "12") (pinfunction "Y3_12") (pintype "unspecified"))
      (node (ref "RA65") (pin "2") (pinfunction "2_2") (pintype "input"))
      (node (ref "RAU65") (pin "1") (pinfunction "1_1") (pintype "unspecified"))
    )
    (net (code "53") (name "AS66") (class "Default")
      (node (ref "MA6") (pin "13") (pinfunction "Y0_13") (pintype "unspecified"))
      (node (ref "RA66") (pin "2") (pinfunction "2_2") (pintype "input"))
      (node (ref "RAU66") (pin "1") (pinfunction "1_1") (pintype "unspecified"))
    )
    (net (code "54") (name "AS67") (class "Default")
      (node (ref "MA6") (pin "14") (pinfunction "Y1_14") (pintype "unspecified"))
      (node (ref "RA67") (pin "2") (pinfunction "2_2") (pintype "input"))
      (node (ref "RAU67") (pin "1") (pinfunction "1_1") (pintype "unspecified"))
    )
    (net (code "55") (name "AS68") (class "Default")
      (node (ref "MA6") (pin "15") (pinfunction "Y2_15") (pintype "unspecified"))
      (node (ref "RA68") (pin "2") (pinfunction "2_2") (pintype "input"))
      (node (ref "RAU68") (pin "1") (pinfunction "1_1") (pintype "unspecified"))
    )
    (net (code "56") (name "AS69") (class "Default")
      (node (ref "MA10") (pin "13") (pinfunction "Y0_13") (pintype "unspecified"))
      (node (ref "RA69") (pin "2") (pinfunction "2_2") (pintype "input"))
      (node (ref "RAU69") (pin "1") (pinfunction "1_1") (pintype "unspecified"))
    )
    (net (code "57") (name "AS71") (class "Default")
      (node (ref "MA7") (pin "1") (pinfunction "Y4_1") (pintype "unspecified"))
      (node (ref "RA71") (pin "2") (pinfunction "2_2") (pintype "input"))
      (node (ref "RAU71") (pin "2") (pinfunction "2_2") (pintype "unspecified"))
    )
    (net (code "58") (name "AS72") (class "Default")
      (node (ref "MA7") (pin "2") (pinfunction "Y6_2") (pintype "unspecified"))
      (node (ref "RA72") (pin "2") (pinfunction "2_2") (pintype "input"))
      (node (ref "RAU72") (pin "2") (pinfunction "2_2") (pintype "unspecified"))
    )
    (net (code "59") (name "AS73") (class "Default")
      (node (ref "MA7") (pin "4") (pinfunction "Y7_4") (pintype "unspecified"))
      (node (ref "RA73") (pin "2") (pinfunction "2_2") (pintype "input"))
      (node (ref "RAU73") (pin "2") (pinfunction "2_2") (pintype "unspecified"))
    )
    (net (code "60") (name "AS74") (class "Default")
      (node (ref "MA7") (pin "5") (pinfunction "Y5_5") (pintype "unspecified"))
      (node (ref "RA74") (pin "2") (pinfunction "2_2") (pintype "input"))
      (node (ref "RAU74") (pin "2") (pinfunction "2_2") (pintype "unspecified"))
    )
    (net (code "61") (name "AS75") (class "Default")
      (node (ref "MA7") (pin "12") (pinfunction "Y3_12") (pintype "unspecified"))
      (node (ref "RA75") (pin "2") (pinfunction "2_2") (pintype "input"))
      (node (ref "RAU75") (pin "2") (pinfunction "2_2") (pintype "unspecified"))
    )
    (net (code "62") (name "AS76") (class "Default")
      (node (ref "MA7") (pin "13") (pinfunction "Y0_13") (pintype "unspecified"))
      (node (ref "RA76") (pin "2") (pinfunction "2_2") (pintype "input"))
      (node (ref "RAU76") (pin "2") (pinfunction "2_2") (pintype "unspecified"))
    )
    (net (code "63") (name "AS77") (class "Default")
      (node (ref "MA7") (pin "14") (pinfunction "Y1_14") (pintype "unspecified"))
      (node (ref "RA77") (pin "2") (pinfunction "2_2") (pintype "input"))
      (node (ref "RAU77") (pin "2") (pinfunction "2_2") (pintype "unspecified"))
    )
    (net (code "64") (name "AS78") (class "Default")
      (node (ref "MA7") (pin "15") (pinfunction "Y2_15") (pintype "unspecified"))
      (node (ref "RA78") (pin "2") (pinfunction "2_2") (pintype "input"))
      (node (ref "RAU78") (pin "2") (pinfunction "2_2") (pintype "unspecified"))
    )
    (net (code "65") (name "AS79") (class "Default")
      (node (ref "MA10") (pin "14") (pinfunction "Y1_14") (pintype "unspecified"))
      (node (ref "RA79") (pin "2") (pinfunction "2_2") (pintype "input"))
      (node (ref "RAU79") (pin "2") (pinfunction "2_2") (pintype "unspecified"))
    )
    (net (code "66") (name "AS81") (class "Default")
      (node (ref "MA8") (pin "1") (pinfunction "Y4_1") (pintype "unspecified"))
      (node (ref "RA81") (pin "2") (pinfunction "2_2") (pintype "input"))
      (node (ref "RAU81") (pin "1") (pinfunction "1_1") (pintype "unspecified"))
    )
    (net (code "67") (name "AS82") (class "Default")
      (node (ref "MA8") (pin "2") (pinfunction "Y6_2") (pintype "unspecified"))
      (node (ref "RA82") (pin "2") (pinfunction "2_2") (pintype "input"))
      (node (ref "RAU82") (pin "1") (pinfunction "1_1") (pintype "unspecified"))
    )
    (net (code "68") (name "AS83") (class "Default")
      (node (ref "MA8") (pin "4") (pinfunction "Y7_4") (pintype "unspecified"))
      (node (ref "RA83") (pin "2") (pinfunction "2_2") (pintype "input"))
      (node (ref "RAU83") (pin "1") (pinfunction "1_1") (pintype "unspecified"))
    )
    (net (code "69") (name "AS84") (class "Default")
      (node (ref "MA8") (pin "5") (pinfunction "Y5_5") (pintype "unspecified"))
      (node (ref "RA84") (pin "2") (pinfunction "2_2") (pintype "input"))
      (node (ref "RAU84") (pin "1") (pinfunction "1_1") (pintype "unspecified"))
    )
    (net (code "70") (name "AS85") (class "Default")
      (node (ref "MA8") (pin "12") (pinfunction "Y3_12") (pintype "unspecified"))
      (node (ref "RA85") (pin "2") (pinfunction "2_2") (pintype "input"))
      (node (ref "RAU85") (pin "1") (pinfunction "1_1") (pintype "unspecified"))
    )
    (net (code "71") (name "AS86") (class "Default")
      (node (ref "MA8") (pin "13") (pinfunction "Y0_13") (pintype "unspecified"))
      (node (ref "RA86") (pin "2") (pinfunction "2_2") (pintype "input"))
      (node (ref "RAU86") (pin "1") (pinfunction "1_1") (pintype "unspecified"))
    )
    (net (code "72") (name "AS87") (class "Default")
      (node (ref "MA8") (pin "14") (pinfunction "Y1_14") (pintype "unspecified"))
      (node (ref "RA87") (pin "2") (pinfunction "2_2") (pintype "input"))
      (node (ref "RAU87") (pin "1") (pinfunction "1_1") (pintype "unspecified"))
    )
    (net (code "73") (name "AS88") (class "Default")
      (node (ref "MA8") (pin "15") (pinfunction "Y2_15") (pintype "unspecified"))
      (node (ref "RA88") (pin "2") (pinfunction "2_2") (pintype "input"))
      (node (ref "RAU88") (pin "1") (pinfunction "1_1") (pintype "unspecified"))
    )
    (net (code "74") (name "AS89") (class "Default")
      (node (ref "MA10") (pin "15") (pinfunction "Y2_15") (pintype "unspecified"))
      (node (ref "RA89") (pin "2") (pinfunction "2_2") (pintype "input"))
      (node (ref "RAU89") (pin "1") (pinfunction "1_1") (pintype "unspecified"))
    )
    (net (code "75") (name "AS91") (class "Default")
      (node (ref "MA9") (pin "1") (pinfunction "Y4_1") (pintype "unspecified"))
      (node (ref "RA91") (pin "2") (pinfunction "2_2") (pintype "input"))
      (node (ref "RAU91") (pin "2") (pinfunction "2_2") (pintype "unspecified"))
    )
    (net (code "76") (name "AS92") (class "Default")
      (node (ref "MA9") (pin "2") (pinfunction "Y6_2") (pintype "unspecified"))
      (node (ref "RA92") (pin "2") (pinfunction "2_2") (pintype "input"))
      (node (ref "RAU92") (pin "2") (pinfunction "2_2") (pintype "unspecified"))
    )
    (net (code "77") (name "AS93") (class "Default")
      (node (ref "MA9") (pin "4") (pinfunction "Y7_4") (pintype "unspecified"))
      (node (ref "RA93") (pin "2") (pinfunction "2_2") (pintype "input"))
      (node (ref "RAU93") (pin "2") (pinfunction "2_2") (pintype "unspecified"))
    )
    (net (code "78") (name "AS94") (class "Default")
      (node (ref "MA9") (pin "5") (pinfunction "Y5_5") (pintype "unspecified"))
      (node (ref "RA94") (pin "2") (pinfunction "2_2") (pintype "input"))
      (node (ref "RAU94") (pin "2") (pinfunction "2_2") (pintype "unspecified"))
    )
    (net (code "79") (name "AS95") (class "Default")
      (node (ref "MA9") (pin "12") (pinfunction "Y3_12") (pintype "unspecified"))
      (node (ref "RA95") (pin "2") (pinfunction "2_2") (pintype "input"))
      (node (ref "RAU95") (pin "2") (pinfunction "2_2") (pintype "unspecified"))
    )
    (net (code "80") (name "AS96") (class "Default")
      (node (ref "MA9") (pin "13") (pinfunction "Y0_13") (pintype "unspecified"))
      (node (ref "RA96") (pin "2") (pinfunction "2_2") (pintype "input"))
      (node (ref "RAU96") (pin "2") (pinfunction "2_2") (pintype "unspecified"))
    )
    (net (code "81") (name "AS97") (class "Default")
      (node (ref "MA9") (pin "14") (pinfunction "Y1_14") (pintype "unspecified"))
      (node (ref "RA97") (pin "2") (pinfunction "2_2") (pintype "input"))
      (node (ref "RAU97") (pin "2") (pinfunction "2_2") (pintype "unspecified"))
    )
    (net (code "82") (name "AS98") (class "Default")
      (node (ref "MA9") (pin "15") (pinfunction "Y2_15") (pintype "unspecified"))
      (node (ref "RA98") (pin "2") (pinfunction "2_2") (pintype "input"))
      (node (ref "RAU98") (pin "2") (pinfunction "2_2") (pintype "unspecified"))
    )
    (net (code "83") (name "AS99") (class "Default")
      (node (ref "RA99") (pin "2") (pinfunction "2_2") (pintype "input"))
      (node (ref "RAU99") (pin "2") (pinfunction "2_2") (pintype "unspecified"))
      (node (ref "U1") (pin "22") (pinfunction "RA3_22") (pintype "unspecified"))
    )
    (net (code "84") (name "AS_O1") (class "Default")
      (node (ref "MA1") (pin "3") (pinfunction "COM_3") (pintype "unspecified"))
      (node (ref "MA11") (pin "1") (pinfunction "Y4_1") (pintype "unspecified"))
    )
    (net (code "85") (name "AS_O2") (class "Default")
      (node (ref "MA11") (pin "2") (pinfunction "Y6_2") (pintype "unspecified"))
      (node (ref "MA2") (pin "3") (pinfunction "COM_3") (pintype "unspecified"))
    )
    (net (code "86") (name "AS_O3") (class "Default")
      (node (ref "MA11") (pin "4") (pinfunction "Y7_4") (pintype "unspecified"))
      (node (ref "MA3") (pin "3") (pinfunction "COM_3") (pintype "unspecified"))
    )
    (net (code "87") (name "AS_O4") (class "Default")
      (node (ref "MA11") (pin "5") (pinfunction "Y5_5") (pintype "unspecified"))
      (node (ref "MA4") (pin "3") (pinfunction "COM_3") (pintype "unspecified"))
    )
    (net (code "88") (name "AS_O5") (class "Default")
      (node (ref "MA11") (pin "12") (pinfunction "Y3_12") (pintype "unspecified"))
      (node (ref "MA5") (pin "3") (pinfunction "COM_3") (pintype "unspecified"))
    )
    (net (code "89") (name "AS_O6") (class "Default")
      (node (ref "MA11") (pin "13") (pinfunction "Y0_13") (pintype "unspecified"))
      (node (ref "MA6") (pin "3") (pinfunction "COM_3") (pintype "unspecified"))
    )
    (net (code "90") (name "AS_O7") (class "Default")
      (node (ref "MA11") (pin "14") (pinfunction "Y1_14") (pintype "unspecified"))
      (node (ref "MA7") (pin "3") (pinfunction "COM_3") (pintype "unspecified"))
    )
    (net (code "91") (name "AS_O8") (class "Default")
      (node (ref "MA11") (pin "15") (pinfunction "Y2_15") (pintype "unspecified"))
      (node (ref "MA8") (pin "3") (pinfunction "COM_3") (pintype "unspecified"))
    )
    (net (code "92") (name "AS_O9") (class "Default")
      (node (ref "MA9") (pin "3") (pinfunction "COM_3") (pintype "unspecified"))
      (node (ref "U1") (pin "5") (pinfunction "RD7_5") (pintype "unspecified"))
    )
    (net (code "93") (name "AS_O10") (class "Default")
      (node (ref "MA10") (pin "3") (pinfunction "COM_3") (pintype "unspecified"))
      (node (ref "U1") (pin "26") (pinfunction "RE1_26") (pintype "unspecified"))
    )
    (net (code "94") (name "AS_OM") (class "Default")
      (node (ref "MA11") (pin "3") (pinfunction "COM_3") (pintype "unspecified"))
      (node (ref "U1") (pin "9") (pinfunction "RB1_9") (pintype "unspecified"))
    )
    (net (code "95") (name "CTS") (class "Default")
      (node (ref "U1") (pin "39") (pinfunction "RD1_39") (pintype "unspecified"))
      (node (ref "U4") (pin "11") (pinfunction "P0_0_11") (pintype "unspecified"))
    )
    (net (code "96") (name "GND") (class "Default")
      (node (ref "C1") (pin "1") (pinfunction "1_1") (pintype "unspecified"))
      (node (ref "C2") (pin "1") (pinfunction "1_1") (pintype "unspecified"))
      (node (ref "C3") (pin "1") (pinfunction "1_1") (pintype "unspecified"))
      (node (ref "C4") (pin "1") (pinfunction "1_1") (pintype "unspecified"))
      (node (ref "C5") (pin "1") (pinfunction "1_1") (pintype "unspecified"))
      (node (ref "C6") (pin "2") (pinfunction "2_2") (pintype "unspecified"))
      (node (ref "H2") (pin "3") (pinfunction "3_3") (pintype "unspecified"))
      (node (ref "H3") (pin "1") (pinfunction "1_1") (pintype "input"))
      (node (ref "MA1") (pin "6") (pinfunction "INH_6") (pintype "unspecified"))
      (node (ref "MA1") (pin "7") (pinfunction "GND_7") (pintype "unspecified"))
      (node (ref "MA1") (pin "8") (pinfunction "GND_8") (pintype "unspecified"))
      (node (ref "MA10") (pin "6") (pinfunction "INH_6") (pintype "unspecified"))
      (node (ref "MA10") (pin "7") (pinfunction "GND_7") (pintype "unspecified"))
      (node (ref "MA10") (pin "8") (pinfunction "GND_8") (pintype "unspecified"))
      (node (ref "MA11") (pin "6") (pinfunction "INH_6") (pintype "unspecified"))
      (node (ref "MA11") (pin "7") (pinfunction "GND_7") (pintype "unspecified"))
      (node (ref "MA11") (pin "8") (pinfunction "GND_8") (pintype "unspecified"))
      (node (ref "MA2") (pin "6") (pinfunction "INH_6") (pintype "unspecified"))
      (node (ref "MA2") (pin "7") (pinfunction "GND_7") (pintype "unspecified"))
      (node (ref "MA2") (pin "8") (pinfunction "GND_8") (pintype "unspecified"))
      (node (ref "MA3") (pin "6") (pinfunction "INH_6") (pintype "unspecified"))
      (node (ref "MA3") (pin "7") (pinfunction "GND_7") (pintype "unspecified"))
      (node (ref "MA3") (pin "8") (pinfunction "GND_8") (pintype "unspecified"))
      (node (ref "MA4") (pin "6") (pinfunction "INH_6") (pintype "unspecified"))
      (node (ref "MA4") (pin "7") (pinfunction "GND_7") (pintype "unspecified"))
      (node (ref "MA4") (pin "8") (pinfunction "GND_8") (pintype "unspecified"))
      (node (ref "MA5") (pin "6") (pinfunction "INH_6") (pintype "unspecified"))
      (node (ref "MA5") (pin "7") (pinfunction "GND_7") (pintype "unspecified"))
      (node (ref "MA5") (pin "8") (pinfunction "GND_8") (pintype "unspecified"))
      (node (ref "MA6") (pin "6") (pinfunction "INH_6") (pintype "unspecified"))
      (node (ref "MA6") (pin "7") (pinfunction "GND_7") (pintype "unspecified"))
      (node (ref "MA6") (pin "8") (pinfunction "GND_8") (pintype "unspecified"))
      (node (ref "MA7") (pin "6") (pinfunction "INH_6") (pintype "unspecified"))
      (node (ref "MA7") (pin "7") (pinfunction "GND_7") (pintype "unspecified"))
      (node (ref "MA7") (pin "8") (pinfunction "GND_8") (pintype "unspecified"))
      (node (ref "MA8") (pin "6") (pinfunction "INH_6") (pintype "unspecified"))
      (node (ref "MA8") (pin "7") (pinfunction "GND_7") (pintype "unspecified"))
      (node (ref "MA8") (pin "8") (pinfunction "GND_8") (pintype "unspecified"))
      (node (ref "MA9") (pin "6") (pinfunction "INH_6") (pintype "unspecified"))
      (node (ref "MA9") (pin "7") (pinfunction "GND_7") (pintype "unspecified"))
      (node (ref "MA9") (pin "8") (pinfunction "GND_8") (pintype "unspecified"))
      (node (ref "ML1") (pin "6") (pinfunction "INH_6") (pintype "unspecified"))
      (node (ref "ML1") (pin "7") (pinfunction "GND_7") (pintype "unspecified"))
      (node (ref "ML1") (pin "8") (pinfunction "GND_8") (pintype "unspecified"))
      (node (ref "ML10") (pin "6") (pinfunction "INH_6") (pintype "unspecified"))
      (node (ref "ML10") (pin "7") (pinfunction "GND_7") (pintype "unspecified"))
      (node (ref "ML10") (pin "8") (pinfunction "GND_8") (pintype "unspecified"))
      (node (ref "ML11") (pin "6") (pinfunction "INH_6") (pintype "unspecified"))
      (node (ref "ML11") (pin "7") (pinfunction "GND_7") (pintype "unspecified"))
      (node (ref "ML11") (pin "8") (pinfunction "GND_8") (pintype "unspecified"))
      (node (ref "ML2") (pin "6") (pinfunction "INH_6") (pintype "unspecified"))
      (node (ref "ML2") (pin "7") (pinfunction "GND_7") (pintype "unspecified"))
      (node (ref "ML2") (pin "8") (pinfunction "GND_8") (pintype "unspecified"))
      (node (ref "ML3") (pin "6") (pinfunction "INH_6") (pintype "unspecified"))
      (node (ref "ML3") (pin "7") (pinfunction "GND_7") (pintype "unspecified"))
      (node (ref "ML3") (pin "8") (pinfunction "GND_8") (pintype "unspecified"))
      (node (ref "ML4") (pin "6") (pinfunction "INH_6") (pintype "unspecified"))
      (node (ref "ML4") (pin "7") (pinfunction "GND_7") (pintype "unspecified"))
      (node (ref "ML4") (pin "8") (pinfunction "GND_8") (pintype "unspecified"))
      (node (ref "ML5") (pin "6") (pinfunction "INH_6") (pintype "unspecified"))
      (node (ref "ML5") (pin "7") (pinfunction "GND_7") (pintype "unspecified"))
      (node (ref "ML5") (pin "8") (pinfunction "GND_8") (pintype "unspecified"))
      (node (ref "ML6") (pin "6") (pinfunction "INH_6") (pintype "unspecified"))
      (node (ref "ML6") (pin "7") (pinfunction "GND_7") (pintype "unspecified"))
      (node (ref "ML6") (pin "8") (pinfunction "GND_8") (pintype "unspecified"))
      (node (ref "ML7") (pin "6") (pinfunction "INH_6") (pintype "unspecified"))
      (node (ref "ML7") (pin "7") (pinfunction "GND_7") (pintype "unspecified"))
      (node (ref "ML7") (pin "8") (pinfunction "GND_8") (pintype "unspecified"))
      (node (ref "ML8") (pin "6") (pinfunction "INH_6") (pintype "unspecified"))
      (node (ref "ML8") (pin "7") (pinfunction "GND_7") (pintype "unspecified"))
      (node (ref "ML8") (pin "8") (pinfunction "GND_8") (pintype "unspecified"))
      (node (ref "ML9") (pin "6") (pinfunction "INH_6") (pintype "unspecified"))
      (node (ref "ML9") (pin "7") (pinfunction "GND_7") (pintype "unspecified"))
      (node (ref "ML9") (pin "8") (pinfunction "GND_8") (pintype "unspecified"))
      (node (ref "Q1") (pin "2") (pinfunction "S_2") (pintype "unspecified"))
      (node (ref "Q2") (pin "2") (pinfunction "S_2") (pintype "unspecified"))
      (node (ref "Q3") (pin "2") (pinfunction "S_2") (pintype "unspecified"))
      (node (ref "Q4") (pin "2") (pinfunction "S_2") (pintype "unspecified"))
      (node (ref "Q5") (pin "2") (pinfunction "S_2") (pintype "unspecified"))
      (node (ref "Q6") (pin "2") (pinfunction "S_2") (pintype "unspecified"))
      (node (ref "Q7") (pin "2") (pinfunction "S_2") (pintype "unspecified"))
      (node (ref "Q8") (pin "2") (pinfunction "S_2") (pintype "unspecified"))
      (node (ref "Q9") (pin "2") (pinfunction "S_2") (pintype "unspecified"))
      (node (ref "RA11") (pin "1") (pinfunction "1_1") (pintype "input"))
      (node (ref "RA12") (pin "1") (pinfunction "1_1") (pintype "input"))
      (node (ref "RA13") (pin "1") (pinfunction "1_1") (pintype "input"))
      (node (ref "RA14") (pin "1") (pinfunction "1_1") (pintype "input"))
      (node (ref "RA15") (pin "1") (pinfunction "1_1") (pintype "input"))
      (node (ref "RA16") (pin "1") (pinfunction "1_1") (pintype "input"))
      (node (ref "RA17") (pin "1") (pinfunction "1_1") (pintype "input"))
      (node (ref "RA18") (pin "1") (pinfunction "1_1") (pintype "input"))
      (node (ref "RA19") (pin "1") (pinfunction "1_1") (pintype "input"))
      (node (ref "RA21") (pin "1") (pinfunction "1_1") (pintype "input"))
      (node (ref "RA22") (pin "1") (pinfunction "1_1") (pintype "input"))
      (node (ref "RA23") (pin "1") (pinfunction "1_1") (pintype "input"))
      (node (ref "RA24") (pin "1") (pinfunction "1_1") (pintype "input"))
      (node (ref "RA25") (pin "1") (pinfunction "1_1") (pintype "input"))
      (node (ref "RA26") (pin "1") (pinfunction "1_1") (pintype "input"))
      (node (ref "RA27") (pin "1") (pinfunction "1_1") (pintype "input"))
      (node (ref "RA28") (pin "1") (pinfunction "1_1") (pintype "input"))
      (node (ref "RA29") (pin "1") (pinfunction "1_1") (pintype "input"))
      (node (ref "RA31") (pin "1") (pinfunction "1_1") (pintype "input"))
      (node (ref "RA32") (pin "1") (pinfunction "1_1") (pintype "input"))
      (node (ref "RA33") (pin "1") (pinfunction "1_1") (pintype "input"))
      (node (ref "RA34") (pin "1") (pinfunction "1_1") (pintype "input"))
      (node (ref "RA35") (pin "1") (pinfunction "1_1") (pintype "input"))
      (node (ref "RA36") (pin "1") (pinfunction "1_1") (pintype "input"))
      (node (ref "RA37") (pin "1") (pinfunction "1_1") (pintype "input"))
      (node (ref "RA38") (pin "1") (pinfunction "1_1") (pintype "input"))
      (node (ref "RA39") (pin "1") (pinfunction "1_1") (pintype "input"))
      (node (ref "RA41") (pin "1") (pinfunction "1_1") (pintype "input"))
      (node (ref "RA42") (pin "1") (pinfunction "1_1") (pintype "input"))
      (node (ref "RA43") (pin "1") (pinfunction "1_1") (pintype "input"))
      (node (ref "RA44") (pin "1") (pinfunction "1_1") (pintype "input"))
      (node (ref "RA45") (pin "1") (pinfunction "1_1") (pintype "input"))
      (node (ref "RA46") (pin "1") (pinfunction "1_1") (pintype "input"))
      (node (ref "RA47") (pin "1") (pinfunction "1_1") (pintype "input"))
      (node (ref "RA48") (pin "1") (pinfunction "1_1") (pintype "input"))
      (node (ref "RA49") (pin "1") (pinfunction "1_1") (pintype "input"))
      (node (ref "RA51") (pin "1") (pinfunction "1_1") (pintype "input"))
      (node (ref "RA52") (pin "1") (pinfunction "1_1") (pintype "input"))
      (node (ref "RA53") (pin "1") (pinfunction "1_1") (pintype "input"))
      (node (ref "RA54") (pin "1") (pinfunction "1_1") (pintype "input"))
      (node (ref "RA55") (pin "1") (pinfunction "1_1") (pintype "input"))
      (node (ref "RA56") (pin "1") (pinfunction "1_1") (pintype "input"))
      (node (ref "RA57") (pin "1") (pinfunction "1_1") (pintype "input"))
      (node (ref "RA58") (pin "1") (pinfunction "1_1") (pintype "input"))
      (node (ref "RA59") (pin "1") (pinfunction "1_1") (pintype "input"))
      (node (ref "RA61") (pin "1") (pinfunction "1_1") (pintype "input"))
      (node (ref "RA62") (pin "1") (pinfunction "1_1") (pintype "input"))
      (node (ref "RA63") (pin "1") (pinfunction "1_1") (pintype "input"))
      (node (ref "RA64") (pin "1") (pinfunction "1_1") (pintype "input"))
      (node (ref "RA65") (pin "1") (pinfunction "1_1") (pintype "input"))
      (node (ref "RA66") (pin "1") (pinfunction "1_1") (pintype "input"))
      (node (ref "RA67") (pin "1") (pinfunction "1_1") (pintype "input"))
      (node (ref "RA68") (pin "1") (pinfunction "1_1") (pintype "input"))
      (node (ref "RA69") (pin "1") (pinfunction "1_1") (pintype "input"))
      (node (ref "RA71") (pin "1") (pinfunction "1_1") (pintype "input"))
      (node (ref "RA72") (pin "1") (pinfunction "1_1") (pintype "input"))
      (node (ref "RA73") (pin "1") (pinfunction "1_1") (pintype "input"))
      (node (ref "RA74") (pin "1") (pinfunction "1_1") (pintype "input"))
      (node (ref "RA75") (pin "1") (pinfunction "1_1") (pintype "input"))
      (node (ref "RA76") (pin "1") (pinfunction "1_1") (pintype "input"))
      (node (ref "RA77") (pin "1") (pinfunction "1_1") (pintype "input"))
      (node (ref "RA78") (pin "1") (pinfunction "1_1") (pintype "input"))
      (node (ref "RA79") (pin "1") (pinfunction "1_1") (pintype "input"))
      (node (ref "RA81") (pin "1") (pinfunction "1_1") (pintype "input"))
      (node (ref "RA82") (pin "1") (pinfunction "1_1") (pintype "input"))
      (node (ref "RA83") (pin "1") (pinfunction "1_1") (pintype "input"))
      (node (ref "RA84") (pin "1") (pinfunction "1_1") (pintype "input"))
      (node (ref "RA85") (pin "1") (pinfunction "1_1") (pintype "input"))
      (node (ref "RA86") (pin "1") (pinfunction "1_1") (pintype "input"))
      (node (ref "RA87") (pin "1") (pinfunction "1_1") (pintype "input"))
      (node (ref "RA88") (pin "1") (pinfunction "1_1") (pintype "input"))
      (node (ref "RA89") (pin "1") (pinfunction "1_1") (pintype "input"))
      (node (ref "RA91") (pin "1") (pinfunction "1_1") (pintype "input"))
      (node (ref "RA92") (pin "1") (pinfunction "1_1") (pintype "input"))
      (node (ref "RA93") (pin "1") (pinfunction "1_1") (pintype "input"))
      (node (ref "RA94") (pin "1") (pinfunction "1_1") (pintype "input"))
      (node (ref "RA95") (pin "1") (pinfunction "1_1") (pintype "input"))
      (node (ref "RA96") (pin "1") (pinfunction "1_1") (pintype "input"))
      (node (ref "RA97") (pin "1") (pinfunction "1_1") (pintype "input"))
      (node (ref "RA98") (pin "1") (pinfunction "1_1") (pintype "input"))
      (node (ref "RA99") (pin "1") (pinfunction "1_1") (pintype "input"))
      (node (ref "RPR11") (pin "3") (pinfunction "Em_3") (pintype "unspecified"))
      (node (ref "RPR12") (pin "3") (pinfunction "Em_3") (pintype "unspecified"))
      (node (ref "RPR13") (pin "3") (pinfunction "Em_3") (pintype "unspecified"))
      (node (ref "RPR14") (pin "3") (pinfunction "Em_3") (pintype "unspecified"))
      (node (ref "RPR15") (pin "3") (pinfunction "Em_3") (pintype "unspecified"))
      (node (ref "RPR16") (pin "3") (pinfunction "Em_3") (pintype "unspecified"))
      (node (ref "RPR17") (pin "3") (pinfunction "Em_3") (pintype "unspecified"))
      (node (ref "RPR18") (pin "3") (pinfunction "Em_3") (pintype "unspecified"))
      (node (ref "RPR19") (pin "3") (pinfunction "Em_3") (pintype "unspecified"))
      (node (ref "RPR21") (pin "3") (pinfunction "Em_3") (pintype "unspecified"))
      (node (ref "RPR22") (pin "3") (pinfunction "Em_3") (pintype "unspecified"))
      (node (ref "RPR23") (pin "3") (pinfunction "Em_3") (pintype "unspecified"))
      (node (ref "RPR24") (pin "3") (pinfunction "Em_3") (pintype "unspecified"))
      (node (ref "RPR25") (pin "3") (pinfunction "Em_3") (pintype "unspecified"))
      (node (ref "RPR26") (pin "3") (pinfunction "Em_3") (pintype "unspecified"))
      (node (ref "RPR27") (pin "3") (pinfunction "Em_3") (pintype "unspecified"))
      (node (ref "RPR28") (pin "3") (pinfunction "Em_3") (pintype "unspecified"))
      (node (ref "RPR29") (pin "3") (pinfunction "Em_3") (pintype "unspecified"))
      (node (ref "RPR31") (pin "3") (pinfunction "Em_3") (pintype "unspecified"))
      (node (ref "RPR32") (pin "3") (pinfunction "Em_3") (pintype "unspecified"))
      (node (ref "RPR33") (pin "3") (pinfunction "Em_3") (pintype "unspecified"))
      (node (ref "RPR34") (pin "3") (pinfunction "Em_3") (pintype "unspecified"))
      (node (ref "RPR35") (pin "3") (pinfunction "Em_3") (pintype "unspecified"))
      (node (ref "RPR36") (pin "3") (pinfunction "Em_3") (pintype "unspecified"))
      (node (ref "RPR37") (pin "3") (pinfunction "Em_3") (pintype "unspecified"))
      (node (ref "RPR38") (pin "3") (pinfunction "Em_3") (pintype "unspecified"))
      (node (ref "RPR39") (pin "3") (pinfunction "Em_3") (pintype "unspecified"))
      (node (ref "RPR41") (pin "3") (pinfunction "Em_3") (pintype "unspecified"))
      (node (ref "RPR42") (pin "3") (pinfunction "Em_3") (pintype "unspecified"))
      (node (ref "RPR43") (pin "3") (pinfunction "Em_3") (pintype "unspecified"))
      (node (ref "RPR44") (pin "3") (pinfunction "Em_3") (pintype "unspecified"))
      (node (ref "RPR45") (pin "3") (pinfunction "Em_3") (pintype "unspecified"))
      (node (ref "RPR46") (pin "3") (pinfunction "Em_3") (pintype "unspecified"))
      (node (ref "RPR47") (pin "3") (pinfunction "Em_3") (pintype "unspecified"))
      (node (ref "RPR48") (pin "3") (pinfunction "Em_3") (pintype "unspecified"))
      (node (ref "RPR49") (pin "3") (pinfunction "Em_3") (pintype "unspecified"))
      (node (ref "RPR51") (pin "3") (pinfunction "Em_3") (pintype "unspecified"))
      (node (ref "RPR52") (pin "3") (pinfunction "Em_3") (pintype "unspecified"))
      (node (ref "RPR53") (pin "3") (pinfunction "Em_3") (pintype "unspecified"))
      (node (ref "RPR54") (pin "3") (pinfunction "Em_3") (pintype "unspecified"))
      (node (ref "RPR55") (pin "3") (pinfunction "Em_3") (pintype "unspecified"))
      (node (ref "RPR56") (pin "3") (pinfunction "Em_3") (pintype "unspecified"))
      (node (ref "RPR57") (pin "3") (pinfunction "Em_3") (pintype "unspecified"))
      (node (ref "RPR58") (pin "3") (pinfunction "Em_3") (pintype "unspecified"))
      (node (ref "RPR59") (pin "3") (pinfunction "Em_3") (pintype "unspecified"))
      (node (ref "RPR61") (pin "3") (pinfunction "Em_3") (pintype "unspecified"))
      (node (ref "RPR62") (pin "3") (pinfunction "Em_3") (pintype "unspecified"))
      (node (ref "RPR63") (pin "3") (pinfunction "Em_3") (pintype "unspecified"))
      (node (ref "RPR64") (pin "3") (pinfunction "Em_3") (pintype "unspecified"))
      (node (ref "RPR65") (pin "3") (pinfunction "Em_3") (pintype "unspecified"))
      (node (ref "RPR66") (pin "3") (pinfunction "Em_3") (pintype "unspecified"))
      (node (ref "RPR67") (pin "3") (pinfunction "Em_3") (pintype "unspecified"))
      (node (ref "RPR68") (pin "3") (pinfunction "Em_3") (pintype "unspecified"))
      (node (ref "RPR69") (pin "3") (pinfunction "Em_3") (pintype "unspecified"))
      (node (ref "RPR71") (pin "3") (pinfunction "Em_3") (pintype "unspecified"))
      (node (ref "RPR72") (pin "3") (pinfunction "Em_3") (pintype "unspecified"))
      (node (ref "RPR73") (pin "3") (pinfunction "Em_3") (pintype "unspecified"))
      (node (ref "RPR74") (pin "3") (pinfunction "Em_3") (pintype "unspecified"))
      (node (ref "RPR75") (pin "3") (pinfunction "Em_3") (pintype "unspecified"))
      (node (ref "RPR76") (pin "3") (pinfunction "Em_3") (pintype "unspecified"))
      (node (ref "RPR77") (pin "3") (pinfunction "Em_3") (pintype "unspecified"))
      (node (ref "RPR78") (pin "3") (pinfunction "Em_3") (pintype "unspecified"))
      (node (ref "RPR79") (pin "3") (pinfunction "Em_3") (pintype "unspecified"))
      (node (ref "RPR81") (pin "3") (pinfunction "Em_3") (pintype "unspecified"))
      (node (ref "RPR82") (pin "3") (pinfunction "Em_3") (pintype "unspecified"))
      (node (ref "RPR83") (pin "3") (pinfunction "Em_3") (pintype "unspecified"))
      (node (ref "RPR84") (pin "3") (pinfunction "Em_3") (pintype "unspecified"))
      (node (ref "RPR85") (pin "3") (pinfunction "Em_3") (pintype "unspecified"))
      (node (ref "RPR86") (pin "3") (pinfunction "Em_3") (pintype "unspecified"))
      (node (ref "RPR87") (pin "3") (pinfunction "Em_3") (pintype "unspecified"))
      (node (ref "RPR88") (pin "3") (pinfunction "Em_3") (pintype "unspecified"))
      (node (ref "RPR89") (pin "3") (pinfunction "Em_3") (pintype "unspecified"))
      (node (ref "RPR91") (pin "3") (pinfunction "Em_3") (pintype "unspecified"))
      (node (ref "RPR92") (pin "3") (pinfunction "Em_3") (pintype "unspecified"))
      (node (ref "RPR93") (pin "3") (pinfunction "Em_3") (pintype "unspecified"))
      (node (ref "RPR94") (pin "3") (pinfunction "Em_3") (pintype "unspecified"))
      (node (ref "RPR95") (pin "3") (pinfunction "Em_3") (pintype "unspecified"))
      (node (ref "RPR96") (pin "3") (pinfunction "Em_3") (pintype "unspecified"))
      (node (ref "RPR97") (pin "3") (pinfunction "Em_3") (pintype "unspecified"))
      (node (ref "RPR98") (pin "3") (pinfunction "Em_3") (pintype "unspecified"))
      (node (ref "RPR99") (pin "3") (pinfunction "Em_3") (pintype "unspecified"))
      (node (ref "U1") (pin "29") (pinfunction "VSS_29") (pintype "unspecified"))
      (node (ref "U1") (pin "6") (pinfunction "VSS_6") (pintype "unspecified"))
      (node (ref "U2") (pin "2") (pinfunction "GND_2") (pintype "unspecified"))
      (node (ref "U3") (pin "2") (pinfunction "GND_2") (pintype "unspecified"))
      (node (ref "U4") (pin "13") (pinfunction "GND_13") (pintype "unspecified"))
      (node (ref "U4") (pin "2") (pinfunction "GND_2") (pintype "unspecified"))
      (node (ref "USB1") (pin "5") (pinfunction "GND_5") (pintype "bidirectional"))
      (node (ref "USB1") (pin "6") (pintype "unspecified"))
    )
    (net (code "97") (name "HCI_RXD") (class "Default")
      (node (ref "U1") (pin "43") (pinfunction "RC5_43") (pintype "unspecified"))
      (node (ref "U4") (pin "7") (pinfunction "HCI_RXD_7") (pintype "unspecified"))
    )
    (net (code "98") (name "HCI_TXD") (class "Default")
      (node (ref "U1") (pin "42") (pinfunction "RC4_42") (pintype "unspecified"))
      (node (ref "U4") (pin "8") (pinfunction "HCI_TXD_8") (pintype "unspecified"))
    )
    (net (code "99") (name "ICSPCLK") (class "Default")
      (node (ref "H2") (pin "5") (pinfunction "5_5") (pintype "unspecified"))
      (node (ref "U1") (pin "16") (pinfunction "ICSPCLK/RB6_16") (pintype "unspecified"))
    )
    (net (code "100") (name "ICSPDAT") (class "Default")
      (node (ref "H2") (pin "4") (pinfunction "4_4") (pintype "unspecified"))
      (node (ref "U1") (pin "17") (pinfunction "ICSPDAT/RB7_17") (pintype "unspecified"))
    )
    (net (code "101") (name "IR1") (class "Default")
      (node (ref "Q1") (pin "3") (pinfunction "D_3") (pintype "unspecified"))
      (node (ref "RLD11") (pin "1") (pinfunction "1_1") (pintype "unspecified"))
      (node (ref "RLD12") (pin "1") (pinfunction "1_1") (pintype "unspecified"))
      (node (ref "RLD13") (pin "1") (pinfunction "1_1") (pintype "unspecified"))
      (node (ref "RLD14") (pin "2") (pinfunction "2_2") (pintype "unspecified"))
      (node (ref "RLD21") (pin "1") (pinfunction "1_1") (pintype "unspecified"))
      (node (ref "RLD22") (pin "1") (pinfunction "1_1") (pintype "unspecified"))
      (node (ref "RLD23") (pin "1") (pinfunction "1_1") (pintype "unspecified"))
      (node (ref "RLD24") (pin "1") (pinfunction "1_1") (pintype "unspecified"))
    )
    (net (code "102") (name "IR2") (class "Default")
      (node (ref "Q2") (pin "3") (pinfunction "D_3") (pintype "unspecified"))
      (node (ref "RLD15") (pin "2") (pinfunction "2_2") (pintype "unspecified"))
      (node (ref "RLD16") (pin "2") (pinfunction "2_2") (pintype "unspecified"))
      (node (ref "RLD17") (pin "2") (pinfunction "2_2") (pintype "unspecified"))
      (node (ref "RLD18") (pin "2") (pinfunction "2_2") (pintype "unspecified"))
      (node (ref "RLD19") (pin "2") (pinfunction "2_2") (pintype "unspecified"))
      (node (ref "RLD25") (pin "1") (pinfunction "1_1") (pintype "unspecified"))
      (node (ref "RLD26") (pin "1") (pinfunction "1_1") (pintype "unspecified"))
      (node (ref "RLD27") (pin "1") (pinfunction "1_1") (pintype "unspecified"))
      (node (ref "RLD28") (pin "1") (pinfunction "1_1") (pintype "unspecified"))
      (node (ref "RLD29") (pin "1") (pinfunction "1_1") (pintype "unspecified"))
    )
    (net (code "103") (name "IR3") (class "Default")
      (node (ref "Q3") (pin "3") (pinfunction "D_3") (pintype "unspecified"))
      (node (ref "RLD31") (pin "2") (pinfunction "2_2") (pintype "unspecified"))
      (node (ref "RLD32") (pin "2") (pinfunction "2_2") (pintype "unspecified"))
      (node (ref "RLD33") (pin "2") (pinfunction "2_2") (pintype "unspecified"))
      (node (ref "RLD34") (pin "2") (pinfunction "2_2") (pintype "unspecified"))
      (node (ref "RLD41") (pin "1") (pinfunction "1_1") (pintype "unspecified"))
      (node (ref "RLD42") (pin "1") (pinfunction "1_1") (pintype "unspecified"))
      (node (ref "RLD43") (pin "1") (pinfunction "1_1") (pintype "unspecified"))
      (node (ref "RLD44") (pin "1") (pinfunction "1_1") (pintype "unspecified"))
    )
    (net (code "104") (name "IR4") (class "Default")
      (node (ref "Q4") (pin "3") (pinfunction "D_3") (pintype "unspecified"))
      (node (ref "RLD35") (pin "2") (pinfunction "2_2") (pintype "unspecified"))
      (node (ref "RLD36") (pin "2") (pinfunction "2_2") (pintype "unspecified"))
      (node (ref "RLD37") (pin "2") (pinfunction "2_2") (pintype "unspecified"))
      (node (ref "RLD38") (pin "2") (pinfunction "2_2") (pintype "unspecified"))
      (node (ref "RLD39") (pin "2") (pinfunction "2_2") (pintype "unspecified"))
      (node (ref "RLD45") (pin "1") (pinfunction "1_1") (pintype "unspecified"))
      (node (ref "RLD46") (pin "1") (pinfunction "1_1") (pintype "unspecified"))
      (node (ref "RLD47") (pin "1") (pinfunction "1_1") (pintype "unspecified"))
      (node (ref "RLD48") (pin "1") (pinfunction "1_1") (pintype "unspecified"))
      (node (ref "RLD49") (pin "1") (pinfunction "1_1") (pintype "unspecified"))
    )
    (net (code "105") (name "IR5") (class "Default")
      (node (ref "Q5") (pin "3") (pinfunction "D_3") (pintype "unspecified"))
      (node (ref "RLD51") (pin "2") (pinfunction "2_2") (pintype "unspecified"))
      (node (ref "RLD52") (pin "2") (pinfunction "2_2") (pintype "unspecified"))
      (node (ref "RLD53") (pin "2") (pinfunction "2_2") (pintype "unspecified"))
      (node (ref "RLD54") (pin "2") (pinfunction "2_2") (pintype "unspecified"))
      (node (ref "RLD61") (pin "1") (pinfunction "1_1") (pintype "unspecified"))
      (node (ref "RLD62") (pin "1") (pinfunction "1_1") (pintype "unspecified"))
      (node (ref "RLD63") (pin "1") (pinfunction "1_1") (pintype "unspecified"))
      (node (ref "RLD64") (pin "1") (pinfunction "1_1") (pintype "unspecified"))
    )
    (net (code "106") (name "IR6") (class "Default")
      (node (ref "Q6") (pin "3") (pinfunction "D_3") (pintype "unspecified"))
      (node (ref "RLD55") (pin "2") (pinfunction "2_2") (pintype "unspecified"))
      (node (ref "RLD56") (pin "2") (pinfunction "2_2") (pintype "unspecified"))
      (node (ref "RLD57") (pin "2") (pinfunction "2_2") (pintype "unspecified"))
      (node (ref "RLD58") (pin "2") (pinfunction "2_2") (pintype "unspecified"))
      (node (ref "RLD59") (pin "2") (pinfunction "2_2") (pintype "unspecified"))
      (node (ref "RLD65") (pin "1") (pinfunction "1_1") (pintype "unspecified"))
      (node (ref "RLD66") (pin "1") (pinfunction "1_1") (pintype "unspecified"))
      (node (ref "RLD67") (pin "1") (pinfunction "1_1") (pintype "unspecified"))
      (node (ref "RLD68") (pin "1") (pinfunction "1_1") (pintype "unspecified"))
      (node (ref "RLD69") (pin "1") (pinfunction "1_1") (pintype "unspecified"))
    )
    (net (code "107") (name "IR7") (class "Default")
      (node (ref "Q7") (pin "3") (pinfunction "D_3") (pintype "unspecified"))
      (node (ref "RLD71") (pin "2") (pinfunction "2_2") (pintype "unspecified"))
      (node (ref "RLD72") (pin "2") (pinfunction "2_2") (pintype "unspecified"))
      (node (ref "RLD73") (pin "2") (pinfunction "2_2") (pintype "unspecified"))
      (node (ref "RLD74") (pin "2") (pinfunction "2_2") (pintype "unspecified"))
      (node (ref "RLD81") (pin "1") (pinfunction "1_1") (pintype "unspecified"))
      (node (ref "RLD82") (pin "1") (pinfunction "1_1") (pintype "unspecified"))
      (node (ref "RLD83") (pin "1") (pinfunction "1_1") (pintype "unspecified"))
      (node (ref "RLD84") (pin "1") (pinfunction "1_1") (pintype "unspecified"))
    )
    (net (code "108") (name "IR8") (class "Default")
      (node (ref "Q8") (pin "3") (pinfunction "D_3") (pintype "unspecified"))
      (node (ref "RLD75") (pin "2") (pinfunction "2_2") (pintype "unspecified"))
      (node (ref "RLD76") (pin "2") (pinfunction "2_2") (pintype "unspecified"))
      (node (ref "RLD77") (pin "2") (pinfunction "2_2") (pintype "unspecified"))
      (node (ref "RLD78") (pin "2") (pinfunction "2_2") (pintype "unspecified"))
      (node (ref "RLD79") (pin "2") (pinfunction "2_2") (pintype "unspecified"))
      (node (ref "RLD85") (pin "1") (pinfunction "1_1") (pintype "unspecified"))
      (node (ref "RLD86") (pin "1") (pinfunction "1_1") (pintype "unspecified"))
      (node (ref "RLD87") (pin "1") (pinfunction "1_1") (pintype "unspecified"))
      (node (ref "RLD88") (pin "1") (pinfunction "1_1") (pintype "unspecified"))
      (node (ref "RLD89") (pin "1") (pinfunction "1_1") (pintype "unspecified"))
    )
    (net (code "109") (name "IR9") (class "Default")
      (node (ref "Q9") (pin "3") (pinfunction "D_3") (pintype "unspecified"))
      (node (ref "RLD91") (pin "2") (pinfunction "2_2") (pintype "unspecified"))
      (node (ref "RLD92") (pin "2") (pinfunction "2_2") (pintype "unspecified"))
      (node (ref "RLD93") (pin "2") (pinfunction "2_2") (pintype "unspecified"))
      (node (ref "RLD94") (pin "2") (pinfunction "2_2") (pintype "unspecified"))
      (node (ref "RLD95") (pin "2") (pinfunction "2_2") (pintype "unspecified"))
      (node (ref "RLD96") (pin "2") (pinfunction "2_2") (pintype "unspecified"))
      (node (ref "RLD97") (pin "2") (pinfunction "2_2") (pintype "unspecified"))
      (node (ref "RLD98") (pin "2") (pinfunction "2_2") (pintype "unspecified"))
      (node (ref "RLD99") (pin "2") (pinfunction "2_2") (pintype "unspecified"))
    )
    (net (code "110") (name "IRS1") (class "Default")
      (node (ref "RS1") (pin "1") (pinfunction "1_1") (pintype "unspecified"))
      (node (ref "U1") (pin "35") (pinfunction "RC1_35") (pintype "unspecified"))
    )
    (net (code "111") (name "IRS2") (class "Default")
      (node (ref "RS2") (pin "1") (pinfunction "1_1") (pintype "unspecified"))
      (node (ref "U1") (pin "30") (pinfunction "RA7_30") (pintype "unspecified"))
    )
    (net (code "112") (name "IRS3") (class "Default")
      (node (ref "RS3") (pin "1") (pinfunction "1_1") (pintype "unspecified"))
      (node (ref "U1") (pin "36") (pinfunction "RC2_36") (pintype "unspecified"))
    )
    (net (code "113") (name "IRS4") (class "Default")
      (node (ref "RS4") (pin "1") (pinfunction "1_1") (pintype "unspecified"))
      (node (ref "U1") (pin "25") (pinfunction "RE0_25") (pintype "unspecified"))
    )
    (net (code "114") (name "IRS5") (class "Default")
      (node (ref "RS5") (pin "1") (pinfunction "1_1") (pintype "unspecified"))
      (node (ref "U1") (pin "37") (pinfunction "RC3_37") (pintype "unspecified"))
    )
    (net (code "115") (name "IRS6") (class "Default")
      (node (ref "RS6") (pin "1") (pinfunction "1_1") (pintype "unspecified"))
      (node (ref "U1") (pin "24") (pinfunction "RA5_24") (pintype "unspecified"))
    )
    (net (code "116") (name "IRS7") (class "Default")
      (node (ref "RS7") (pin "1") (pinfunction "1_1") (pintype "unspecified"))
      (node (ref "U1") (pin "38") (pinfunction "RD0_38") (pintype "unspecified"))
    )
    (net (code "117") (name "IRS8") (class "Default")
      (node (ref "RS8") (pin "1") (pinfunction "1_1") (pintype "unspecified"))
      (node (ref "U1") (pin "23") (pinfunction "RA4_23") (pintype "unspecified"))
    )
    (net (code "118") (name "IRS9") (class "Default")
      (node (ref "RS9") (pin "1") (pinfunction "1_1") (pintype "unspecified"))
      (node (ref "U1") (pin "3") (pinfunction "RD5_3") (pintype "unspecified"))
    )
    (net (code "119") (name "LINK_DROP") (class "Default")
      (node (ref "H3") (pin "2") (pinfunction "2_2") (pintype "input"))
      (node (ref "R6") (pin "2") (pinfunction "2_2") (pintype "unspecified"))
      (node (ref "U4") (pin "3") (pinfunction "P1_2_3") (pintype "unspecified"))
    )
    (net (code "120") (name "LS11") (class "Default")
      (node (ref "ML1") (pin "1") (pinfunction "Y4_1") (pintype "unspecified"))
      (node (ref "RLU11") (pin "1") (pinfunction "1_1") (pintype "unspecified"))
      (node (ref "RPR11") (pin "4") (pinfunction "Col_4") (pintype "unspecified"))
    )
    (net (code "121") (name "LS12") (class "Default")
      (node (ref "ML1") (pin "2") (pinfunction "Y6_2") (pintype "unspecified"))
      (node (ref "RLU12") (pin "1") (pinfunction "1_1") (pintype "unspecified"))
      (node (ref "RPR12") (pin "4") (pinfunction "Col_4") (pintype "unspecified"))
    )
    (net (code "122") (name "LS13") (class "Default")
      (node (ref "ML1") (pin "4") (pinfunction "Y7_4") (pintype "unspecified"))
      (node (ref "RLU13") (pin "1") (pinfunction "1_1") (pintype "unspecified"))
      (node (ref "RPR13") (pin "4") (pinfunction "Col_4") (pintype "unspecified"))
    )
    (net (code "123") (name "LS14") (class "Default")
      (node (ref "ML1") (pin "5") (pinfunction "Y5_5") (pintype "unspecified"))
      (node (ref "RLU14") (pin "2") (pinfunction "2_2") (pintype "unspecified"))
      (node (ref "RPR14") (pin "4") (pinfunction "Col_4") (pintype "unspecified"))
    )
    (net (code "124") (name "LS15") (class "Default")
      (node (ref "ML1") (pin "12") (pinfunction "Y3_12") (pintype "unspecified"))
      (node (ref "RLU15") (pin "2") (pinfunction "2_2") (pintype "unspecified"))
      (node (ref "RPR15") (pin "4") (pinfunction "Col_4") (pintype "unspecified"))
    )
    (net (code "125") (name "LS16") (class "Default")
      (node (ref "ML1") (pin "13") (pinfunction "Y0_13") (pintype "unspecified"))
      (node (ref "RLU16") (pin "2") (pinfunction "2_2") (pintype "unspecified"))
      (node (ref "RPR16") (pin "4") (pinfunction "Col_4") (pintype "unspecified"))
    )
    (net (code "126") (name "LS17") (class "Default")
      (node (ref "ML1") (pin "14") (pinfunction "Y1_14") (pintype "unspecified"))
      (node (ref "RLU17") (pin "2") (pinfunction "2_2") (pintype "unspecified"))
      (node (ref "RPR17") (pin "4") (pinfunction "Col_4") (pintype "unspecified"))
    )
    (net (code "127") (name "LS18") (class "Default")
      (node (ref "ML1") (pin "15") (pinfunction "Y2_15") (pintype "unspecified"))
      (node (ref "RLU18") (pin "2") (pinfunction "2_2") (pintype "unspecified"))
      (node (ref "RPR18") (pin "4") (pinfunction "Col_4") (pintype "unspecified"))
    )
    (net (code "128") (name "LS19") (class "Default")
      (node (ref "ML10") (pin "1") (pinfunction "Y4_1") (pintype "unspecified"))
      (node (ref "RLU19") (pin "2") (pinfunction "2_2") (pintype "unspecified"))
      (node (ref "RPR19") (pin "4") (pinfunction "Col_4") (pintype "unspecified"))
    )
    (net (code "129") (name "LS21") (class "Default")
      (node (ref "ML2") (pin "1") (pinfunction "Y4_1") (pintype "unspecified"))
      (node (ref "RLU21") (pin "1") (pinfunction "1_1") (pintype "unspecified"))
      (node (ref "RPR21") (pin "4") (pinfunction "Col_4") (pintype "unspecified"))
    )
    (net (code "130") (name "LS22") (class "Default")
      (node (ref "ML2") (pin "2") (pinfunction "Y6_2") (pintype "unspecified"))
      (node (ref "RLU22") (pin "1") (pinfunction "1_1") (pintype "unspecified"))
      (node (ref "RPR22") (pin "4") (pinfunction "Col_4") (pintype "unspecified"))
    )
    (net (code "131") (name "LS23") (class "Default")
      (node (ref "ML2") (pin "4") (pinfunction "Y7_4") (pintype "unspecified"))
      (node (ref "RLU23") (pin "1") (pinfunction "1_1") (pintype "unspecified"))
      (node (ref "RPR23") (pin "4") (pinfunction "Col_4") (pintype "unspecified"))
    )
    (net (code "132") (name "LS24") (class "Default")
      (node (ref "ML2") (pin "5") (pinfunction "Y5_5") (pintype "unspecified"))
      (node (ref "RLU24") (pin "1") (pinfunction "1_1") (pintype "unspecified"))
      (node (ref "RPR24") (pin "4") (pinfunction "Col_4") (pintype "unspecified"))
    )
    (net (code "133") (name "LS25") (class "Default")
      (node (ref "ML2") (pin "12") (pinfunction "Y3_12") (pintype "unspecified"))
      (node (ref "RLU25") (pin "1") (pinfunction "1_1") (pintype "unspecified"))
      (node (ref "RPR25") (pin "4") (pinfunction "Col_4") (pintype "unspecified"))
    )
    (net (code "134") (name "LS26") (class "Default")
      (node (ref "ML2") (pin "13") (pinfunction "Y0_13") (pintype "unspecified"))
      (node (ref "RLU26") (pin "1") (pinfunction "1_1") (pintype "unspecified"))
      (node (ref "RPR26") (pin "4") (pinfunction "Col_4") (pintype "unspecified"))
    )
    (net (code "135") (name "LS27") (class "Default")
      (node (ref "ML2") (pin "14") (pinfunction "Y1_14") (pintype "unspecified"))
      (node (ref "RLU27") (pin "2") (pinfunction "2_2") (pintype "unspecified"))
      (node (ref "RPR27") (pin "4") (pinfunction "Col_4") (pintype "unspecified"))
    )
    (net (code "136") (name "LS28") (class "Default")
      (node (ref "ML2") (pin "15") (pinfunction "Y2_15") (pintype "unspecified"))
      (node (ref "RLU28") (pin "2") (pinfunction "2_2") (pintype "unspecified"))
      (node (ref "RPR28") (pin "4") (pinfunction "Col_4") (pintype "unspecified"))
    )
    (net (code "137") (name "LS29") (class "Default")
      (node (ref "ML10") (pin "2") (pinfunction "Y6_2") (pintype "unspecified"))
      (node (ref "RLU29") (pin "2") (pinfunction "2_2") (pintype "unspecified"))
      (node (ref "RPR29") (pin "4") (pinfunction "Col_4") (pintype "unspecified"))
    )
    (net (code "138") (name "LS31") (class "Default")
      (node (ref "ML3") (pin "1") (pinfunction "Y4_1") (pintype "unspecified"))
      (node (ref "RLU31") (pin "1") (pinfunction "1_1") (pintype "unspecified"))
      (node (ref "RPR31") (pin "4") (pinfunction "Col_4") (pintype "unspecified"))
    )
    (net (code "139") (name "LS32") (class "Default")
      (node (ref "ML3") (pin "2") (pinfunction "Y6_2") (pintype "unspecified"))
      (node (ref "RLU32") (pin "1") (pinfunction "1_1") (pintype "unspecified"))
      (node (ref "RPR32") (pin "4") (pinfunction "Col_4") (pintype "unspecified"))
    )
    (net (code "140") (name "LS33") (class "Default")
      (node (ref "ML3") (pin "4") (pinfunction "Y7_4") (pintype "unspecified"))
      (node (ref "RLU33") (pin "1") (pinfunction "1_1") (pintype "unspecified"))
      (node (ref "RPR33") (pin "4") (pinfunction "Col_4") (pintype "unspecified"))
    )
    (net (code "141") (name "LS34") (class "Default")
      (node (ref "ML3") (pin "5") (pinfunction "Y5_5") (pintype "unspecified"))
      (node (ref "RLU34") (pin "2") (pinfunction "2_2") (pintype "unspecified"))
      (node (ref "RPR34") (pin "4") (pinfunction "Col_4") (pintype "unspecified"))
    )
    (net (code "142") (name "LS35") (class "Default")
      (node (ref "ML3") (pin "12") (pinfunction "Y3_12") (pintype "unspecified"))
      (node (ref "RLU35") (pin "2") (pinfunction "2_2") (pintype "unspecified"))
      (node (ref "RPR35") (pin "4") (pinfunction "Col_4") (pintype "unspecified"))
    )
    (net (code "143") (name "LS36") (class "Default")
      (node (ref "ML3") (pin "13") (pinfunction "Y0_13") (pintype "unspecified"))
      (node (ref "RLU36") (pin "2") (pinfunction "2_2") (pintype "unspecified"))
      (node (ref "RPR36") (pin "4") (pinfunction "Col_4") (pintype "unspecified"))
    )
    (net (code "144") (name "LS37") (class "Default")
      (node (ref "ML3") (pin "14") (pinfunction "Y1_14") (pintype "unspecified"))
      (node (ref "RLU37") (pin "2") (pinfunction "2_2") (pintype "unspecified"))
      (node (ref "RPR37") (pin "4") (pinfunction "Col_4") (pintype "unspecified"))
    )
    (net (code "145") (name "LS38") (class "Default")
      (node (ref "ML3") (pin "15") (pinfunction "Y2_15") (pintype "unspecified"))
      (node (ref "RLU38") (pin "2") (pinfunction "2_2") (pintype "unspecified"))
      (node (ref "RPR38") (pin "4") (pinfunction "Col_4") (pintype "unspecified"))
    )
    (net (code "146") (name "LS39") (class "Default")
      (node (ref "ML10") (pin "4") (pinfunction "Y7_4") (pintype "unspecified"))
      (node (ref "RLU39") (pin "2") (pinfunction "2_2") (pintype "unspecified"))
      (node (ref "RPR39") (pin "4") (pinfunction "Col_4") (pintype "unspecified"))
    )
    (net (code "147") (name "LS41") (class "Default")
      (node (ref "ML4") (pin "1") (pinfunction "Y4_1") (pintype "unspecified"))
      (node (ref "RLU41") (pin "1") (pinfunction "1_1") (pintype "unspecified"))
      (node (ref "RPR41") (pin "4") (pinfunction "Col_4") (pintype "unspecified"))
    )
    (net (code "148") (name "LS42") (class "Default")
      (node (ref "ML4") (pin "2") (pinfunction "Y6_2") (pintype "unspecified"))
      (node (ref "RLU42") (pin "1") (pinfunction "1_1") (pintype "unspecified"))
      (node (ref "RPR42") (pin "4") (pinfunction "Col_4") (pintype "unspecified"))
    )
    (net (code "149") (name "LS43") (class "Default")
      (node (ref "ML4") (pin "4") (pinfunction "Y7_4") (pintype "unspecified"))
      (node (ref "RLU43") (pin "1") (pinfunction "1_1") (pintype "unspecified"))
      (node (ref "RPR43") (pin "4") (pinfunction "Col_4") (pintype "unspecified"))
    )
    (net (code "150") (name "LS44") (class "Default")
      (node (ref "ML4") (pin "5") (pinfunction "Y5_5") (pintype "unspecified"))
      (node (ref "RLU44") (pin "1") (pinfunction "1_1") (pintype "unspecified"))
      (node (ref "RPR44") (pin "4") (pinfunction "Col_4") (pintype "unspecified"))
    )
    (net (code "151") (name "LS45") (class "Default")
      (node (ref "ML4") (pin "12") (pinfunction "Y3_12") (pintype "unspecified"))
      (node (ref "RLU45") (pin "1") (pinfunction "1_1") (pintype "unspecified"))
      (node (ref "RPR45") (pin "4") (pinfunction "Col_4") (pintype "unspecified"))
    )
    (net (code "152") (name "LS46") (class "Default")
      (node (ref "ML4") (pin "13") (pinfunction "Y0_13") (pintype "unspecified"))
      (node (ref "RLU46") (pin "1") (pinfunction "1_1") (pintype "unspecified"))
      (node (ref "RPR46") (pin "4") (pinfunction "Col_4") (pintype "unspecified"))
    )
    (net (code "153") (name "LS47") (class "Default")
      (node (ref "ML4") (pin "14") (pinfunction "Y1_14") (pintype "unspecified"))
      (node (ref "RLU47") (pin "2") (pinfunction "2_2") (pintype "unspecified"))
      (node (ref "RPR47") (pin "4") (pinfunction "Col_4") (pintype "unspecified"))
    )
    (net (code "154") (name "LS48") (class "Default")
      (node (ref "ML4") (pin "15") (pinfunction "Y2_15") (pintype "unspecified"))
      (node (ref "RLU48") (pin "2") (pinfunction "2_2") (pintype "unspecified"))
      (node (ref "RPR48") (pin "4") (pinfunction "Col_4") (pintype "unspecified"))
    )
    (net (code "155") (name "LS49") (class "Default")
      (node (ref "ML10") (pin "5") (pinfunction "Y5_5") (pintype "unspecified"))
      (node (ref "RLU49") (pin "2") (pinfunction "2_2") (pintype "unspecified"))
      (node (ref "RPR49") (pin "4") (pinfunction "Col_4") (pintype "unspecified"))
    )
    (net (code "156") (name "LS51") (class "Default")
      (node (ref "ML5") (pin "1") (pinfunction "Y4_1") (pintype "unspecified"))
      (node (ref "RLU51") (pin "1") (pinfunction "1_1") (pintype "unspecified"))
      (node (ref "RPR51") (pin "4") (pinfunction "Col_4") (pintype "unspecified"))
    )
    (net (code "157") (name "LS52") (class "Default")
      (node (ref "ML5") (pin "2") (pinfunction "Y6_2") (pintype "unspecified"))
      (node (ref "RLU52") (pin "1") (pinfunction "1_1") (pintype "unspecified"))
      (node (ref "RPR52") (pin "4") (pinfunction "Col_4") (pintype "unspecified"))
    )
    (net (code "158") (name "LS53") (class "Default")
      (node (ref "ML5") (pin "4") (pinfunction "Y7_4") (pintype "unspecified"))
      (node (ref "RLU53") (pin "1") (pinfunction "1_1") (pintype "unspecified"))
      (node (ref "RPR53") (pin "4") (pinfunction "Col_4") (pintype "unspecified"))
    )
    (net (code "159") (name "LS54") (class "Default")
      (node (ref "ML5") (pin "5") (pinfunction "Y5_5") (pintype "unspecified"))
      (node (ref "RLU54") (pin "2") (pinfunction "2_2") (pintype "unspecified"))
      (node (ref "RPR54") (pin "4") (pinfunction "Col_4") (pintype "unspecified"))
    )
    (net (code "160") (name "LS55") (class "Default")
      (node (ref "ML5") (pin "12") (pinfunction "Y3_12") (pintype "unspecified"))
      (node (ref "RLU55") (pin "2") (pinfunction "2_2") (pintype "unspecified"))
      (node (ref "RPR55") (pin "4") (pinfunction "Col_4") (pintype "unspecified"))
    )
    (net (code "161") (name "LS56") (class "Default")
      (node (ref "ML5") (pin "13") (pinfunction "Y0_13") (pintype "unspecified"))
      (node (ref "RLU56") (pin "2") (pinfunction "2_2") (pintype "unspecified"))
      (node (ref "RPR56") (pin "4") (pinfunction "Col_4") (pintype "unspecified"))
    )
    (net (code "162") (name "LS57") (class "Default")
      (node (ref "ML5") (pin "14") (pinfunction "Y1_14") (pintype "unspecified"))
      (node (ref "RLU57") (pin "2") (pinfunction "2_2") (pintype "unspecified"))
      (node (ref "RPR57") (pin "4") (pinfunction "Col_4") (pintype "unspecified"))
    )
    (net (code "163") (name "LS58") (class "Default")
      (node (ref "ML5") (pin "15") (pinfunction "Y2_15") (pintype "unspecified"))
      (node (ref "RLU58") (pin "2") (pinfunction "2_2") (pintype "unspecified"))
      (node (ref "RPR58") (pin "4") (pinfunction "Col_4") (pintype "unspecified"))
    )
    (net (code "164") (name "LS59") (class "Default")
      (node (ref "ML10") (pin "12") (pinfunction "Y3_12") (pintype "unspecified"))
      (node (ref "RLU59") (pin "2") (pinfunction "2_2") (pintype "unspecified"))
      (node (ref "RPR59") (pin "4") (pinfunction "Col_4") (pintype "unspecified"))
    )
    (net (code "165") (name "LS61") (class "Default")
      (node (ref "ML6") (pin "1") (pinfunction "Y4_1") (pintype "unspecified"))
      (node (ref "RLU61") (pin "1") (pinfunction "1_1") (pintype "unspecified"))
      (node (ref "RPR61") (pin "4") (pinfunction "Col_4") (pintype "unspecified"))
    )
    (net (code "166") (name "LS62") (class "Default")
      (node (ref "ML6") (pin "2") (pinfunction "Y6_2") (pintype "unspecified"))
      (node (ref "RLU62") (pin "1") (pinfunction "1_1") (pintype "unspecified"))
      (node (ref "RPR62") (pin "4") (pinfunction "Col_4") (pintype "unspecified"))
    )
    (net (code "167") (name "LS63") (class "Default")
      (node (ref "ML6") (pin "4") (pinfunction "Y7_4") (pintype "unspecified"))
      (node (ref "RLU63") (pin "1") (pinfunction "1_1") (pintype "unspecified"))
      (node (ref "RPR63") (pin "4") (pinfunction "Col_4") (pintype "unspecified"))
    )
    (net (code "168") (name "LS64") (class "Default")
      (node (ref "ML6") (pin "5") (pinfunction "Y5_5") (pintype "unspecified"))
      (node (ref "RLU64") (pin "1") (pinfunction "1_1") (pintype "unspecified"))
      (node (ref "RPR64") (pin "4") (pinfunction "Col_4") (pintype "unspecified"))
    )
    (net (code "169") (name "LS65") (class "Default")
      (node (ref "ML6") (pin "12") (pinfunction "Y3_12") (pintype "unspecified"))
      (node (ref "RLU65") (pin "1") (pinfunction "1_1") (pintype "unspecified"))
      (node (ref "RPR65") (pin "4") (pinfunction "Col_4") (pintype "unspecified"))
    )
    (net (code "170") (name "LS66") (class "Default")
      (node (ref "ML6") (pin "13") (pinfunction "Y0_13") (pintype "unspecified"))
      (node (ref "RLU66") (pin "1") (pinfunction "1_1") (pintype "unspecified"))
      (node (ref "RPR66") (pin "4") (pinfunction "Col_4") (pintype "unspecified"))
    )
    (net (code "171") (name "LS67") (class "Default")
      (node (ref "ML6") (pin "14") (pinfunction "Y1_14") (pintype "unspecified"))
      (node (ref "RLU67") (pin "2") (pinfunction "2_2") (pintype "unspecified"))
      (node (ref "RPR67") (pin "4") (pinfunction "Col_4") (pintype "unspecified"))
    )
    (net (code "172") (name "LS68") (class "Default")
      (node (ref "ML6") (pin "15") (pinfunction "Y2_15") (pintype "unspecified"))
      (node (ref "RLU68") (pin "2") (pinfunction "2_2") (pintype "unspecified"))
      (node (ref "RPR68") (pin "4") (pinfunction "Col_4") (pintype "unspecified"))
    )
    (net (code "173") (name "LS69") (class "Default")
      (node (ref "ML10") (pin "13") (pinfunction "Y0_13") (pintype "unspecified"))
      (node (ref "RLU69") (pin "2") (pinfunction "2_2") (pintype "unspecified"))
      (node (ref "RPR69") (pin "4") (pinfunction "Col_4") (pintype "unspecified"))
    )
    (net (code "174") (name "LS71") (class "Default")
      (node (ref "ML7") (pin "1") (pinfunction "Y4_1") (pintype "unspecified"))
      (node (ref "RLU71") (pin "1") (pinfunction "1_1") (pintype "unspecified"))
      (node (ref "RPR71") (pin "4") (pinfunction "Col_4") (pintype "unspecified"))
    )
    (net (code "175") (name "LS72") (class "Default")
      (node (ref "ML7") (pin "2") (pinfunction "Y6_2") (pintype "unspecified"))
      (node (ref "RLU72") (pin "1") (pinfunction "1_1") (pintype "unspecified"))
      (node (ref "RPR72") (pin "4") (pinfunction "Col_4") (pintype "unspecified"))
    )
    (net (code "176") (name "LS73") (class "Default")
      (node (ref "ML7") (pin "4") (pinfunction "Y7_4") (pintype "unspecified"))
      (node (ref "RLU73") (pin "1") (pinfunction "1_1") (pintype "unspecified"))
      (node (ref "RPR73") (pin "4") (pinfunction "Col_4") (pintype "unspecified"))
    )
    (net (code "177") (name "LS74") (class "Default")
      (node (ref "ML7") (pin "5") (pinfunction "Y5_5") (pintype "unspecified"))
      (node (ref "RLU74") (pin "2") (pinfunction "2_2") (pintype "unspecified"))
      (node (ref "RPR74") (pin "4") (pinfunction "Col_4") (pintype "unspecified"))
    )
    (net (code "178") (name "LS75") (class "Default")
      (node (ref "ML7") (pin "12") (pinfunction "Y3_12") (pintype "unspecified"))
      (node (ref "RLU75") (pin "2") (pinfunction "2_2") (pintype "unspecified"))
      (node (ref "RPR75") (pin "4") (pinfunction "Col_4") (pintype "unspecified"))
    )
    (net (code "179") (name "LS76") (class "Default")
      (node (ref "ML7") (pin "13") (pinfunction "Y0_13") (pintype "unspecified"))
      (node (ref "RLU76") (pin "2") (pinfunction "2_2") (pintype "unspecified"))
      (node (ref "RPR76") (pin "4") (pinfunction "Col_4") (pintype "unspecified"))
    )
    (net (code "180") (name "LS77") (class "Default")
      (node (ref "ML7") (pin "14") (pinfunction "Y1_14") (pintype "unspecified"))
      (node (ref "RLU77") (pin "2") (pinfunction "2_2") (pintype "unspecified"))
      (node (ref "RPR77") (pin "4") (pinfunction "Col_4") (pintype "unspecified"))
    )
    (net (code "181") (name "LS78") (class "Default")
      (node (ref "ML7") (pin "15") (pinfunction "Y2_15") (pintype "unspecified"))
      (node (ref "RLU78") (pin "2") (pinfunction "2_2") (pintype "unspecified"))
      (node (ref "RPR78") (pin "4") (pinfunction "Col_4") (pintype "unspecified"))
    )
    (net (code "182") (name "LS79") (class "Default")
      (node (ref "ML10") (pin "14") (pinfunction "Y1_14") (pintype "unspecified"))
      (node (ref "RLU79") (pin "2") (pinfunction "2_2") (pintype "unspecified"))
      (node (ref "RPR79") (pin "4") (pinfunction "Col_4") (pintype "unspecified"))
    )
    (net (code "183") (name "LS81") (class "Default")
      (node (ref "ML8") (pin "1") (pinfunction "Y4_1") (pintype "unspecified"))
      (node (ref "RLU81") (pin "1") (pinfunction "1_1") (pintype "unspecified"))
      (node (ref "RPR81") (pin "4") (pinfunction "Col_4") (pintype "unspecified"))
    )
    (net (code "184") (name "LS82") (class "Default")
      (node (ref "ML8") (pin "2") (pinfunction "Y6_2") (pintype "unspecified"))
      (node (ref "RLU82") (pin "1") (pinfunction "1_1") (pintype "unspecified"))
      (node (ref "RPR82") (pin "4") (pinfunction "Col_4") (pintype "unspecified"))
    )
    (net (code "185") (name "LS83") (class "Default")
      (node (ref "ML8") (pin "4") (pinfunction "Y7_4") (pintype "unspecified"))
      (node (ref "RLU83") (pin "1") (pinfunction "1_1") (pintype "unspecified"))
      (node (ref "RPR83") (pin "4") (pinfunction "Col_4") (pintype "unspecified"))
    )
    (net (code "186") (name "LS84") (class "Default")
      (node (ref "ML8") (pin "5") (pinfunction "Y5_5") (pintype "unspecified"))
      (node (ref "RLU84") (pin "1") (pinfunction "1_1") (pintype "unspecified"))
      (node (ref "RPR84") (pin "4") (pinfunction "Col_4") (pintype "unspecified"))
    )
    (net (code "187") (name "LS85") (class "Default")
      (node (ref "ML8") (pin "12") (pinfunction "Y3_12") (pintype "unspecified"))
      (node (ref "RLU85") (pin "1") (pinfunction "1_1") (pintype "unspecified"))
      (node (ref "RPR85") (pin "4") (pinfunction "Col_4") (pintype "unspecified"))
    )
    (net (code "188") (name "LS86") (class "Default")
      (node (ref "ML8") (pin "13") (pinfunction "Y0_13") (pintype "unspecified"))
      (node (ref "RLU86") (pin "1") (pinfunction "1_1") (pintype "unspecified"))
      (node (ref "RPR86") (pin "4") (pinfunction "Col_4") (pintype "unspecified"))
    )
    (net (code "189") (name "LS87") (class "Default")
      (node (ref "ML8") (pin "14") (pinfunction "Y1_14") (pintype "unspecified"))
      (node (ref "RLU87") (pin "2") (pinfunction "2_2") (pintype "unspecified"))
      (node (ref "RPR87") (pin "4") (pinfunction "Col_4") (pintype "unspecified"))
    )
    (net (code "190") (name "LS88") (class "Default")
      (node (ref "ML8") (pin "15") (pinfunction "Y2_15") (pintype "unspecified"))
      (node (ref "RLU88") (pin "2") (pinfunction "2_2") (pintype "unspecified"))
      (node (ref "RPR88") (pin "4") (pinfunction "Col_4") (pintype "unspecified"))
    )
    (net (code "191") (name "LS89") (class "Default")
      (node (ref "ML10") (pin "15") (pinfunction "Y2_15") (pintype "unspecified"))
      (node (ref "RLU89") (pin "2") (pinfunction "2_2") (pintype "unspecified"))
      (node (ref "RPR89") (pin "4") (pinfunction "Col_4") (pintype "unspecified"))
    )
    (net (code "192") (name "LS91") (class "Default")
      (node (ref "ML9") (pin "1") (pinfunction "Y4_1") (pintype "unspecified"))
      (node (ref "RLU91") (pin "1") (pinfunction "1_1") (pintype "unspecified"))
      (node (ref "RPR91") (pin "4") (pinfunction "Col_4") (pintype "unspecified"))
    )
    (net (code "193") (name "LS92") (class "Default")
      (node (ref "ML9") (pin "2") (pinfunction "Y6_2") (pintype "unspecified"))
      (node (ref "RLU92") (pin "1") (pinfunction "1_1") (pintype "unspecified"))
      (node (ref "RPR92") (pin "4") (pinfunction "Col_4") (pintype "unspecified"))
    )
    (net (code "194") (name "LS93") (class "Default")
      (node (ref "ML9") (pin "4") (pinfunction "Y7_4") (pintype "unspecified"))
      (node (ref "RLU93") (pin "1") (pinfunction "1_1") (pintype "unspecified"))
      (node (ref "RPR93") (pin "4") (pinfunction "Col_4") (pintype "unspecified"))
    )
    (net (code "195") (name "LS94") (class "Default")
      (node (ref "ML9") (pin "5") (pinfunction "Y5_5") (pintype "unspecified"))
      (node (ref "RLU94") (pin "2") (pinfunction "2_2") (pintype "unspecified"))
      (node (ref "RPR94") (pin "4") (pinfunction "Col_4") (pintype "unspecified"))
    )
    (net (code "196") (name "LS95") (class "Default")
      (node (ref "ML9") (pin "12") (pinfunction "Y3_12") (pintype "unspecified"))
      (node (ref "RLU95") (pin "2") (pinfunction "2_2") (pintype "unspecified"))
      (node (ref "RPR95") (pin "4") (pinfunction "Col_4") (pintype "unspecified"))
    )
    (net (code "197") (name "LS96") (class "Default")
      (node (ref "ML9") (pin "13") (pinfunction "Y0_13") (pintype "unspecified"))
      (node (ref "RLU96") (pin "2") (pinfunction "2_2") (pintype "unspecified"))
      (node (ref "RPR96") (pin "4") (pinfunction "Col_4") (pintype "unspecified"))
    )
    (net (code "198") (name "LS97") (class "Default")
      (node (ref "ML9") (pin "14") (pinfunction "Y1_14") (pintype "unspecified"))
      (node (ref "RLU97") (pin "2") (pinfunction "2_2") (pintype "unspecified"))
      (node (ref "RPR97") (pin "4") (pinfunction "Col_4") (pintype "unspecified"))
    )
    (net (code "199") (name "LS98") (class "Default")
      (node (ref "ML9") (pin "15") (pinfunction "Y2_15") (pintype "unspecified"))
      (node (ref "RLU98") (pin "2") (pinfunction "2_2") (pintype "unspecified"))
      (node (ref "RPR98") (pin "4") (pinfunction "Col_4") (pintype "unspecified"))
    )
    (net (code "200") (name "LS99") (class "Default")
      (node (ref "RLU99") (pin "2") (pinfunction "2_2") (pintype "unspecified"))
      (node (ref "RPR99") (pin "4") (pinfunction "Col_4") (pintype "unspecified"))
      (node (ref "U1") (pin "1") (pinfunction "RC7_1") (pintype "unspecified"))
    )
    (net (code "201") (name "LS_O1") (class "Default")
      (node (ref "ML1") (pin "3") (pinfunction "COM_3") (pintype "unspecified"))
      (node (ref "ML11") (pin "1") (pinfunction "Y4_1") (pintype "unspecified"))
    )
    (net (code "202") (name "LS_O2") (class "Default")
      (node (ref "ML11") (pin "2") (pinfunction "Y6_2") (pintype "unspecified"))
      (node (ref "ML2") (pin "3") (pinfunction "COM_3") (pintype "unspecified"))
    )
    (net (code "203") (name "LS_O3") (class "Default")
      (node (ref "ML11") (pin "4") (pinfunction "Y7_4") (pintype "unspecified"))
      (node (ref "ML3") (pin "3") (pinfunction "COM_3") (pintype "unspecified"))
    )
    (net (code "204") (name "LS_O4") (class "Default")
      (node (ref "ML11") (pin "5") (pinfunction "Y5_5") (pintype "unspecified"))
      (node (ref "ML4") (pin "3") (pinfunction "COM_3") (pintype "unspecified"))
    )
    (net (code "205") (name "LS_O5") (class "Default")
      (node (ref "ML11") (pin "12") (pinfunction "Y3_12") (pintype "unspecified"))
      (node (ref "ML5") (pin "3") (pinfunction "COM_3") (pintype "unspecified"))
    )
    (net (code "206") (name "LS_O6") (class "Default")
      (node (ref "ML11") (pin "13") (pinfunction "Y0_13") (pintype "unspecified"))
      (node (ref "ML6") (pin "3") (pinfunction "COM_3") (pintype "unspecified"))
    )
    (net (code "207") (name "LS_O7") (class "Default")
      (node (ref "ML11") (pin "14") (pinfunction "Y1_14") (pintype "unspecified"))
      (node (ref "ML7") (pin "3") (pinfunction "COM_3") (pintype "unspecified"))
    )
    (net (code "208") (name "LS_O8") (class "Default")
      (node (ref "ML11") (pin "15") (pinfunction "Y2_15") (pintype "unspecified"))
      (node (ref "ML8") (pin "3") (pinfunction "COM_3") (pintype "unspecified"))
    )
    (net (code "209") (name "LS_O9") (class "Default")
      (node (ref "ML9") (pin "3") (pinfunction "COM_3") (pintype "unspecified"))
      (node (ref "U1") (pin "8") (pinfunction "RB0_8") (pintype "unspecified"))
    )
    (net (code "210") (name "LS_O10") (class "Default")
      (node (ref "ML10") (pin "3") (pinfunction "COM_3") (pintype "unspecified"))
      (node (ref "U1") (pin "27") (pinfunction "RE2_27") (pintype "unspecified"))
    )
    (net (code "211") (name "LS_OM") (class "Default")
      (node (ref "ML11") (pin "3") (pinfunction "COM_3") (pintype "unspecified"))
      (node (ref "U1") (pin "10") (pinfunction "RB2_10") (pintype "unspecified"))
    )
    (net (code "212") (name "MCLR_N") (class "Default")
      (node (ref "H2") (pin "1") (pinfunction "1_1") (pintype "unspecified"))
      (node (ref "R5") (pin "1") (pinfunction "1_1") (pintype "unspecified"))
      (node (ref "U1") (pin "18") (pinfunction "VPP/MCLR#/RE3_18") (pintype "unspecified"))
    )
    (net (code "213") (name "Net-(LED1-Pad1)") (class "Default")
      (node (ref "LED1") (pin "1") (pinfunction "1_1") (pintype "unspecified"))
      (node (ref "R2") (pin "1") (pinfunction "1_1") (pintype "unspecified"))
    )
    (net (code "214") (name "Net-(Q1-G)") (class "Default")
      (node (ref "Q1") (pin "1") (pinfunction "G_1") (pintype "unspecified"))
      (node (ref "RS1") (pin "2") (pinfunction "2_2") (pintype "unspecified"))
    )
    (net (code "215") (name "Net-(Q2-G)") (class "Default")
      (node (ref "Q2") (pin "1") (pinfunction "G_1") (pintype "unspecified"))
      (node (ref "RS2") (pin "2") (pinfunction "2_2") (pintype "unspecified"))
    )
    (net (code "216") (name "Net-(Q3-G)") (class "Default")
      (node (ref "Q3") (pin "1") (pinfunction "G_1") (pintype "unspecified"))
      (node (ref "RS3") (pin "2") (pinfunction "2_2") (pintype "unspecified"))
    )
    (net (code "217") (name "Net-(Q4-G)") (class "Default")
      (node (ref "Q4") (pin "1") (pinfunction "G_1") (pintype "unspecified"))
      (node (ref "RS4") (pin "2") (pinfunction "2_2") (pintype "unspecified"))
    )
    (net (code "218") (name "Net-(Q5-G)") (class "Default")
      (node (ref "Q5") (pin "1") (pinfunction "G_1") (pintype "unspecified"))
      (node (ref "RS5") (pin "2") (pinfunction "2_2") (pintype "unspecified"))
    )
    (net (code "219") (name "Net-(Q6-G)") (class "Default")
      (node (ref "Q6") (pin "1") (pinfunction "G_1") (pintype "unspecified"))
      (node (ref "RS6") (pin "2") (pinfunction "2_2") (pintype "unspecified"))
    )
    (net (code "220") (name "Net-(Q7-G)") (class "Default")
      (node (ref "Q7") (pin "1") (pinfunction "G_1") (pintype "unspecified"))
      (node (ref "RS7") (pin "2") (pinfunction "2_2") (pintype "unspecified"))
    )
    (net (code "221") (name "Net-(Q8-G)") (class "Default")
      (node (ref "Q8") (pin "1") (pinfunction "G_1") (pintype "unspecified"))
      (node (ref "RS8") (pin "2") (pinfunction "2_2") (pintype "unspecified"))
    )
    (net (code "222") (name "Net-(Q9-G)") (class "Default")
      (node (ref "Q9") (pin "1") (pinfunction "G_1") (pintype "unspecified"))
      (node (ref "RS9") (pin "2") (pinfunction "2_2") (pintype "unspecified"))
    )
    (net (code "223") (name "Net-(RPR11-Cat)") (class "Default")
      (node (ref "RLD11") (pin "2") (pinfunction "2_2") (pintype "unspecified"))
      (node (ref "RPR11") (pin "2") (pinfunction "Cat_2") (pintype "unspecified"))
    )
    (net (code "224") (name "Net-(RPR12-Cat)") (class "Default")
      (node (ref "RLD12") (pin "2") (pinfunction "2_2") (pintype "unspecified"))
      (node (ref "RPR12") (pin "2") (pinfunction "Cat_2") (pintype "unspecified"))
    )
    (net (code "225") (name "Net-(RPR13-Cat)") (class "Default")
      (node (ref "RLD13") (pin "2") (pinfunction "2_2") (pintype "unspecified"))
      (node (ref "RPR13") (pin "2") (pinfunction "Cat_2") (pintype "unspecified"))
    )
    (net (code "226") (name "Net-(RPR14-Cat)") (class "Default")
      (node (ref "RLD14") (pin "1") (pinfunction "1_1") (pintype "unspecified"))
      (node (ref "RPR14") (pin "2") (pinfunction "Cat_2") (pintype "unspecified"))
    )
    (net (code "227") (name "Net-(RPR15-Cat)") (class "Default")
      (node (ref "RLD15") (pin "1") (pinfunction "1_1") (pintype "unspecified"))
      (node (ref "RPR15") (pin "2") (pinfunction "Cat_2") (pintype "unspecified"))
    )
    (net (code "228") (name "Net-(RPR16-Cat)") (class "Default")
      (node (ref "RLD16") (pin "1") (pinfunction "1_1") (pintype "unspecified"))
      (node (ref "RPR16") (pin "2") (pinfunction "Cat_2") (pintype "unspecified"))
    )
    (net (code "229") (name "Net-(RPR17-Cat)") (class "Default")
      (node (ref "RLD17") (pin "1") (pinfunction "1_1") (pintype "unspecified"))
      (node (ref "RPR17") (pin "2") (pinfunction "Cat_2") (pintype "unspecified"))
    )
    (net (code "230") (name "Net-(RPR18-Cat)") (class "Default")
      (node (ref "RLD18") (pin "1") (pinfunction "1_1") (pintype "unspecified"))
      (node (ref "RPR18") (pin "2") (pinfunction "Cat_2") (pintype "unspecified"))
    )
    (net (code "231") (name "Net-(RPR19-Cat)") (class "Default")
      (node (ref "RLD19") (pin "1") (pinfunction "1_1") (pintype "unspecified"))
      (node (ref "RPR19") (pin "2") (pinfunction "Cat_2") (pintype "unspecified"))
    )
    (net (code "232") (name "Net-(RPR21-Cat)") (class "Default")
      (node (ref "RLD21") (pin "2") (pinfunction "2_2") (pintype "unspecified"))
      (node (ref "RPR21") (pin "2") (pinfunction "Cat_2") (pintype "unspecified"))
    )
    (net (code "233") (name "Net-(RPR22-Cat)") (class "Default")
      (node (ref "RLD22") (pin "2") (pinfunction "2_2") (pintype "unspecified"))
      (node (ref "RPR22") (pin "2") (pinfunction "Cat_2") (pintype "unspecified"))
    )
    (net (code "234") (name "Net-(RPR23-Cat)") (class "Default")
      (node (ref "RLD23") (pin "2") (pinfunction "2_2") (pintype "unspecified"))
      (node (ref "RPR23") (pin "2") (pinfunction "Cat_2") (pintype "unspecified"))
    )
    (net (code "235") (name "Net-(RPR24-Cat)") (class "Default")
      (node (ref "RLD24") (pin "2") (pinfunction "2_2") (pintype "unspecified"))
      (node (ref "RPR24") (pin "2") (pinfunction "Cat_2") (pintype "unspecified"))
    )
    (net (code "236") (name "Net-(RPR25-Cat)") (class "Default")
      (node (ref "RLD25") (pin "2") (pinfunction "2_2") (pintype "unspecified"))
      (node (ref "RPR25") (pin "2") (pinfunction "Cat_2") (pintype "unspecified"))
    )
    (net (code "237") (name "Net-(RPR26-Cat)") (class "Default")
      (node (ref "RLD26") (pin "2") (pinfunction "2_2") (pintype "unspecified"))
      (node (ref "RPR26") (pin "2") (pinfunction "Cat_2") (pintype "unspecified"))
    )
    (net (code "238") (name "Net-(RPR27-Cat)") (class "Default")
      (node (ref "RLD27") (pin "2") (pinfunction "2_2") (pintype "unspecified"))
      (node (ref "RPR27") (pin "2") (pinfunction "Cat_2") (pintype "unspecified"))
    )
    (net (code "239") (name "Net-(RPR28-Cat)") (class "Default")
      (node (ref "RLD28") (pin "2") (pinfunction "2_2") (pintype "unspecified"))
      (node (ref "RPR28") (pin "2") (pinfunction "Cat_2") (pintype "unspecified"))
    )
    (net (code "240") (name "Net-(RPR29-Cat)") (class "Default")
      (node (ref "RLD29") (pin "2") (pinfunction "2_2") (pintype "unspecified"))
      (node (ref "RPR29") (pin "2") (pinfunction "Cat_2") (pintype "unspecified"))
    )
    (net (code "241") (name "Net-(RPR31-Cat)") (class "Default")
      (node (ref "RLD31") (pin "1") (pinfunction "1_1") (pintype "unspecified"))
      (node (ref "RPR31") (pin "2") (pinfunction "Cat_2") (pintype "unspecified"))
    )
    (net (code "242") (name "Net-(RPR32-Cat)") (class "Default")
      (node (ref "RLD32") (pin "1") (pinfunction "1_1") (pintype "unspecified"))
      (node (ref "RPR32") (pin "2") (pinfunction "Cat_2") (pintype "unspecified"))
    )
    (net (code "243") (name "Net-(RPR33-Cat)") (class "Default")
      (node (ref "RLD33") (pin "1") (pinfunction "1_1") (pintype "unspecified"))
      (node (ref "RPR33") (pin "2") (pinfunction "Cat_2") (pintype "unspecified"))
    )
    (net (code "244") (name "Net-(RPR34-Cat)") (class "Default")
      (node (ref "RLD34") (pin "1") (pinfunction "1_1") (pintype "unspecified"))
      (node (ref "RPR34") (pin "2") (pinfunction "Cat_2") (pintype "unspecified"))
    )
    (net (code "245") (name "Net-(RPR35-Cat)") (class "Default")
      (node (ref "RLD35") (pin "1") (pinfunction "1_1") (pintype "unspecified"))
      (node (ref "RPR35") (pin "2") (pinfunction "Cat_2") (pintype "unspecified"))
    )
    (net (code "246") (name "Net-(RPR36-Cat)") (class "Default")
      (node (ref "RLD36") (pin "1") (pinfunction "1_1") (pintype "unspecified"))
      (node (ref "RPR36") (pin "2") (pinfunction "Cat_2") (pintype "unspecified"))
    )
    (net (code "247") (name "Net-(RPR37-Cat)") (class "Default")
      (node (ref "RLD37") (pin "1") (pinfunction "1_1") (pintype "unspecified"))
      (node (ref "RPR37") (pin "2") (pinfunction "Cat_2") (pintype "unspecified"))
    )
    (net (code "248") (name "Net-(RPR38-Cat)") (class "Default")
      (node (ref "RLD38") (pin "1") (pinfunction "1_1") (pintype "unspecified"))
      (node (ref "RPR38") (pin "2") (pinfunction "Cat_2") (pintype "unspecified"))
    )
    (net (code "249") (name "Net-(RPR39-Cat)") (class "Default")
      (node (ref "RLD39") (pin "1") (pinfunction "1_1") (pintype "unspecified"))
      (node (ref "RPR39") (pin "2") (pinfunction "Cat_2") (pintype "unspecified"))
    )
    (net (code "250") (name "Net-(RPR41-Cat)") (class "Default")
      (node (ref "RLD41") (pin "2") (pinfunction "2_2") (pintype "unspecified"))
      (node (ref "RPR41") (pin "2") (pinfunction "Cat_2") (pintype "unspecified"))
    )
    (net (code "251") (name "Net-(RPR42-Cat)") (class "Default")
      (node (ref "RLD42") (pin "2") (pinfunction "2_2") (pintype "unspecified"))
      (node (ref "RPR42") (pin "2") (pinfunction "Cat_2") (pintype "unspecified"))
    )
    (net (code "252") (name "Net-(RPR43-Cat)") (class "Default")
      (node (ref "RLD43") (pin "2") (pinfunction "2_2") (pintype "unspecified"))
      (node (ref "RPR43") (pin "2") (pinfunction "Cat_2") (pintype "unspecified"))
    )
    (net (code "253") (name "Net-(RPR44-Cat)") (class "Default")
      (node (ref "RLD44") (pin "2") (pinfunction "2_2") (pintype "unspecified"))
      (node (ref "RPR44") (pin "2") (pinfunction "Cat_2") (pintype "unspecified"))
    )
    (net (code "254") (name "Net-(RPR45-Cat)") (class "Default")
      (node (ref "RLD45") (pin "2") (pinfunction "2_2") (pintype "unspecified"))
      (node (ref "RPR45") (pin "2") (pinfunction "Cat_2") (pintype "unspecified"))
    )
    (net (code "255") (name "Net-(RPR46-Cat)") (class "Default")
      (node (ref "RLD46") (pin "2") (pinfunction "2_2") (pintype "unspecified"))
      (node (ref "RPR46") (pin "2") (pinfunction "Cat_2") (pintype "unspecified"))
    )
    (net (code "256") (name "Net-(RPR47-Cat)") (class "Default")
      (node (ref "RLD47") (pin "2") (pinfunction "2_2") (pintype "unspecified"))
      (node (ref "RPR47") (pin "2") (pinfunction "Cat_2") (pintype "unspecified"))
    )
    (net (code "257") (name "Net-(RPR48-Cat)") (class "Default")
      (node (ref "RLD48") (pin "2") (pinfunction "2_2") (pintype "unspecified"))
      (node (ref "RPR48") (pin "2") (pinfunction "Cat_2") (pintype "unspecified"))
    )
    (net (code "258") (name "Net-(RPR49-Cat)") (class "Default")
      (node (ref "RLD49") (pin "2") (pinfunction "2_2") (pintype "unspecified"))
      (node (ref "RPR49") (pin "2") (pinfunction "Cat_2") (pintype "unspecified"))
    )
    (net (code "259") (name "Net-(RPR51-Cat)") (class "Default")
      (node (ref "RLD51") (pin "1") (pinfunction "1_1") (pintype "unspecified"))
      (node (ref "RPR51") (pin "2") (pinfunction "Cat_2") (pintype "unspecified"))
    )
    (net (code "260") (name "Net-(RPR52-Cat)") (class "Default")
      (node (ref "RLD52") (pin "1") (pinfunction "1_1") (pintype "unspecified"))
      (node (ref "RPR52") (pin "2") (pinfunction "Cat_2") (pintype "unspecified"))
    )
    (net (code "261") (name "Net-(RPR53-Cat)") (class "Default")
      (node (ref "RLD53") (pin "1") (pinfunction "1_1") (pintype "unspecified"))
      (node (ref "RPR53") (pin "2") (pinfunction "Cat_2") (pintype "unspecified"))
    )
    (net (code "262") (name "Net-(RPR54-Cat)") (class "Default")
      (node (ref "RLD54") (pin "1") (pinfunction "1_1") (pintype "unspecified"))
      (node (ref "RPR54") (pin "2") (pinfunction "Cat_2") (pintype "unspecified"))
    )
    (net (code "263") (name "Net-(RPR55-Cat)") (class "Default")
      (node (ref "RLD55") (pin "1") (pinfunction "1_1") (pintype "unspecified"))
      (node (ref "RPR55") (pin "2") (pinfunction "Cat_2") (pintype "unspecified"))
    )
    (net (code "264") (name "Net-(RPR56-Cat)") (class "Default")
      (node (ref "RLD56") (pin "1") (pinfunction "1_1") (pintype "unspecified"))
      (node (ref "RPR56") (pin "2") (pinfunction "Cat_2") (pintype "unspecified"))
    )
    (net (code "265") (name "Net-(RPR57-Cat)") (class "Default")
      (node (ref "RLD57") (pin "1") (pinfunction "1_1") (pintype "unspecified"))
      (node (ref "RPR57") (pin "2") (pinfunction "Cat_2") (pintype "unspecified"))
    )
    (net (code "266") (name "Net-(RPR58-Cat)") (class "Default")
      (node (ref "RLD58") (pin "1") (pinfunction "1_1") (pintype "unspecified"))
      (node (ref "RPR58") (pin "2") (pinfunction "Cat_2") (pintype "unspecified"))
    )
    (net (code "267") (name "Net-(RPR59-Cat)") (class "Default")
      (node (ref "RLD59") (pin "1") (pinfunction "1_1") (pintype "unspecified"))
      (node (ref "RPR59") (pin "2") (pinfunction "Cat_2") (pintype "unspecified"))
    )
    (net (code "268") (name "Net-(RPR61-Cat)") (class "Default")
      (node (ref "RLD61") (pin "2") (pinfunction "2_2") (pintype "unspecified"))
      (node (ref "RPR61") (pin "2") (pinfunction "Cat_2") (pintype "unspecified"))
    )
    (net (code "269") (name "Net-(RPR62-Cat)") (class "Default")
      (node (ref "RLD62") (pin "2") (pinfunction "2_2") (pintype "unspecified"))
      (node (ref "RPR62") (pin "2") (pinfunction "Cat_2") (pintype "unspecified"))
    )
    (net (code "270") (name "Net-(RPR63-Cat)") (class "Default")
      (node (ref "RLD63") (pin "2") (pinfunction "2_2") (pintype "unspecified"))
      (node (ref "RPR63") (pin "2") (pinfunction "Cat_2") (pintype "unspecified"))
    )
    (net (code "271") (name "Net-(RPR64-Cat)") (class "Default")
      (node (ref "RLD64") (pin "2") (pinfunction "2_2") (pintype "unspecified"))
      (node (ref "RPR64") (pin "2") (pinfunction "Cat_2") (pintype "unspecified"))
    )
    (net (code "272") (name "Net-(RPR65-Cat)") (class "Default")
      (node (ref "RLD65") (pin "2") (pinfunction "2_2") (pintype "unspecified"))
      (node (ref "RPR65") (pin "2") (pinfunction "Cat_2") (pintype "unspecified"))
    )
    (net (code "273") (name "Net-(RPR66-Cat)") (class "Default")
      (node (ref "RLD66") (pin "2") (pinfunction "2_2") (pintype "unspecified"))
      (node (ref "RPR66") (pin "2") (pinfunction "Cat_2") (pintype "unspecified"))
    )
    (net (code "274") (name "Net-(RPR67-Cat)") (class "Default")
      (node (ref "RLD67") (pin "2") (pinfunction "2_2") (pintype "unspecified"))
      (node (ref "RPR67") (pin "2") (pinfunction "Cat_2") (pintype "unspecified"))
    )
    (net (code "275") (name "Net-(RPR68-Cat)") (class "Default")
      (node (ref "RLD68") (pin "2") (pinfunction "2_2") (pintype "unspecified"))
      (node (ref "RPR68") (pin "2") (pinfunction "Cat_2") (pintype "unspecified"))
    )
    (net (code "276") (name "Net-(RPR69-Cat)") (class "Default")
      (node (ref "RLD69") (pin "2") (pinfunction "2_2") (pintype "unspecified"))
      (node (ref "RPR69") (pin "2") (pinfunction "Cat_2") (pintype "unspecified"))
    )
    (net (code "277") (name "Net-(RPR71-Cat)") (class "Default")
      (node (ref "RLD71") (pin "1") (pinfunction "1_1") (pintype "unspecified"))
      (node (ref "RPR71") (pin "2") (pinfunction "Cat_2") (pintype "unspecified"))
    )
    (net (code "278") (name "Net-(RPR72-Cat)") (class "Default")
      (node (ref "RLD72") (pin "1") (pinfunction "1_1") (pintype "unspecified"))
      (node (ref "RPR72") (pin "2") (pinfunction "Cat_2") (pintype "unspecified"))
    )
    (net (code "279") (name "Net-(RPR73-Cat)") (class "Default")
      (node (ref "RLD73") (pin "1") (pinfunction "1_1") (pintype "unspecified"))
      (node (ref "RPR73") (pin "2") (pinfunction "Cat_2") (pintype "unspecified"))
    )
    (net (code "280") (name "Net-(RPR74-Cat)") (class "Default")
      (node (ref "RLD74") (pin "1") (pinfunction "1_1") (pintype "unspecified"))
      (node (ref "RPR74") (pin "2") (pinfunction "Cat_2") (pintype "unspecified"))
    )
    (net (code "281") (name "Net-(RPR75-Cat)") (class "Default")
      (node (ref "RLD75") (pin "1") (pinfunction "1_1") (pintype "unspecified"))
      (node (ref "RPR75") (pin "2") (pinfunction "Cat_2") (pintype "unspecified"))
    )
    (net (code "282") (name "Net-(RPR76-Cat)") (class "Default")
      (node (ref "RLD76") (pin "1") (pinfunction "1_1") (pintype "unspecified"))
      (node (ref "RPR76") (pin "2") (pinfunction "Cat_2") (pintype "unspecified"))
    )
    (net (code "283") (name "Net-(RPR77-Cat)") (class "Default")
      (node (ref "RLD77") (pin "1") (pinfunction "1_1") (pintype "unspecified"))
      (node (ref "RPR77") (pin "2") (pinfunction "Cat_2") (pintype "unspecified"))
    )
    (net (code "284") (name "Net-(RPR78-Cat)") (class "Default")
      (node (ref "RLD78") (pin "1") (pinfunction "1_1") (pintype "unspecified"))
      (node (ref "RPR78") (pin "2") (pinfunction "Cat_2") (pintype "unspecified"))
    )
    (net (code "285") (name "Net-(RPR79-Cat)") (class "Default")
      (node (ref "RLD79") (pin "1") (pinfunction "1_1") (pintype "unspecified"))
      (node (ref "RPR79") (pin "2") (pinfunction "Cat_2") (pintype "unspecified"))
    )
    (net (code "286") (name "Net-(RPR81-Cat)") (class "Default")
      (node (ref "RLD81") (pin "2") (pinfunction "2_2") (pintype "unspecified"))
      (node (ref "RPR81") (pin "2") (pinfunction "Cat_2") (pintype "unspecified"))
    )
    (net (code "287") (name "Net-(RPR82-Cat)") (class "Default")
      (node (ref "RLD82") (pin "2") (pinfunction "2_2") (pintype "unspecified"))
      (node (ref "RPR82") (pin "2") (pinfunction "Cat_2") (pintype "unspecified"))
    )
    (net (code "288") (name "Net-(RPR83-Cat)") (class "Default")
      (node (ref "RLD83") (pin "2") (pinfunction "2_2") (pintype "unspecified"))
      (node (ref "RPR83") (pin "2") (pinfunction "Cat_2") (pintype "unspecified"))
    )
    (net (code "289") (name "Net-(RPR84-Cat)") (class "Default")
      (node (ref "RLD84") (pin "2") (pinfunction "2_2") (pintype "unspecified"))
      (node (ref "RPR84") (pin "2") (pinfunction "Cat_2") (pintype "unspecified"))
    )
    (net (code "290") (name "Net-(RPR85-Cat)") (class "Default")
      (node (ref "RLD85") (pin "2") (pinfunction "2_2") (pintype "unspecified"))
      (node (ref "RPR85") (pin "2") (pinfunction "Cat_2") (pintype "unspecified"))
    )
    (net (code "291") (name "Net-(RPR86-Cat)") (class "Default")
      (node (ref "RLD86") (pin "2") (pinfunction "2_2") (pintype "unspecified"))
      (node (ref "RPR86") (pin "2") (pinfunction "Cat_2") (pintype "unspecified"))
    )
    (net (code "292") (name "Net-(RPR87-Cat)") (class "Default")
      (node (ref "RLD87") (pin "2") (pinfunction "2_2") (pintype "unspecified"))
      (node (ref "RPR87") (pin "2") (pinfunction "Cat_2") (pintype "unspecified"))
    )
    (net (code "293") (name "Net-(RPR88-Cat)") (class "Default")
      (node (ref "RLD88") (pin "2") (pinfunction "2_2") (pintype "unspecified"))
      (node (ref "RPR88") (pin "2") (pinfunction "Cat_2") (pintype "unspecified"))
    )
    (net (code "294") (name "Net-(RPR89-Cat)") (class "Default")
      (node (ref "RLD89") (pin "2") (pinfunction "2_2") (pintype "unspecified"))
      (node (ref "RPR89") (pin "2") (pinfunction "Cat_2") (pintype "unspecified"))
    )
    (net (code "295") (name "Net-(RPR91-Cat)") (class "Default")
      (node (ref "RLD91") (pin "1") (pinfunction "1_1") (pintype "unspecified"))
      (node (ref "RPR91") (pin "2") (pinfunction "Cat_2") (pintype "unspecified"))
    )
    (net (code "296") (name "Net-(RPR92-Cat)") (class "Default")
      (node (ref "RLD92") (pin "1") (pinfunction "1_1") (pintype "unspecified"))
      (node (ref "RPR92") (pin "2") (pinfunction "Cat_2") (pintype "unspecified"))
    )
    (net (code "297") (name "Net-(RPR93-Cat)") (class "Default")
      (node (ref "RLD93") (pin "1") (pinfunction "1_1") (pintype "unspecified"))
      (node (ref "RPR93") (pin "2") (pinfunction "Cat_2") (pintype "unspecified"))
    )
    (net (code "298") (name "Net-(RPR94-Cat)") (class "Default")
      (node (ref "RLD94") (pin "1") (pinfunction "1_1") (pintype "unspecified"))
      (node (ref "RPR94") (pin "2") (pinfunction "Cat_2") (pintype "unspecified"))
    )
    (net (code "299") (name "Net-(RPR95-Cat)") (class "Default")
      (node (ref "RLD95") (pin "1") (pinfunction "1_1") (pintype "unspecified"))
      (node (ref "RPR95") (pin "2") (pinfunction "Cat_2") (pintype "unspecified"))
    )
    (net (code "300") (name "Net-(RPR96-Cat)") (class "Default")
      (node (ref "RLD96") (pin "1") (pinfunction "1_1") (pintype "unspecified"))
      (node (ref "RPR96") (pin "2") (pinfunction "Cat_2") (pintype "unspecified"))
    )
    (net (code "301") (name "Net-(RPR97-Cat)") (class "Default")
      (node (ref "RLD97") (pin "1") (pinfunction "1_1") (pintype "unspecified"))
      (node (ref "RPR97") (pin "2") (pinfunction "Cat_2") (pintype "unspecified"))
    )
    (net (code "302") (name "Net-(RPR98-Cat)") (class "Default")
      (node (ref "RLD98") (pin "1") (pinfunction "1_1") (pintype "unspecified"))
      (node (ref "RPR98") (pin "2") (pinfunction "Cat_2") (pintype "unspecified"))
    )
    (net (code "303") (name "Net-(RPR99-Cat)") (class "Default")
      (node (ref "RLD99") (pin "1") (pinfunction "1_1") (pintype "unspecified"))
      (node (ref "RPR99") (pin "2") (pinfunction "Cat_2") (pintype "unspecified"))
    )
    (net (code "304") (name "Net-(U2-EN)") (class "Default")
      (node (ref "R4") (pin "1") (pinfunction "1_1") (pintype "unspecified"))
      (node (ref "U2") (pin "3") (pinfunction "EN_3") (pintype "unspecified"))
    )
    (net (code "305") (name "Net-(U2-PG)") (class "Default")
      (node (ref "R3") (pin "1") (pinfunction "1_1") (pintype "unspecified"))
      (node (ref "U2") (pin "5") (pinfunction "PG_5") (pintype "unspecified"))
    )
    (net (code "306") (name "Net-(U4-P0_2)") (class "Default")
      (node (ref "LED1") (pin "2") (pinfunction "2_2") (pintype "unspecified"))
      (node (ref "U4") (pin "12") (pinfunction "P0_2_12") (pintype "unspecified"))
    )
    (net (code "307") (name "Net-(USB1-VBUS)") (class "Default")
      (node (ref "H1") (pin "2") (pinfunction "2_2") (pintype "input"))
      (node (ref "USB1") (pin "1") (pinfunction "VBUS_1") (pintype "bidirectional"))
    )
    (net (code "308") (name "RST_N") (class "Default")
      (node (ref "C1") (pin "2") (pinfunction "2_2") (pintype "unspecified"))
      (node (ref "R1") (pin "1") (pinfunction "1_1") (pintype "unspecified"))
      (node (ref "U1") (pin "40") (pinfunction "RD2_40") (pintype "unspecified"))
      (node (ref "U3") (pin "1") (pinfunction "OUT_N_1") (pintype "unspecified"))
      (node (ref "U4") (pin "10") (pinfunction "RST_N_10") (pintype "unspecified"))
    )
    (net (code "309") (name "RTS") (class "Default")
      (node (ref "U1") (pin "41") (pinfunction "RD3_41") (pintype "unspecified"))
      (node (ref "U4") (pin "9") (pinfunction "P3_6_9") (pintype "unspecified"))
    )
    (net (code "310") (name "S1") (class "Default")
      (node (ref "MA1") (pin "11") (pinfunction "A_11") (pintype "unspecified"))
      (node (ref "MA10") (pin "11") (pinfunction "A_11") (pintype "unspecified"))
      (node (ref "MA2") (pin "11") (pinfunction "A_11") (pintype "unspecified"))
      (node (ref "MA3") (pin "11") (pinfunction "A_11") (pintype "unspecified"))
      (node (ref "MA4") (pin "11") (pinfunction "A_11") (pintype "unspecified"))
      (node (ref "MA5") (pin "11") (pinfunction "A_11") (pintype "unspecified"))
      (node (ref "MA6") (pin "11") (pinfunction "A_11") (pintype "unspecified"))
      (node (ref "MA7") (pin "11") (pinfunction "A_11") (pintype "unspecified"))
      (node (ref "MA8") (pin "11") (pinfunction "A_11") (pintype "unspecified"))
      (node (ref "MA9") (pin "11") (pinfunction "A_11") (pintype "unspecified"))
      (node (ref "ML1") (pin "11") (pinfunction "A_11") (pintype "unspecified"))
      (node (ref "ML10") (pin "11") (pinfunction "A_11") (pintype "unspecified"))
      (node (ref "ML2") (pin "11") (pinfunction "A_11") (pintype "unspecified"))
      (node (ref "ML3") (pin "11") (pinfunction "A_11") (pintype "unspecified"))
      (node (ref "ML4") (pin "11") (pinfunction "A_11") (pintype "unspecified"))
      (node (ref "ML5") (pin "11") (pinfunction "A_11") (pintype "unspecified"))
      (node (ref "ML6") (pin "11") (pinfunction "A_11") (pintype "unspecified"))
      (node (ref "ML7") (pin "11") (pinfunction "A_11") (pintype "unspecified"))
      (node (ref "ML8") (pin "11") (pinfunction "A_11") (pintype "unspecified"))
      (node (ref "ML9") (pin "11") (pinfunction "A_11") (pintype "unspecified"))
      (node (ref "U1") (pin "19") (pinfunction "AN0/RA0_19") (pintype "unspecified"))
    )
    (net (code "311") (name "S2") (class "Default")
      (node (ref "MA1") (pin "10") (pinfunction "B_10") (pintype "unspecified"))
      (node (ref "MA10") (pin "10") (pinfunction "B_10") (pintype "unspecified"))
      (node (ref "MA2") (pin "10") (pinfunction "B_10") (pintype "unspecified"))
      (node (ref "MA3") (pin "10") (pinfunction "B_10") (pintype "unspecified"))
      (node (ref "MA4") (pin "10") (pinfunction "B_10") (pintype "unspecified"))
      (node (ref "MA5") (pin "10") (pinfunction "B_10") (pintype "unspecified"))
      (node (ref "MA6") (pin "10") (pinfunction "B_10") (pintype "unspecified"))
      (node (ref "MA7") (pin "10") (pinfunction "B_10") (pintype "unspecified"))
      (node (ref "MA8") (pin "10") (pinfunction "B_10") (pintype "unspecified"))
      (node (ref "MA9") (pin "10") (pinfunction "B_10") (pintype "unspecified"))
      (node (ref "ML1") (pin "10") (pinfunction "B_10") (pintype "unspecified"))
      (node (ref "ML10") (pin "10") (pinfunction "B_10") (pintype "unspecified"))
      (node (ref "ML2") (pin "10") (pinfunction "B_10") (pintype "unspecified"))
      (node (ref "ML3") (pin "10") (pinfunction "B_10") (pintype "unspecified"))
      (node (ref "ML4") (pin "10") (pinfunction "B_10") (pintype "unspecified"))
      (node (ref "ML5") (pin "10") (pinfunction "B_10") (pintype "unspecified"))
      (node (ref "ML6") (pin "10") (pinfunction "B_10") (pintype "unspecified"))
      (node (ref "ML7") (pin "10") (pinfunction "B_10") (pintype "unspecified"))
      (node (ref "ML8") (pin "10") (pinfunction "B_10") (pintype "unspecified"))
      (node (ref "ML9") (pin "10") (pinfunction "B_10") (pintype "unspecified"))
      (node (ref "U1") (pin "20") (pinfunction "RA1_20") (pintype "unspecified"))
    )
    (net (code "312") (name "S3") (class "Default")
      (node (ref "MA1") (pin "9") (pinfunction "C_9") (pintype "unspecified"))
      (node (ref "MA10") (pin "9") (pinfunction "C_9") (pintype "unspecified"))
      (node (ref "MA2") (pin "9") (pinfunction "C_9") (pintype "unspecified"))
      (node (ref "MA3") (pin "9") (pinfunction "C_9") (pintype "unspecified"))
      (node (ref "MA4") (pin "9") (pinfunction "C_9") (pintype "unspecified"))
      (node (ref "MA5") (pin "9") (pinfunction "C_9") (pintype "unspecified"))
      (node (ref "MA6") (pin "9") (pinfunction "C_9") (pintype "unspecified"))
      (node (ref "MA7") (pin "9") (pinfunction "C_9") (pintype "unspecified"))
      (node (ref "MA8") (pin "9") (pinfunction "C_9") (pintype "unspecified"))
      (node (ref "MA9") (pin "9") (pinfunction "C_9") (pintype "unspecified"))
      (node (ref "ML1") (pin "9") (pinfunction "C_9") (pintype "unspecified"))
      (node (ref "ML10") (pin "9") (pinfunction "C_9") (pintype "unspecified"))
      (node (ref "ML2") (pin "9") (pinfunction "C_9") (pintype "unspecified"))
      (node (ref "ML3") (pin "9") (pinfunction "C_9") (pintype "unspecified"))
      (node (ref "ML4") (pin "9") (pinfunction "C_9") (pintype "unspecified"))
      (node (ref "ML5") (pin "9") (pinfunction "C_9") (pintype "unspecified"))
      (node (ref "ML6") (pin "9") (pinfunction "C_9") (pintype "unspecified"))
      (node (ref "ML7") (pin "9") (pinfunction "C_9") (pintype "unspecified"))
      (node (ref "ML8") (pin "9") (pinfunction "C_9") (pintype "unspecified"))
      (node (ref "ML9") (pin "9") (pinfunction "C_9") (pintype "unspecified"))
      (node (ref "U1") (pin "21") (pinfunction "RA2_21") (pintype "unspecified"))
    )
    (net (code "313") (name "S4") (class "Default")
      (node (ref "MA11") (pin "11") (pinfunction "A_11") (pintype "unspecified"))
      (node (ref "ML11") (pin "11") (pinfunction "A_11") (pintype "unspecified"))
      (node (ref "U1") (pin "11") (pinfunction "RB3_11") (pintype "unspecified"))
    )
    (net (code "314") (name "S5") (class "Default")
      (node (ref "MA11") (pin "10") (pinfunction "B_10") (pintype "unspecified"))
      (node (ref "ML11") (pin "10") (pinfunction "B_10") (pintype "unspecified"))
      (node (ref "U1") (pin "14") (pinfunction "RB4_14") (pintype "unspecified"))
    )
    (net (code "315") (name "S6") (class "Default")
      (node (ref "MA11") (pin "9") (pinfunction "C_9") (pintype "unspecified"))
      (node (ref "ML11") (pin "9") (pinfunction "C_9") (pintype "unspecified"))
      (node (ref "U1") (pin "15") (pinfunction "RB5_15") (pintype "unspecified"))
    )
    (net (code "316") (name "STATUS1") (class "Default")
      (node (ref "U1") (pin "4") (pinfunction "RD6_4") (pintype "unspecified"))
      (node (ref "U4") (pin "4") (pinfunction "P1_3_4") (pintype "unspecified"))
    )
    (net (code "317") (name "STATUS2") (class "Default")
      (node (ref "U1") (pin "2") (pinfunction "RD4_2") (pintype "unspecified"))
      (node (ref "U4") (pin "5") (pinfunction "P1_7_5") (pintype "unspecified"))
    )
    (net (code "318") (name "SYS_CON") (class "Default")
      (node (ref "U1") (pin "32") (pinfunction "RC0_32") (pintype "unspecified"))
      (node (ref "U4") (pin "16") (pinfunction "P2_0_16") (pintype "unspecified"))
    )
    (net (code "319") (name "TRANS") (class "Default")
      (node (ref "U1") (pin "31") (pinfunction "RA6_31") (pintype "unspecified"))
      (node (ref "U4") (pin "15") (pinfunction "P2_7_15") (pintype "unspecified"))
    )
    (net (code "320") (name "WAKE_UP") (class "Default")
      (node (ref "U1") (pin "44") (pinfunction "RC6_44") (pintype "unspecified"))
      (node (ref "U4") (pin "6") (pinfunction "P1_6_6") (pintype "unspecified"))
    )
    (net (code "321") (name "unconnected-(H2-Pad6)") (class "Default")
      (node (ref "H2") (pin "6") (pinfunction "6_6") (pintype "unspecified+no_connect"))
    )
    (net (code "322") (name "unconnected-(U1-NC-Pad12)") (class "Default")
      (node (ref "U1") (pin "12") (pinfunction "NC_12") (pintype "unspecified+no_connect"))
    )
    (net (code "323") (name "unconnected-(U1-NC-Pad13)") (class "Default")
      (node (ref "U1") (pin "13") (pinfunction "NC_13") (pintype "unspecified+no_connect"))
    )
    (net (code "324") (name "unconnected-(U1-NC-Pad33)") (class "Default")
      (node (ref "U1") (pin "33") (pinfunction "NC_33") (pintype "unspecified+no_connect"))
    )
    (net (code "325") (name "unconnected-(U1-NC-Pad34)") (class "Default")
      (node (ref "U1") (pin "34") (pinfunction "NC_34") (pintype "unspecified+no_connect"))
    )
    (net (code "326") (name "unconnected-(U4-NC-Pad1)") (class "Default")
      (node (ref "U4") (pin "1") (pinfunction "NC_1") (pintype "unspecified+no_connect"))
    )
    (net (code "327") (name "unconnected-(USB1-Data+-Pad3)") (class "Default")
      (node (ref "USB1") (pin "3") (pinfunction "Data+_3") (pintype "input+no_connect"))
    )
    (net (code "328") (name "unconnected-(USB1-Data--Pad2)") (class "Default")
      (node (ref "USB1") (pin "2") (pinfunction "Data-_2") (pintype "input+no_connect"))
    )
    (net (code "329") (name "unconnected-(USB1-ID-Pad4)") (class "Default")
      (node (ref "USB1") (pin "4") (pinfunction "ID_4") (pintype "bidirectional+no_connect"))
    )
  )
)
